# Main_DIY_board_-_no_3V3.net
KiCad netlist of a schematic drawn in EAGLE
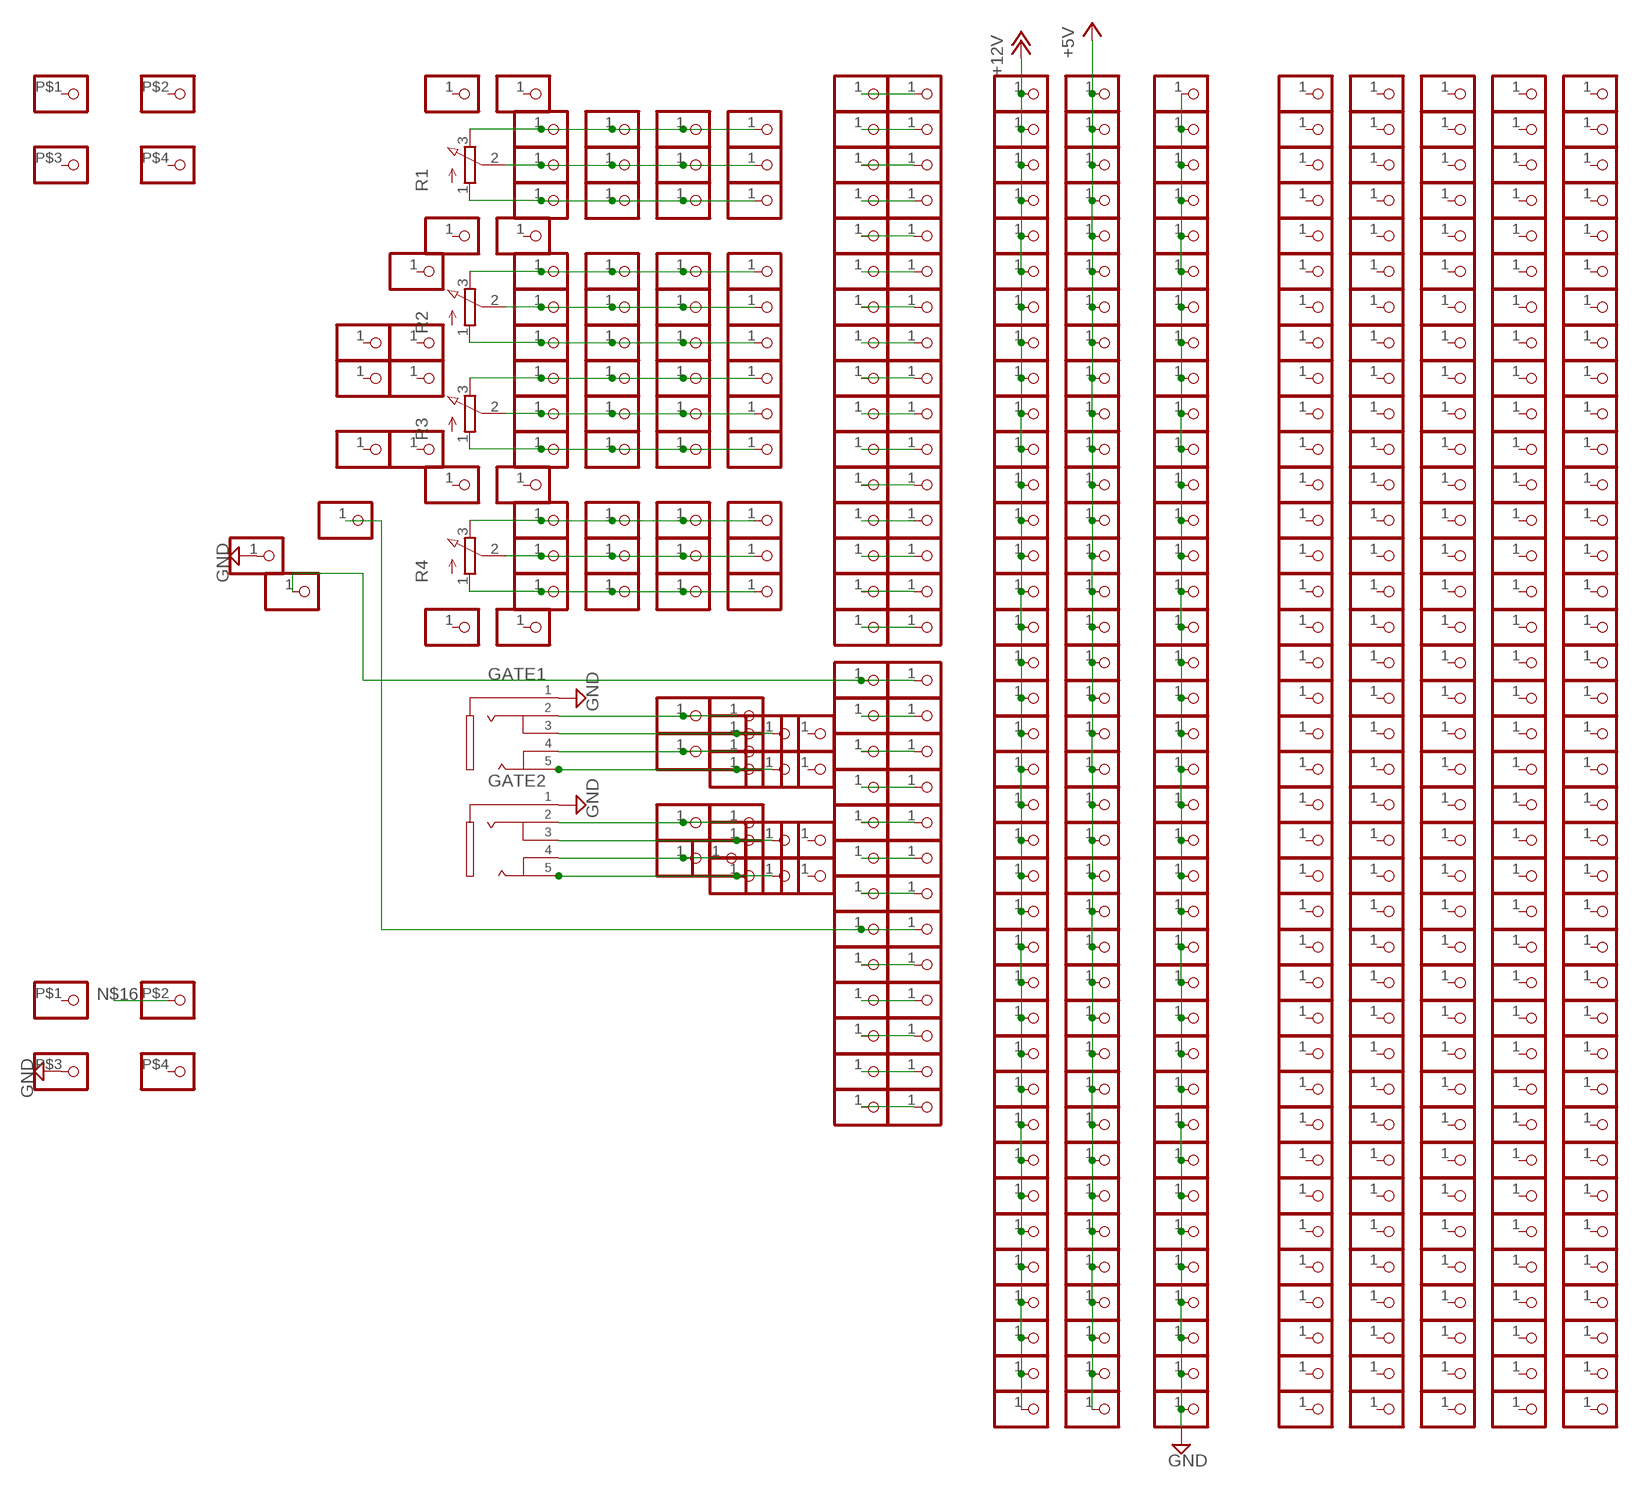
[diagram p0: schematic, sheet 1, part 1 of 2]
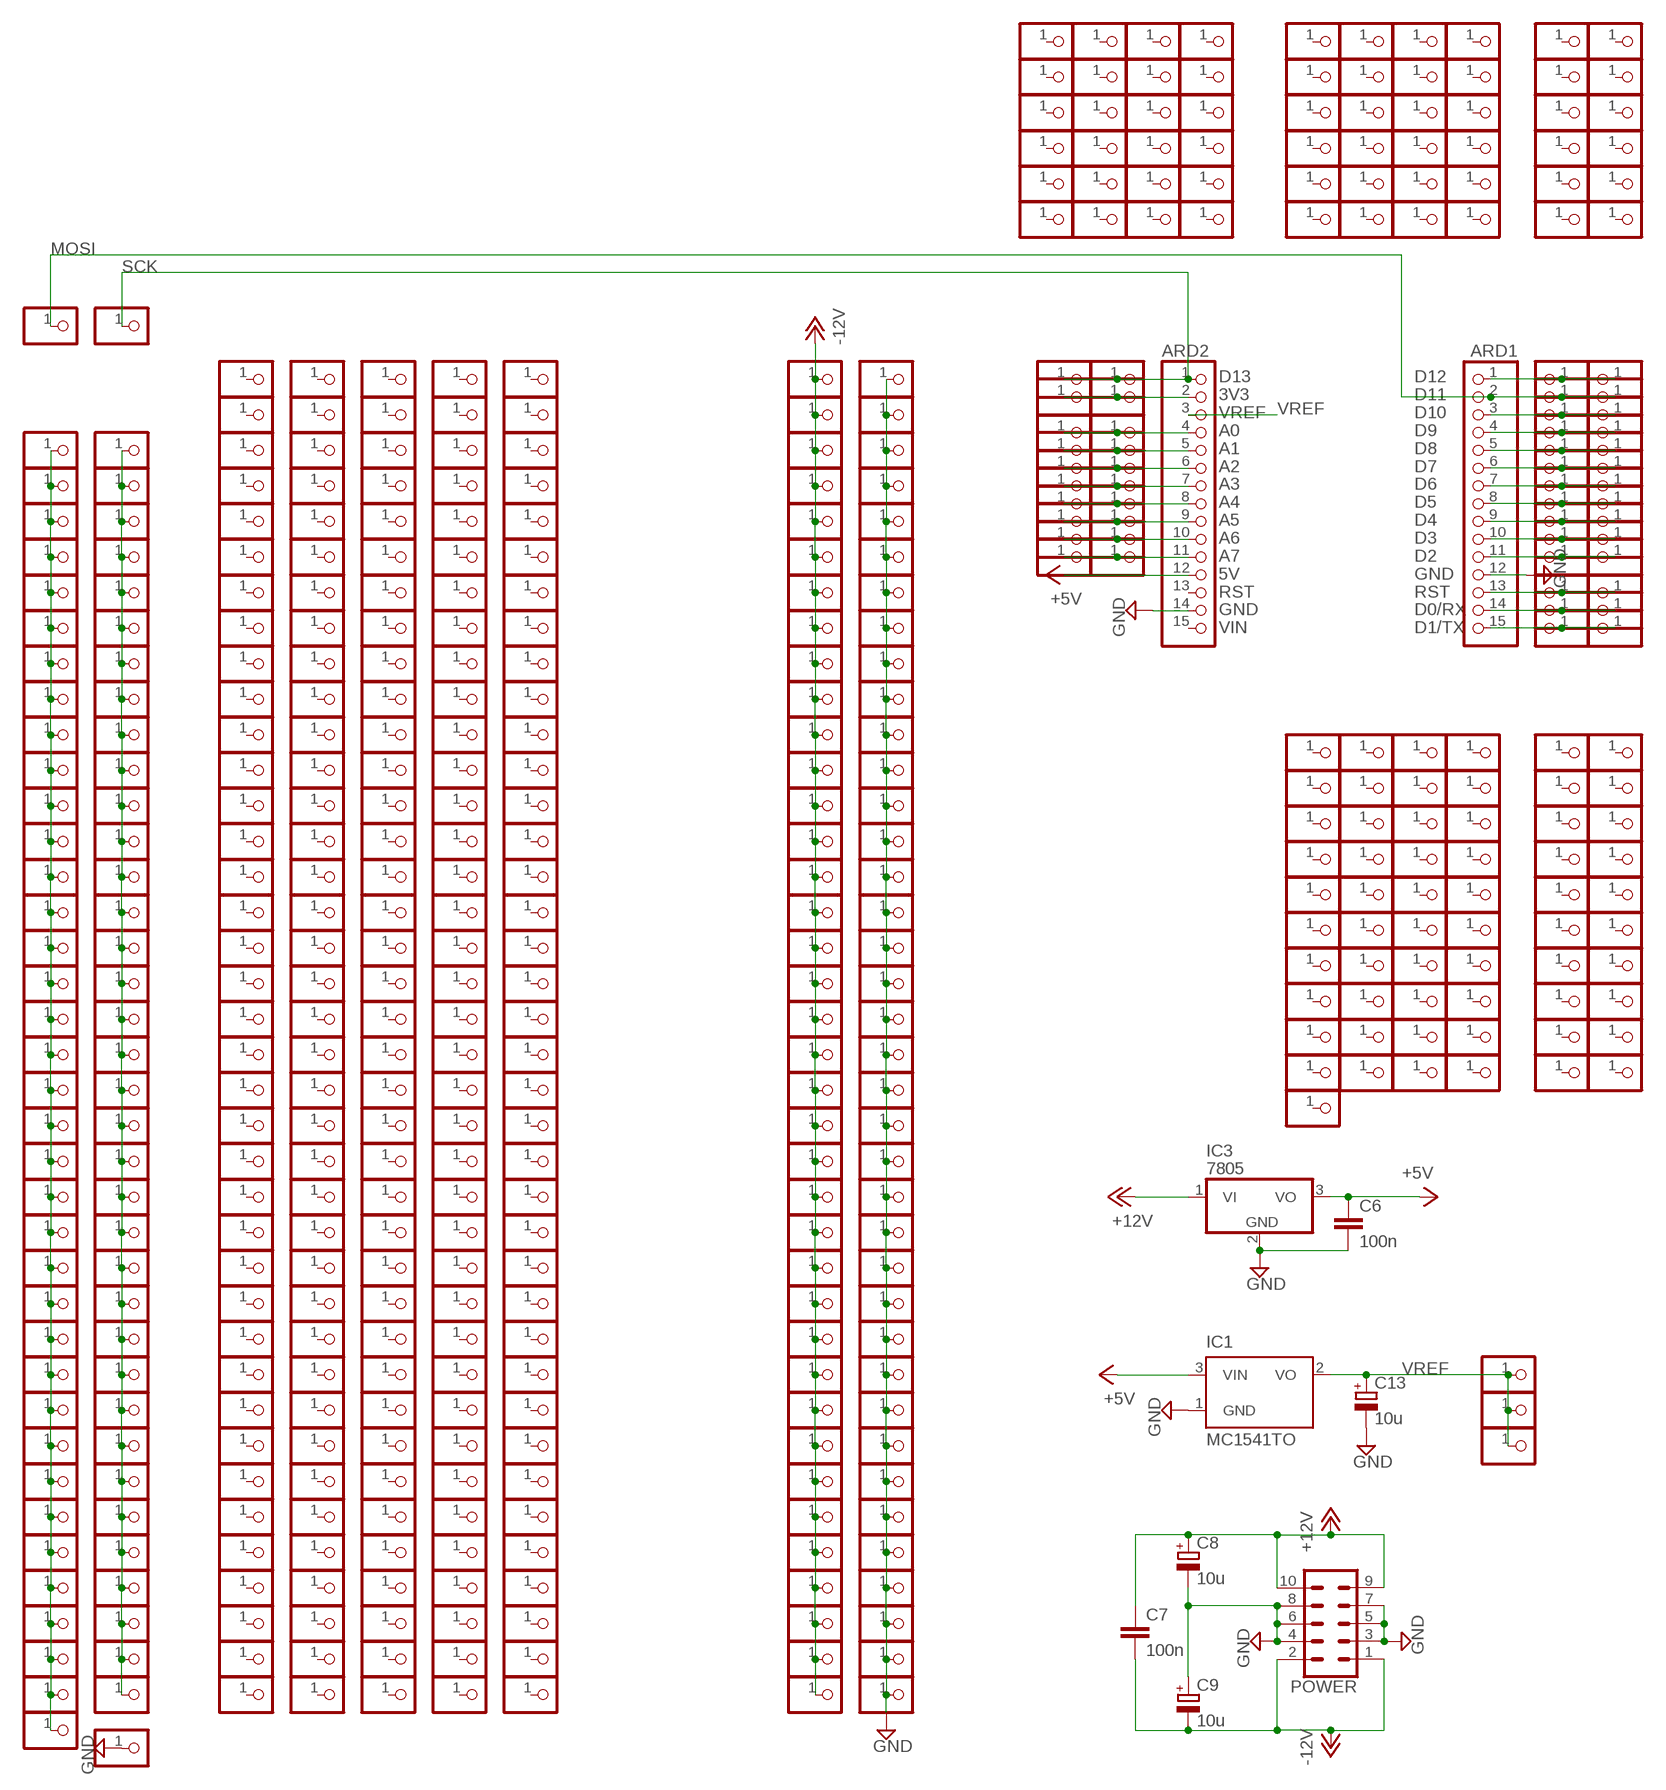
[diagram p1: schematic, sheet 1, part 2 of 2]

(export (version "E")
  (design (tool "Eeschema 10.0.6"))
  (components
    (comp (ref "ARD1")
      (value "PINHD-1X15")
      (footprint "eagle-import:1X15")
      (libsource (lib "eagle-import") (part "PINHD-1X15"))
    )
    (comp (ref "ARD2")
      (value "PINHD-1X15")
      (footprint "eagle-import:1X15")
      (libsource (lib "eagle-import") (part "PINHD-1X15"))
    )
    (comp (ref "C6")
      (value "100n")
      (footprint "eagle-import:C050-025X075")
      (libsource (lib "eagle-import") (part "C-EU050-025X075"))
    )
    (comp (ref "C7")
      (value "100n")
      (footprint "eagle-import:C050-025X075")
      (libsource (lib "eagle-import") (part "C-EU050-025X075"))
    )
    (comp (ref "C8")
      (value "10u")
      (footprint "eagle-import:E2,5-5")
      (libsource (lib "eagle-import") (part "CPOL"))
    )
    (comp (ref "C9")
      (value "10u")
      (footprint "eagle-import:E2,5-5")
      (libsource (lib "eagle-import") (part "CPOL"))
    )
    (comp (ref "C13")
      (value "10u")
      (footprint "eagle-import:E2,5-5")
      (libsource (lib "eagle-import") (part "CPOL"))
    )
    (comp (ref "GATE1")
      (value "PJ-324MH")
      (footprint "eagle-import:PJ-324MH")
      (libsource (lib "eagle-import") (part "PJ-324MH"))
    )
    (comp (ref "GATE2")
      (value "PJ-324MH")
      (footprint "eagle-import:PJ-324MH")
      (libsource (lib "eagle-import") (part "PJ-324MH"))
    )
    (comp (ref "IC1")
      (value "MC1541TO")
      (footprint "eagle-import:TO92")
      (libsource (lib "eagle-import") (part "MC15TO41"))
    )
    (comp (ref "IC3")
      (value "7805")
      (footprint "eagle-import:TO220H")
      (libsource (lib "eagle-import") (part "78T05"))
    )
    (comp (ref "JP1")
      (value "1X01")
      (footprint "eagle-import:1X01")
      (libsource (lib "eagle-import") (part "1X01"))
    )
    (comp (ref "JP2")
      (value "1X01")
      (footprint "eagle-import:1X01")
      (libsource (lib "eagle-import") (part "1X01"))
    )
    (comp (ref "JP3")
      (value "1X01")
      (footprint "eagle-import:1X01")
      (libsource (lib "eagle-import") (part "1X01"))
    )
    (comp (ref "JP4")
      (value "1X01")
      (footprint "eagle-import:1X01")
      (libsource (lib "eagle-import") (part "1X01"))
    )
    (comp (ref "JP5")
      (value "1X01")
      (footprint "eagle-import:1X01")
      (libsource (lib "eagle-import") (part "1X01"))
    )
    (comp (ref "JP6")
      (value "1X01")
      (footprint "eagle-import:1X01")
      (libsource (lib "eagle-import") (part "1X01"))
    )
    (comp (ref "JP7")
      (value "1X01")
      (footprint "eagle-import:1X01")
      (libsource (lib "eagle-import") (part "1X01"))
    )
    (comp (ref "JP8")
      (value "1X01")
      (footprint "eagle-import:1X01")
      (libsource (lib "eagle-import") (part "1X01"))
    )
    (comp (ref "JP9")
      (value "1X01")
      (footprint "eagle-import:1X01")
      (libsource (lib "eagle-import") (part "1X01"))
    )
    (comp (ref "JP10")
      (value "1X01")
      (footprint "eagle-import:1X01")
      (libsource (lib "eagle-import") (part "1X01"))
    )
    (comp (ref "JP11")
      (value "1X01")
      (footprint "eagle-import:1X01")
      (libsource (lib "eagle-import") (part "1X01"))
    )
    (comp (ref "JP12")
      (value "1X01")
      (footprint "eagle-import:1X01")
      (libsource (lib "eagle-import") (part "1X01"))
    )
    (comp (ref "JP13")
      (value "1X01")
      (footprint "eagle-import:1X01")
      (libsource (lib "eagle-import") (part "1X01"))
    )
    (comp (ref "JP14")
      (value "1X01")
      (footprint "eagle-import:1X01")
      (libsource (lib "eagle-import") (part "1X01"))
    )
    (comp (ref "JP15")
      (value "1X01")
      (footprint "eagle-import:1X01")
      (libsource (lib "eagle-import") (part "1X01"))
    )
    (comp (ref "JP16")
      (value "1X01")
      (footprint "eagle-import:1X01")
      (libsource (lib "eagle-import") (part "1X01"))
    )
    (comp (ref "JP17")
      (value "1X01")
      (footprint "eagle-import:1X01")
      (libsource (lib "eagle-import") (part "1X01"))
    )
    (comp (ref "JP18")
      (value "1X01")
      (footprint "eagle-import:1X01")
      (libsource (lib "eagle-import") (part "1X01"))
    )
    (comp (ref "JP19")
      (value "1X01")
      (footprint "eagle-import:1X01")
      (libsource (lib "eagle-import") (part "1X01"))
    )
    (comp (ref "JP20")
      (value "1X01")
      (footprint "eagle-import:1X01")
      (libsource (lib "eagle-import") (part "1X01"))
    )
    (comp (ref "JP21")
      (value "1X01")
      (footprint "eagle-import:1X01")
      (libsource (lib "eagle-import") (part "1X01"))
    )
    (comp (ref "JP22")
      (value "1X01")
      (footprint "eagle-import:1X01")
      (libsource (lib "eagle-import") (part "1X01"))
    )
    (comp (ref "JP23")
      (value "1X01")
      (footprint "eagle-import:1X01")
      (libsource (lib "eagle-import") (part "1X01"))
    )
    (comp (ref "JP24")
      (value "1X01")
      (footprint "eagle-import:1X01")
      (libsource (lib "eagle-import") (part "1X01"))
    )
    (comp (ref "JP25")
      (value "1X01")
      (footprint "eagle-import:1X01")
      (libsource (lib "eagle-import") (part "1X01"))
    )
    (comp (ref "JP26")
      (value "1X01")
      (footprint "eagle-import:1X01")
      (libsource (lib "eagle-import") (part "1X01"))
    )
    (comp (ref "JP27")
      (value "1X01")
      (footprint "eagle-import:1X01")
      (libsource (lib "eagle-import") (part "1X01"))
    )
    (comp (ref "JP28")
      (value "1X01")
      (footprint "eagle-import:1X01")
      (libsource (lib "eagle-import") (part "1X01"))
    )
    (comp (ref "JP29")
      (value "1X01")
      (footprint "eagle-import:1X01")
      (libsource (lib "eagle-import") (part "1X01"))
    )
    (comp (ref "JP30")
      (value "1X01")
      (footprint "eagle-import:1X01")
      (libsource (lib "eagle-import") (part "1X01"))
    )
    (comp (ref "JP31")
      (value "1X01")
      (footprint "eagle-import:1X01")
      (libsource (lib "eagle-import") (part "1X01"))
    )
    (comp (ref "JP32")
      (value "1X01")
      (footprint "eagle-import:1X01")
      (libsource (lib "eagle-import") (part "1X01"))
    )
    (comp (ref "JP33")
      (value "1X01")
      (footprint "eagle-import:1X01")
      (libsource (lib "eagle-import") (part "1X01"))
    )
    (comp (ref "JP34")
      (value "1X01")
      (footprint "eagle-import:1X01")
      (libsource (lib "eagle-import") (part "1X01"))
    )
    (comp (ref "JP35")
      (value "1X01")
      (footprint "eagle-import:1X01")
      (libsource (lib "eagle-import") (part "1X01"))
    )
    (comp (ref "JP36")
      (value "1X01")
      (footprint "eagle-import:1X01")
      (libsource (lib "eagle-import") (part "1X01"))
    )
    (comp (ref "JP37")
      (value "1X01")
      (footprint "eagle-import:1X01")
      (libsource (lib "eagle-import") (part "1X01"))
    )
    (comp (ref "JP38")
      (value "1X01")
      (footprint "eagle-import:1X01")
      (libsource (lib "eagle-import") (part "1X01"))
    )
    (comp (ref "JP39")
      (value "1X01")
      (footprint "eagle-import:1X01")
      (libsource (lib "eagle-import") (part "1X01"))
    )
    (comp (ref "JP40")
      (value "1X01")
      (footprint "eagle-import:1X01")
      (libsource (lib "eagle-import") (part "1X01"))
    )
    (comp (ref "JP41")
      (value "1X01")
      (footprint "eagle-import:1X01")
      (libsource (lib "eagle-import") (part "1X01"))
    )
    (comp (ref "JP42")
      (value "1X01")
      (footprint "eagle-import:1X01")
      (libsource (lib "eagle-import") (part "1X01"))
    )
    (comp (ref "JP43")
      (value "1X01")
      (footprint "eagle-import:1X01")
      (libsource (lib "eagle-import") (part "1X01"))
    )
    (comp (ref "JP44")
      (value "1X01")
      (footprint "eagle-import:1X01")
      (libsource (lib "eagle-import") (part "1X01"))
    )
    (comp (ref "JP45")
      (value "1X01")
      (footprint "eagle-import:1X01")
      (libsource (lib "eagle-import") (part "1X01"))
    )
    (comp (ref "JP46")
      (value "1X01")
      (footprint "eagle-import:1X01")
      (libsource (lib "eagle-import") (part "1X01"))
    )
    (comp (ref "JP47")
      (value "1X01")
      (footprint "eagle-import:1X01")
      (libsource (lib "eagle-import") (part "1X01"))
    )
    (comp (ref "JP48")
      (value "1X01")
      (footprint "eagle-import:1X01")
      (libsource (lib "eagle-import") (part "1X01"))
    )
    (comp (ref "JP49")
      (value "1X01")
      (footprint "eagle-import:1X01")
      (libsource (lib "eagle-import") (part "1X01"))
    )
    (comp (ref "JP50")
      (value "1X01")
      (footprint "eagle-import:1X01")
      (libsource (lib "eagle-import") (part "1X01"))
    )
    (comp (ref "JP51")
      (value "1X01")
      (footprint "eagle-import:1X01")
      (libsource (lib "eagle-import") (part "1X01"))
    )
    (comp (ref "JP52")
      (value "1X01")
      (footprint "eagle-import:1X01")
      (libsource (lib "eagle-import") (part "1X01"))
    )
    (comp (ref "JP53")
      (value "1X01")
      (footprint "eagle-import:1X01")
      (libsource (lib "eagle-import") (part "1X01"))
    )
    (comp (ref "JP54")
      (value "1X01")
      (footprint "eagle-import:1X01")
      (libsource (lib "eagle-import") (part "1X01"))
    )
    (comp (ref "JP55")
      (value "1X01")
      (footprint "eagle-import:1X01")
      (libsource (lib "eagle-import") (part "1X01"))
    )
    (comp (ref "JP56")
      (value "1X01")
      (footprint "eagle-import:1X01")
      (libsource (lib "eagle-import") (part "1X01"))
    )
    (comp (ref "JP57")
      (value "1X01")
      (footprint "eagle-import:1X01")
      (libsource (lib "eagle-import") (part "1X01"))
    )
    (comp (ref "JP58")
      (value "1X01")
      (footprint "eagle-import:1X01")
      (libsource (lib "eagle-import") (part "1X01"))
    )
    (comp (ref "JP59")
      (value "1X01")
      (footprint "eagle-import:1X01")
      (libsource (lib "eagle-import") (part "1X01"))
    )
    (comp (ref "JP60")
      (value "1X01")
      (footprint "eagle-import:1X01")
      (libsource (lib "eagle-import") (part "1X01"))
    )
    (comp (ref "JP61")
      (value "1X01")
      (footprint "eagle-import:1X01")
      (libsource (lib "eagle-import") (part "1X01"))
    )
    (comp (ref "JP62")
      (value "1X01")
      (footprint "eagle-import:1X01")
      (libsource (lib "eagle-import") (part "1X01"))
    )
    (comp (ref "JP63")
      (value "1X01")
      (footprint "eagle-import:1X01")
      (libsource (lib "eagle-import") (part "1X01"))
    )
    (comp (ref "JP64")
      (value "1X01")
      (footprint "eagle-import:1X01")
      (libsource (lib "eagle-import") (part "1X01"))
    )
    (comp (ref "JP65")
      (value "1X01")
      (footprint "eagle-import:1X01")
      (libsource (lib "eagle-import") (part "1X01"))
    )
    (comp (ref "JP66")
      (value "1X01")
      (footprint "eagle-import:1X01")
      (libsource (lib "eagle-import") (part "1X01"))
    )
    (comp (ref "JP67")
      (value "1X01")
      (footprint "eagle-import:1X01")
      (libsource (lib "eagle-import") (part "1X01"))
    )
    (comp (ref "JP68")
      (value "1X01")
      (footprint "eagle-import:1X01")
      (libsource (lib "eagle-import") (part "1X01"))
    )
    (comp (ref "JP69")
      (value "1X01")
      (footprint "eagle-import:1X01")
      (libsource (lib "eagle-import") (part "1X01"))
    )
    (comp (ref "JP70")
      (value "1X01")
      (footprint "eagle-import:1X01")
      (libsource (lib "eagle-import") (part "1X01"))
    )
    (comp (ref "JP71")
      (value "1X01")
      (footprint "eagle-import:1X01")
      (libsource (lib "eagle-import") (part "1X01"))
    )
    (comp (ref "JP72")
      (value "1X01")
      (footprint "eagle-import:1X01")
      (libsource (lib "eagle-import") (part "1X01"))
    )
    (comp (ref "JP73")
      (value "1X01")
      (footprint "eagle-import:1X01")
      (libsource (lib "eagle-import") (part "1X01"))
    )
    (comp (ref "JP74")
      (value "1X01")
      (footprint "eagle-import:1X01")
      (libsource (lib "eagle-import") (part "1X01"))
    )
    (comp (ref "JP75")
      (value "1X01")
      (footprint "eagle-import:1X01")
      (libsource (lib "eagle-import") (part "1X01"))
    )
    (comp (ref "JP76")
      (value "1X01")
      (footprint "eagle-import:1X01")
      (libsource (lib "eagle-import") (part "1X01"))
    )
    (comp (ref "JP77")
      (value "1X01")
      (footprint "eagle-import:1X01")
      (libsource (lib "eagle-import") (part "1X01"))
    )
    (comp (ref "JP78")
      (value "1X01")
      (footprint "eagle-import:1X01")
      (libsource (lib "eagle-import") (part "1X01"))
    )
    (comp (ref "JP79")
      (value "1X01")
      (footprint "eagle-import:1X01")
      (libsource (lib "eagle-import") (part "1X01"))
    )
    (comp (ref "JP80")
      (value "1X01")
      (footprint "eagle-import:1X01")
      (libsource (lib "eagle-import") (part "1X01"))
    )
    (comp (ref "JP81")
      (value "1X01")
      (footprint "eagle-import:1X01")
      (libsource (lib "eagle-import") (part "1X01"))
    )
    (comp (ref "JP82")
      (value "1X01")
      (footprint "eagle-import:1X01")
      (libsource (lib "eagle-import") (part "1X01"))
    )
    (comp (ref "JP83")
      (value "1X01")
      (footprint "eagle-import:1X01")
      (libsource (lib "eagle-import") (part "1X01"))
    )
    (comp (ref "JP84")
      (value "1X01")
      (footprint "eagle-import:1X01")
      (libsource (lib "eagle-import") (part "1X01"))
    )
    (comp (ref "JP85")
      (value "1X01")
      (footprint "eagle-import:1X01")
      (libsource (lib "eagle-import") (part "1X01"))
    )
    (comp (ref "JP86")
      (value "1X01")
      (footprint "eagle-import:1X01")
      (libsource (lib "eagle-import") (part "1X01"))
    )
    (comp (ref "JP87")
      (value "1X01")
      (footprint "eagle-import:1X01")
      (libsource (lib "eagle-import") (part "1X01"))
    )
    (comp (ref "JP88")
      (value "1X01")
      (footprint "eagle-import:1X01")
      (libsource (lib "eagle-import") (part "1X01"))
    )
    (comp (ref "JP89")
      (value "1X01")
      (footprint "eagle-import:1X01")
      (libsource (lib "eagle-import") (part "1X01"))
    )
    (comp (ref "JP90")
      (value "1X01")
      (footprint "eagle-import:1X01")
      (libsource (lib "eagle-import") (part "1X01"))
    )
    (comp (ref "JP91")
      (value "1X01")
      (footprint "eagle-import:1X01")
      (libsource (lib "eagle-import") (part "1X01"))
    )
    (comp (ref "JP92")
      (value "1X01")
      (footprint "eagle-import:1X01")
      (libsource (lib "eagle-import") (part "1X01"))
    )
    (comp (ref "JP93")
      (value "1X01")
      (footprint "eagle-import:1X01")
      (libsource (lib "eagle-import") (part "1X01"))
    )
    (comp (ref "JP94")
      (value "1X01")
      (footprint "eagle-import:1X01")
      (libsource (lib "eagle-import") (part "1X01"))
    )
    (comp (ref "JP95")
      (value "1X01")
      (footprint "eagle-import:1X01")
      (libsource (lib "eagle-import") (part "1X01"))
    )
    (comp (ref "JP96")
      (value "1X01")
      (footprint "eagle-import:1X01")
      (libsource (lib "eagle-import") (part "1X01"))
    )
    (comp (ref "JP97")
      (value "1X01")
      (footprint "eagle-import:1X01")
      (libsource (lib "eagle-import") (part "1X01"))
    )
    (comp (ref "JP98")
      (value "1X01")
      (footprint "eagle-import:1X01")
      (libsource (lib "eagle-import") (part "1X01"))
    )
    (comp (ref "JP99")
      (value "1X01")
      (footprint "eagle-import:1X01")
      (libsource (lib "eagle-import") (part "1X01"))
    )
    (comp (ref "JP100")
      (value "1X01")
      (footprint "eagle-import:1X01")
      (libsource (lib "eagle-import") (part "1X01"))
    )
    (comp (ref "JP101")
      (value "1X01")
      (footprint "eagle-import:1X01")
      (libsource (lib "eagle-import") (part "1X01"))
    )
    (comp (ref "JP102")
      (value "1X01")
      (footprint "eagle-import:1X01")
      (libsource (lib "eagle-import") (part "1X01"))
    )
    (comp (ref "JP103")
      (value "1X01")
      (footprint "eagle-import:1X01")
      (libsource (lib "eagle-import") (part "1X01"))
    )
    (comp (ref "JP104")
      (value "1X01")
      (footprint "eagle-import:1X01")
      (libsource (lib "eagle-import") (part "1X01"))
    )
    (comp (ref "JP105")
      (value "1X01")
      (footprint "eagle-import:1X01")
      (libsource (lib "eagle-import") (part "1X01"))
    )
    (comp (ref "JP106")
      (value "1X01")
      (footprint "eagle-import:1X01")
      (libsource (lib "eagle-import") (part "1X01"))
    )
    (comp (ref "JP107")
      (value "1X01")
      (footprint "eagle-import:1X01")
      (libsource (lib "eagle-import") (part "1X01"))
    )
    (comp (ref "JP108")
      (value "1X01")
      (footprint "eagle-import:1X01")
      (libsource (lib "eagle-import") (part "1X01"))
    )
    (comp (ref "JP109")
      (value "1X01")
      (footprint "eagle-import:1X01")
      (libsource (lib "eagle-import") (part "1X01"))
    )
    (comp (ref "JP110")
      (value "1X01")
      (footprint "eagle-import:1X01")
      (libsource (lib "eagle-import") (part "1X01"))
    )
    (comp (ref "JP111")
      (value "1X01")
      (footprint "eagle-import:1X01")
      (libsource (lib "eagle-import") (part "1X01"))
    )
    (comp (ref "JP112")
      (value "1X01")
      (footprint "eagle-import:1X01")
      (libsource (lib "eagle-import") (part "1X01"))
    )
    (comp (ref "JP113")
      (value "1X01")
      (footprint "eagle-import:1X01")
      (libsource (lib "eagle-import") (part "1X01"))
    )
    (comp (ref "JP114")
      (value "1X01")
      (footprint "eagle-import:1X01")
      (libsource (lib "eagle-import") (part "1X01"))
    )
    (comp (ref "JP115")
      (value "1X01")
      (footprint "eagle-import:1X01")
      (libsource (lib "eagle-import") (part "1X01"))
    )
    (comp (ref "JP116")
      (value "1X01")
      (footprint "eagle-import:1X01")
      (libsource (lib "eagle-import") (part "1X01"))
    )
    (comp (ref "JP117")
      (value "1X01")
      (footprint "eagle-import:1X01")
      (libsource (lib "eagle-import") (part "1X01"))
    )
    (comp (ref "JP118")
      (value "1X01")
      (footprint "eagle-import:1X01")
      (libsource (lib "eagle-import") (part "1X01"))
    )
    (comp (ref "JP119")
      (value "1X01")
      (footprint "eagle-import:1X01")
      (libsource (lib "eagle-import") (part "1X01"))
    )
    (comp (ref "JP120")
      (value "1X01")
      (footprint "eagle-import:1X01")
      (libsource (lib "eagle-import") (part "1X01"))
    )
    (comp (ref "JP121")
      (value "1X01")
      (footprint "eagle-import:1X01")
      (libsource (lib "eagle-import") (part "1X01"))
    )
    (comp (ref "JP122")
      (value "1X01")
      (footprint "eagle-import:1X01")
      (libsource (lib "eagle-import") (part "1X01"))
    )
    (comp (ref "JP123")
      (value "1X01")
      (footprint "eagle-import:1X01")
      (libsource (lib "eagle-import") (part "1X01"))
    )
    (comp (ref "JP124")
      (value "1X01")
      (footprint "eagle-import:1X01")
      (libsource (lib "eagle-import") (part "1X01"))
    )
    (comp (ref "JP125")
      (value "1X01")
      (footprint "eagle-import:1X01")
      (libsource (lib "eagle-import") (part "1X01"))
    )
    (comp (ref "JP126")
      (value "1X01")
      (footprint "eagle-import:1X01")
      (libsource (lib "eagle-import") (part "1X01"))
    )
    (comp (ref "JP127")
      (value "1X01")
      (footprint "eagle-import:1X01")
      (libsource (lib "eagle-import") (part "1X01"))
    )
    (comp (ref "JP128")
      (value "1X01")
      (footprint "eagle-import:1X01")
      (libsource (lib "eagle-import") (part "1X01"))
    )
    (comp (ref "JP129")
      (value "1X01")
      (footprint "eagle-import:1X01")
      (libsource (lib "eagle-import") (part "1X01"))
    )
    (comp (ref "JP130")
      (value "1X01")
      (footprint "eagle-import:1X01")
      (libsource (lib "eagle-import") (part "1X01"))
    )
    (comp (ref "JP131")
      (value "1X01")
      (footprint "eagle-import:1X01")
      (libsource (lib "eagle-import") (part "1X01"))
    )
    (comp (ref "JP132")
      (value "1X01")
      (footprint "eagle-import:1X01")
      (libsource (lib "eagle-import") (part "1X01"))
    )
    (comp (ref "JP133")
      (value "1X01")
      (footprint "eagle-import:1X01")
      (libsource (lib "eagle-import") (part "1X01"))
    )
    (comp (ref "JP134")
      (value "1X01")
      (footprint "eagle-import:1X01")
      (libsource (lib "eagle-import") (part "1X01"))
    )
    (comp (ref "JP135")
      (value "1X01")
      (footprint "eagle-import:1X01")
      (libsource (lib "eagle-import") (part "1X01"))
    )
    (comp (ref "JP136")
      (value "1X01")
      (footprint "eagle-import:1X01")
      (libsource (lib "eagle-import") (part "1X01"))
    )
    (comp (ref "JP137")
      (value "1X01")
      (footprint "eagle-import:1X01")
      (libsource (lib "eagle-import") (part "1X01"))
    )
    (comp (ref "JP138")
      (value "1X01")
      (footprint "eagle-import:1X01")
      (libsource (lib "eagle-import") (part "1X01"))
    )
    (comp (ref "JP139")
      (value "1X01")
      (footprint "eagle-import:1X01")
      (libsource (lib "eagle-import") (part "1X01"))
    )
    (comp (ref "JP140")
      (value "1X01")
      (footprint "eagle-import:1X01")
      (libsource (lib "eagle-import") (part "1X01"))
    )
    (comp (ref "JP141")
      (value "1X01")
      (footprint "eagle-import:1X01")
      (libsource (lib "eagle-import") (part "1X01"))
    )
    (comp (ref "JP142")
      (value "1X01")
      (footprint "eagle-import:1X01")
      (libsource (lib "eagle-import") (part "1X01"))
    )
    (comp (ref "JP143")
      (value "1X01")
      (footprint "eagle-import:1X01")
      (libsource (lib "eagle-import") (part "1X01"))
    )
    (comp (ref "JP144")
      (value "1X01")
      (footprint "eagle-import:1X01")
      (libsource (lib "eagle-import") (part "1X01"))
    )
    (comp (ref "JP145")
      (value "1X01")
      (footprint "eagle-import:1X01")
      (libsource (lib "eagle-import") (part "1X01"))
    )
    (comp (ref "JP146")
      (value "1X01")
      (footprint "eagle-import:1X01")
      (libsource (lib "eagle-import") (part "1X01"))
    )
    (comp (ref "JP147")
      (value "1X01")
      (footprint "eagle-import:1X01")
      (libsource (lib "eagle-import") (part "1X01"))
    )
    (comp (ref "JP148")
      (value "1X01")
      (footprint "eagle-import:1X01")
      (libsource (lib "eagle-import") (part "1X01"))
    )
    (comp (ref "JP149")
      (value "1X01")
      (footprint "eagle-import:1X01")
      (libsource (lib "eagle-import") (part "1X01"))
    )
    (comp (ref "JP150")
      (value "1X01")
      (footprint "eagle-import:1X01")
      (libsource (lib "eagle-import") (part "1X01"))
    )
    (comp (ref "JP151")
      (value "1X01")
      (footprint "eagle-import:1X01")
      (libsource (lib "eagle-import") (part "1X01"))
    )
    (comp (ref "JP152")
      (value "1X01")
      (footprint "eagle-import:1X01")
      (libsource (lib "eagle-import") (part "1X01"))
    )
    (comp (ref "JP153")
      (value "1X01")
      (footprint "eagle-import:1X01")
      (libsource (lib "eagle-import") (part "1X01"))
    )
    (comp (ref "JP154")
      (value "1X01")
      (footprint "eagle-import:1X01")
      (libsource (lib "eagle-import") (part "1X01"))
    )
    (comp (ref "JP155")
      (value "1X01")
      (footprint "eagle-import:1X01")
      (libsource (lib "eagle-import") (part "1X01"))
    )
    (comp (ref "JP156")
      (value "1X01")
      (footprint "eagle-import:1X01")
      (libsource (lib "eagle-import") (part "1X01"))
    )
    (comp (ref "JP157")
      (value "1X01")
      (footprint "eagle-import:1X01")
      (libsource (lib "eagle-import") (part "1X01"))
    )
    (comp (ref "JP158")
      (value "1X01")
      (footprint "eagle-import:1X01")
      (libsource (lib "eagle-import") (part "1X01"))
    )
    (comp (ref "JP159")
      (value "1X01")
      (footprint "eagle-import:1X01")
      (libsource (lib "eagle-import") (part "1X01"))
    )
    (comp (ref "JP160")
      (value "1X01")
      (footprint "eagle-import:1X01")
      (libsource (lib "eagle-import") (part "1X01"))
    )
    (comp (ref "JP161")
      (value "1X01")
      (footprint "eagle-import:1X01")
      (libsource (lib "eagle-import") (part "1X01"))
    )
    (comp (ref "JP162")
      (value "1X01")
      (footprint "eagle-import:1X01")
      (libsource (lib "eagle-import") (part "1X01"))
    )
    (comp (ref "JP163")
      (value "1X01")
      (footprint "eagle-import:1X01")
      (libsource (lib "eagle-import") (part "1X01"))
    )
    (comp (ref "JP164")
      (value "1X01")
      (footprint "eagle-import:1X01")
      (libsource (lib "eagle-import") (part "1X01"))
    )
    (comp (ref "JP165")
      (value "1X01")
      (footprint "eagle-import:1X01")
      (libsource (lib "eagle-import") (part "1X01"))
    )
    (comp (ref "JP166")
      (value "1X01")
      (footprint "eagle-import:1X01")
      (libsource (lib "eagle-import") (part "1X01"))
    )
    (comp (ref "JP167")
      (value "1X01")
      (footprint "eagle-import:1X01")
      (libsource (lib "eagle-import") (part "1X01"))
    )
    (comp (ref "JP168")
      (value "1X01")
      (footprint "eagle-import:1X01")
      (libsource (lib "eagle-import") (part "1X01"))
    )
    (comp (ref "JP169")
      (value "1X01")
      (footprint "eagle-import:1X01")
      (libsource (lib "eagle-import") (part "1X01"))
    )
    (comp (ref "JP170")
      (value "1X01")
      (footprint "eagle-import:1X01")
      (libsource (lib "eagle-import") (part "1X01"))
    )
    (comp (ref "JP171")
      (value "1X01")
      (footprint "eagle-import:1X01")
      (libsource (lib "eagle-import") (part "1X01"))
    )
    (comp (ref "JP172")
      (value "1X01")
      (footprint "eagle-import:1X01")
      (libsource (lib "eagle-import") (part "1X01"))
    )
    (comp (ref "JP173")
      (value "1X01")
      (footprint "eagle-import:1X01")
      (libsource (lib "eagle-import") (part "1X01"))
    )
    (comp (ref "JP174")
      (value "1X01")
      (footprint "eagle-import:1X01")
      (libsource (lib "eagle-import") (part "1X01"))
    )
    (comp (ref "JP175")
      (value "1X01")
      (footprint "eagle-import:1X01")
      (libsource (lib "eagle-import") (part "1X01"))
    )
    (comp (ref "JP176")
      (value "1X01")
      (footprint "eagle-import:1X01")
      (libsource (lib "eagle-import") (part "1X01"))
    )
    (comp (ref "JP177")
      (value "1X01")
      (footprint "eagle-import:1X01")
      (libsource (lib "eagle-import") (part "1X01"))
    )
    (comp (ref "JP178")
      (value "1X01")
      (footprint "eagle-import:1X01")
      (libsource (lib "eagle-import") (part "1X01"))
    )
    (comp (ref "JP179")
      (value "1X01")
      (footprint "eagle-import:1X01")
      (libsource (lib "eagle-import") (part "1X01"))
    )
    (comp (ref "JP180")
      (value "1X01")
      (footprint "eagle-import:1X01")
      (libsource (lib "eagle-import") (part "1X01"))
    )
    (comp (ref "JP181")
      (value "1X01")
      (footprint "eagle-import:1X01")
      (libsource (lib "eagle-import") (part "1X01"))
    )
    (comp (ref "JP182")
      (value "1X01")
      (footprint "eagle-import:1X01")
      (libsource (lib "eagle-import") (part "1X01"))
    )
    (comp (ref "JP183")
      (value "1X01")
      (footprint "eagle-import:1X01")
      (libsource (lib "eagle-import") (part "1X01"))
    )
    (comp (ref "JP184")
      (value "1X01")
      (footprint "eagle-import:1X01")
      (libsource (lib "eagle-import") (part "1X01"))
    )
    (comp (ref "JP185")
      (value "1X01")
      (footprint "eagle-import:1X01")
      (libsource (lib "eagle-import") (part "1X01"))
    )
    (comp (ref "JP186")
      (value "1X01")
      (footprint "eagle-import:1X01")
      (libsource (lib "eagle-import") (part "1X01"))
    )
    (comp (ref "JP187")
      (value "1X01")
      (footprint "eagle-import:1X01")
      (libsource (lib "eagle-import") (part "1X01"))
    )
    (comp (ref "JP188")
      (value "1X01")
      (footprint "eagle-import:1X01")
      (libsource (lib "eagle-import") (part "1X01"))
    )
    (comp (ref "JP189")
      (value "1X01")
      (footprint "eagle-import:1X01")
      (libsource (lib "eagle-import") (part "1X01"))
    )
    (comp (ref "JP190")
      (value "1X01")
      (footprint "eagle-import:1X01")
      (libsource (lib "eagle-import") (part "1X01"))
    )
    (comp (ref "JP191")
      (value "1X01")
      (footprint "eagle-import:1X01")
      (libsource (lib "eagle-import") (part "1X01"))
    )
    (comp (ref "JP192")
      (value "1X01")
      (footprint "eagle-import:1X01")
      (libsource (lib "eagle-import") (part "1X01"))
    )
    (comp (ref "JP193")
      (value "1X01")
      (footprint "eagle-import:1X01")
      (libsource (lib "eagle-import") (part "1X01"))
    )
    (comp (ref "JP194")
      (value "1X01")
      (footprint "eagle-import:1X01")
      (libsource (lib "eagle-import") (part "1X01"))
    )
    (comp (ref "JP195")
      (value "1X01")
      (footprint "eagle-import:1X01")
      (libsource (lib "eagle-import") (part "1X01"))
    )
    (comp (ref "JP196")
      (value "1X01")
      (footprint "eagle-import:1X01")
      (libsource (lib "eagle-import") (part "1X01"))
    )
    (comp (ref "JP197")
      (value "1X01")
      (footprint "eagle-import:1X01")
      (libsource (lib "eagle-import") (part "1X01"))
    )
    (comp (ref "JP198")
      (value "1X01")
      (footprint "eagle-import:1X01")
      (libsource (lib "eagle-import") (part "1X01"))
    )
    (comp (ref "JP199")
      (value "1X01")
      (footprint "eagle-import:1X01")
      (libsource (lib "eagle-import") (part "1X01"))
    )
    (comp (ref "JP200")
      (value "1X01")
      (footprint "eagle-import:1X01")
      (libsource (lib "eagle-import") (part "1X01"))
    )
    (comp (ref "JP201")
      (value "1X01")
      (footprint "eagle-import:1X01")
      (libsource (lib "eagle-import") (part "1X01"))
    )
    (comp (ref "JP202")
      (value "1X01")
      (footprint "eagle-import:1X01")
      (libsource (lib "eagle-import") (part "1X01"))
    )
    (comp (ref "JP203")
      (value "1X01")
      (footprint "eagle-import:1X01")
      (libsource (lib "eagle-import") (part "1X01"))
    )
    (comp (ref "JP204")
      (value "1X01")
      (footprint "eagle-import:1X01")
      (libsource (lib "eagle-import") (part "1X01"))
    )
    (comp (ref "JP205")
      (value "1X01")
      (footprint "eagle-import:1X01")
      (libsource (lib "eagle-import") (part "1X01"))
    )
    (comp (ref "JP206")
      (value "1X01")
      (footprint "eagle-import:1X01")
      (libsource (lib "eagle-import") (part "1X01"))
    )
    (comp (ref "JP207")
      (value "1X01")
      (footprint "eagle-import:1X01")
      (libsource (lib "eagle-import") (part "1X01"))
    )
    (comp (ref "JP208")
      (value "1X01")
      (footprint "eagle-import:1X01")
      (libsource (lib "eagle-import") (part "1X01"))
    )
    (comp (ref "JP209")
      (value "1X01")
      (footprint "eagle-import:1X01")
      (libsource (lib "eagle-import") (part "1X01"))
    )
    (comp (ref "JP210")
      (value "1X01")
      (footprint "eagle-import:1X01")
      (libsource (lib "eagle-import") (part "1X01"))
    )
    (comp (ref "JP211")
      (value "1X01")
      (footprint "eagle-import:1X01")
      (libsource (lib "eagle-import") (part "1X01"))
    )
    (comp (ref "JP212")
      (value "1X01")
      (footprint "eagle-import:1X01")
      (libsource (lib "eagle-import") (part "1X01"))
    )
    (comp (ref "JP213")
      (value "1X01")
      (footprint "eagle-import:1X01")
      (libsource (lib "eagle-import") (part "1X01"))
    )
    (comp (ref "JP214")
      (value "1X01")
      (footprint "eagle-import:1X01")
      (libsource (lib "eagle-import") (part "1X01"))
    )
    (comp (ref "JP215")
      (value "1X01")
      (footprint "eagle-import:1X01")
      (libsource (lib "eagle-import") (part "1X01"))
    )
    (comp (ref "JP216")
      (value "1X01")
      (footprint "eagle-import:1X01")
      (libsource (lib "eagle-import") (part "1X01"))
    )
    (comp (ref "JP217")
      (value "1X01")
      (footprint "eagle-import:1X01")
      (libsource (lib "eagle-import") (part "1X01"))
    )
    (comp (ref "JP218")
      (value "1X01")
      (footprint "eagle-import:1X01")
      (libsource (lib "eagle-import") (part "1X01"))
    )
    (comp (ref "JP219")
      (value "1X01")
      (footprint "eagle-import:1X01")
      (libsource (lib "eagle-import") (part "1X01"))
    )
    (comp (ref "JP220")
      (value "1X01")
      (footprint "eagle-import:1X01")
      (libsource (lib "eagle-import") (part "1X01"))
    )
    (comp (ref "JP221")
      (value "1X01")
      (footprint "eagle-import:1X01")
      (libsource (lib "eagle-import") (part "1X01"))
    )
    (comp (ref "JP222")
      (value "1X01")
      (footprint "eagle-import:1X01")
      (libsource (lib "eagle-import") (part "1X01"))
    )
    (comp (ref "JP223")
      (value "1X01")
      (footprint "eagle-import:1X01")
      (libsource (lib "eagle-import") (part "1X01"))
    )
    (comp (ref "JP224")
      (value "1X01")
      (footprint "eagle-import:1X01")
      (libsource (lib "eagle-import") (part "1X01"))
    )
    (comp (ref "JP225")
      (value "1X01")
      (footprint "eagle-import:1X01")
      (libsource (lib "eagle-import") (part "1X01"))
    )
    (comp (ref "JP226")
      (value "1X01")
      (footprint "eagle-import:1X01")
      (libsource (lib "eagle-import") (part "1X01"))
    )
    (comp (ref "JP227")
      (value "1X01")
      (footprint "eagle-import:1X01")
      (libsource (lib "eagle-import") (part "1X01"))
    )
    (comp (ref "JP228")
      (value "1X01")
      (footprint "eagle-import:1X01")
      (libsource (lib "eagle-import") (part "1X01"))
    )
    (comp (ref "JP229")
      (value "1X01")
      (footprint "eagle-import:1X01")
      (libsource (lib "eagle-import") (part "1X01"))
    )
    (comp (ref "JP230")
      (value "1X01")
      (footprint "eagle-import:1X01")
      (libsource (lib "eagle-import") (part "1X01"))
    )
    (comp (ref "JP231")
      (value "1X01")
      (footprint "eagle-import:1X01")
      (libsource (lib "eagle-import") (part "1X01"))
    )
    (comp (ref "JP232")
      (value "1X01")
      (footprint "eagle-import:1X01")
      (libsource (lib "eagle-import") (part "1X01"))
    )
    (comp (ref "JP233")
      (value "1X01")
      (footprint "eagle-import:1X01")
      (libsource (lib "eagle-import") (part "1X01"))
    )
    (comp (ref "JP234")
      (value "1X01")
      (footprint "eagle-import:1X01")
      (libsource (lib "eagle-import") (part "1X01"))
    )
    (comp (ref "JP235")
      (value "1X01")
      (footprint "eagle-import:1X01")
      (libsource (lib "eagle-import") (part "1X01"))
    )
    (comp (ref "JP236")
      (value "1X01")
      (footprint "eagle-import:1X01")
      (libsource (lib "eagle-import") (part "1X01"))
    )
    (comp (ref "JP237")
      (value "1X01")
      (footprint "eagle-import:1X01")
      (libsource (lib "eagle-import") (part "1X01"))
    )
    (comp (ref "JP238")
      (value "1X01")
      (footprint "eagle-import:1X01")
      (libsource (lib "eagle-import") (part "1X01"))
    )
    (comp (ref "JP239")
      (value "1X01")
      (footprint "eagle-import:1X01")
      (libsource (lib "eagle-import") (part "1X01"))
    )
    (comp (ref "JP240")
      (value "1X01")
      (footprint "eagle-import:1X01")
      (libsource (lib "eagle-import") (part "1X01"))
    )
    (comp (ref "JP241")
      (value "1X01")
      (footprint "eagle-import:1X01")
      (libsource (lib "eagle-import") (part "1X01"))
    )
    (comp (ref "JP242")
      (value "1X01")
      (footprint "eagle-import:1X01")
      (libsource (lib "eagle-import") (part "1X01"))
    )
    (comp (ref "JP243")
      (value "1X01")
      (footprint "eagle-import:1X01")
      (libsource (lib "eagle-import") (part "1X01"))
    )
    (comp (ref "JP244")
      (value "1X01")
      (footprint "eagle-import:1X01")
      (libsource (lib "eagle-import") (part "1X01"))
    )
    (comp (ref "JP245")
      (value "1X01")
      (footprint "eagle-import:1X01")
      (libsource (lib "eagle-import") (part "1X01"))
    )
    (comp (ref "JP246")
      (value "1X01")
      (footprint "eagle-import:1X01")
      (libsource (lib "eagle-import") (part "1X01"))
    )
    (comp (ref "JP247")
      (value "1X01")
      (footprint "eagle-import:1X01")
      (libsource (lib "eagle-import") (part "1X01"))
    )
    (comp (ref "JP248")
      (value "1X01")
      (footprint "eagle-import:1X01")
      (libsource (lib "eagle-import") (part "1X01"))
    )
    (comp (ref "JP249")
      (value "1X01")
      (footprint "eagle-import:1X01")
      (libsource (lib "eagle-import") (part "1X01"))
    )
    (comp (ref "JP250")
      (value "1X01")
      (footprint "eagle-import:1X01")
      (libsource (lib "eagle-import") (part "1X01"))
    )
    (comp (ref "JP251")
      (value "1X01")
      (footprint "eagle-import:1X01")
      (libsource (lib "eagle-import") (part "1X01"))
    )
    (comp (ref "JP252")
      (value "1X01")
      (footprint "eagle-import:1X01")
      (libsource (lib "eagle-import") (part "1X01"))
    )
    (comp (ref "JP253")
      (value "1X01")
      (footprint "eagle-import:1X01")
      (libsource (lib "eagle-import") (part "1X01"))
    )
    (comp (ref "JP254")
      (value "1X01")
      (footprint "eagle-import:1X01")
      (libsource (lib "eagle-import") (part "1X01"))
    )
    (comp (ref "JP255")
      (value "1X01")
      (footprint "eagle-import:1X01")
      (libsource (lib "eagle-import") (part "1X01"))
    )
    (comp (ref "JP256")
      (value "1X01")
      (footprint "eagle-import:1X01")
      (libsource (lib "eagle-import") (part "1X01"))
    )
    (comp (ref "JP257")
      (value "1X01")
      (footprint "eagle-import:1X01")
      (libsource (lib "eagle-import") (part "1X01"))
    )
    (comp (ref "JP258")
      (value "1X01")
      (footprint "eagle-import:1X01")
      (libsource (lib "eagle-import") (part "1X01"))
    )
    (comp (ref "JP259")
      (value "1X01")
      (footprint "eagle-import:1X01")
      (libsource (lib "eagle-import") (part "1X01"))
    )
    (comp (ref "JP260")
      (value "1X01")
      (footprint "eagle-import:1X01")
      (libsource (lib "eagle-import") (part "1X01"))
    )
    (comp (ref "JP261")
      (value "1X01")
      (footprint "eagle-import:1X01")
      (libsource (lib "eagle-import") (part "1X01"))
    )
    (comp (ref "JP262")
      (value "1X01")
      (footprint "eagle-import:1X01")
      (libsource (lib "eagle-import") (part "1X01"))
    )
    (comp (ref "JP263")
      (value "1X01")
      (footprint "eagle-import:1X01")
      (libsource (lib "eagle-import") (part "1X01"))
    )
    (comp (ref "JP264")
      (value "1X01")
      (footprint "eagle-import:1X01")
      (libsource (lib "eagle-import") (part "1X01"))
    )
    (comp (ref "JP265")
      (value "1X01")
      (footprint "eagle-import:1X01")
      (libsource (lib "eagle-import") (part "1X01"))
    )
    (comp (ref "JP266")
      (value "1X01")
      (footprint "eagle-import:1X01")
      (libsource (lib "eagle-import") (part "1X01"))
    )
    (comp (ref "JP267")
      (value "1X01")
      (footprint "eagle-import:1X01")
      (libsource (lib "eagle-import") (part "1X01"))
    )
    (comp (ref "JP268")
      (value "1X01")
      (footprint "eagle-import:1X01")
      (libsource (lib "eagle-import") (part "1X01"))
    )
    (comp (ref "JP269")
      (value "1X01")
      (footprint "eagle-import:1X01")
      (libsource (lib "eagle-import") (part "1X01"))
    )
    (comp (ref "JP270")
      (value "1X01")
      (footprint "eagle-import:1X01")
      (libsource (lib "eagle-import") (part "1X01"))
    )
    (comp (ref "JP271")
      (value "1X01")
      (footprint "eagle-import:1X01")
      (libsource (lib "eagle-import") (part "1X01"))
    )
    (comp (ref "JP272")
      (value "1X01")
      (footprint "eagle-import:1X01")
      (libsource (lib "eagle-import") (part "1X01"))
    )
    (comp (ref "JP273")
      (value "1X01")
      (footprint "eagle-import:1X01")
      (libsource (lib "eagle-import") (part "1X01"))
    )
    (comp (ref "JP274")
      (value "1X01")
      (footprint "eagle-import:1X01")
      (libsource (lib "eagle-import") (part "1X01"))
    )
    (comp (ref "JP275")
      (value "1X01")
      (footprint "eagle-import:1X01")
      (libsource (lib "eagle-import") (part "1X01"))
    )
    (comp (ref "JP276")
      (value "1X01")
      (footprint "eagle-import:1X01")
      (libsource (lib "eagle-import") (part "1X01"))
    )
    (comp (ref "JP277")
      (value "1X01")
      (footprint "eagle-import:1X01")
      (libsource (lib "eagle-import") (part "1X01"))
    )
    (comp (ref "JP278")
      (value "1X01")
      (footprint "eagle-import:1X01")
      (libsource (lib "eagle-import") (part "1X01"))
    )
    (comp (ref "JP279")
      (value "1X01")
      (footprint "eagle-import:1X01")
      (libsource (lib "eagle-import") (part "1X01"))
    )
    (comp (ref "JP280")
      (value "1X01")
      (footprint "eagle-import:1X01")
      (libsource (lib "eagle-import") (part "1X01"))
    )
    (comp (ref "JP281")
      (value "1X01")
      (footprint "eagle-import:1X01")
      (libsource (lib "eagle-import") (part "1X01"))
    )
    (comp (ref "JP282")
      (value "1X01")
      (footprint "eagle-import:1X01")
      (libsource (lib "eagle-import") (part "1X01"))
    )
    (comp (ref "JP283")
      (value "1X01")
      (footprint "eagle-import:1X01")
      (libsource (lib "eagle-import") (part "1X01"))
    )
    (comp (ref "JP284")
      (value "1X01")
      (footprint "eagle-import:1X01")
      (libsource (lib "eagle-import") (part "1X01"))
    )
    (comp (ref "JP285")
      (value "1X01")
      (footprint "eagle-import:1X01")
      (libsource (lib "eagle-import") (part "1X01"))
    )
    (comp (ref "JP286")
      (value "1X01")
      (footprint "eagle-import:1X01")
      (libsource (lib "eagle-import") (part "1X01"))
    )
    (comp (ref "JP287")
      (value "1X01")
      (footprint "eagle-import:1X01")
      (libsource (lib "eagle-import") (part "1X01"))
    )
    (comp (ref "JP288")
      (value "1X01")
      (footprint "eagle-import:1X01")
      (libsource (lib "eagle-import") (part "1X01"))
    )
    (comp (ref "JP289")
      (value "1X01")
      (footprint "eagle-import:1X01")
      (libsource (lib "eagle-import") (part "1X01"))
    )
    (comp (ref "JP290")
      (value "1X01")
      (footprint "eagle-import:1X01")
      (libsource (lib "eagle-import") (part "1X01"))
    )
    (comp (ref "JP291")
      (value "1X01")
      (footprint "eagle-import:1X01")
      (libsource (lib "eagle-import") (part "1X01"))
    )
    (comp (ref "JP292")
      (value "1X01")
      (footprint "eagle-import:1X01")
      (libsource (lib "eagle-import") (part "1X01"))
    )
    (comp (ref "JP293")
      (value "1X01")
      (footprint "eagle-import:1X01")
      (libsource (lib "eagle-import") (part "1X01"))
    )
    (comp (ref "JP294")
      (value "1X01")
      (footprint "eagle-import:1X01")
      (libsource (lib "eagle-import") (part "1X01"))
    )
    (comp (ref "JP295")
      (value "1X01")
      (footprint "eagle-import:1X01")
      (libsource (lib "eagle-import") (part "1X01"))
    )
    (comp (ref "JP296")
      (value "1X01")
      (footprint "eagle-import:1X01")
      (libsource (lib "eagle-import") (part "1X01"))
    )
    (comp (ref "JP297")
      (value "1X01")
      (footprint "eagle-import:1X01")
      (libsource (lib "eagle-import") (part "1X01"))
    )
    (comp (ref "JP298")
      (value "1X01")
      (footprint "eagle-import:1X01")
      (libsource (lib "eagle-import") (part "1X01"))
    )
    (comp (ref "JP299")
      (value "1X01")
      (footprint "eagle-import:1X01")
      (libsource (lib "eagle-import") (part "1X01"))
    )
    (comp (ref "JP300")
      (value "1X01")
      (footprint "eagle-import:1X01")
      (libsource (lib "eagle-import") (part "1X01"))
    )
    (comp (ref "JP301")
      (value "1X01")
      (footprint "eagle-import:1X01")
      (libsource (lib "eagle-import") (part "1X01"))
    )
    (comp (ref "JP302")
      (value "1X01")
      (footprint "eagle-import:1X01")
      (libsource (lib "eagle-import") (part "1X01"))
    )
    (comp (ref "JP303")
      (value "1X01")
      (footprint "eagle-import:1X01")
      (libsource (lib "eagle-import") (part "1X01"))
    )
    (comp (ref "JP304")
      (value "1X01")
      (footprint "eagle-import:1X01")
      (libsource (lib "eagle-import") (part "1X01"))
    )
    (comp (ref "JP305")
      (value "1X01")
      (footprint "eagle-import:1X01")
      (libsource (lib "eagle-import") (part "1X01"))
    )
    (comp (ref "JP306")
      (value "1X01")
      (footprint "eagle-import:1X01")
      (libsource (lib "eagle-import") (part "1X01"))
    )
    (comp (ref "JP307")
      (value "1X01")
      (footprint "eagle-import:1X01")
      (libsource (lib "eagle-import") (part "1X01"))
    )
    (comp (ref "JP308")
      (value "1X01")
      (footprint "eagle-import:1X01")
      (libsource (lib "eagle-import") (part "1X01"))
    )
    (comp (ref "JP309")
      (value "1X01")
      (footprint "eagle-import:1X01")
      (libsource (lib "eagle-import") (part "1X01"))
    )
    (comp (ref "JP310")
      (value "1X01")
      (footprint "eagle-import:1X01")
      (libsource (lib "eagle-import") (part "1X01"))
    )
    (comp (ref "JP311")
      (value "1X01")
      (footprint "eagle-import:1X01")
      (libsource (lib "eagle-import") (part "1X01"))
    )
    (comp (ref "JP312")
      (value "1X01")
      (footprint "eagle-import:1X01")
      (libsource (lib "eagle-import") (part "1X01"))
    )
    (comp (ref "JP313")
      (value "1X01")
      (footprint "eagle-import:1X01")
      (libsource (lib "eagle-import") (part "1X01"))
    )
    (comp (ref "JP314")
      (value "1X01")
      (footprint "eagle-import:1X01")
      (libsource (lib "eagle-import") (part "1X01"))
    )
    (comp (ref "JP315")
      (value "1X01")
      (footprint "eagle-import:1X01")
      (libsource (lib "eagle-import") (part "1X01"))
    )
    (comp (ref "JP316")
      (value "1X01")
      (footprint "eagle-import:1X01")
      (libsource (lib "eagle-import") (part "1X01"))
    )
    (comp (ref "JP317")
      (value "1X01")
      (footprint "eagle-import:1X01")
      (libsource (lib "eagle-import") (part "1X01"))
    )
    (comp (ref "JP318")
      (value "1X01")
      (footprint "eagle-import:1X01")
      (libsource (lib "eagle-import") (part "1X01"))
    )
    (comp (ref "JP319")
      (value "1X01")
      (footprint "eagle-import:1X01")
      (libsource (lib "eagle-import") (part "1X01"))
    )
    (comp (ref "JP320")
      (value "1X01")
      (footprint "eagle-import:1X01")
      (libsource (lib "eagle-import") (part "1X01"))
    )
    (comp (ref "JP321")
      (value "1X01")
      (footprint "eagle-import:1X01")
      (libsource (lib "eagle-import") (part "1X01"))
    )
    (comp (ref "JP322")
      (value "1X01")
      (footprint "eagle-import:1X01")
      (libsource (lib "eagle-import") (part "1X01"))
    )
    (comp (ref "JP323")
      (value "1X01")
      (footprint "eagle-import:1X01")
      (libsource (lib "eagle-import") (part "1X01"))
    )
    (comp (ref "JP324")
      (value "1X01")
      (footprint "eagle-import:1X01")
      (libsource (lib "eagle-import") (part "1X01"))
    )
    (comp (ref "JP325")
      (value "1X01")
      (footprint "eagle-import:1X01")
      (libsource (lib "eagle-import") (part "1X01"))
    )
    (comp (ref "JP326")
      (value "1X01")
      (footprint "eagle-import:1X01")
      (libsource (lib "eagle-import") (part "1X01"))
    )
    (comp (ref "JP327")
      (value "1X01")
      (footprint "eagle-import:1X01")
      (libsource (lib "eagle-import") (part "1X01"))
    )
    (comp (ref "JP328")
      (value "1X01")
      (footprint "eagle-import:1X01")
      (libsource (lib "eagle-import") (part "1X01"))
    )
    (comp (ref "JP329")
      (value "1X01")
      (footprint "eagle-import:1X01")
      (libsource (lib "eagle-import") (part "1X01"))
    )
    (comp (ref "JP330")
      (value "1X01")
      (footprint "eagle-import:1X01")
      (libsource (lib "eagle-import") (part "1X01"))
    )
    (comp (ref "JP331")
      (value "1X01")
      (footprint "eagle-import:1X01")
      (libsource (lib "eagle-import") (part "1X01"))
    )
    (comp (ref "JP332")
      (value "1X01")
      (footprint "eagle-import:1X01")
      (libsource (lib "eagle-import") (part "1X01"))
    )
    (comp (ref "JP333")
      (value "1X01")
      (footprint "eagle-import:1X01")
      (libsource (lib "eagle-import") (part "1X01"))
    )
    (comp (ref "JP334")
      (value "1X01")
      (footprint "eagle-import:1X01")
      (libsource (lib "eagle-import") (part "1X01"))
    )
    (comp (ref "JP335")
      (value "1X01")
      (footprint "eagle-import:1X01")
      (libsource (lib "eagle-import") (part "1X01"))
    )
    (comp (ref "JP336")
      (value "1X01")
      (footprint "eagle-import:1X01")
      (libsource (lib "eagle-import") (part "1X01"))
    )
    (comp (ref "JP337")
      (value "1X01")
      (footprint "eagle-import:1X01")
      (libsource (lib "eagle-import") (part "1X01"))
    )
    (comp (ref "JP338")
      (value "1X01")
      (footprint "eagle-import:1X01")
      (libsource (lib "eagle-import") (part "1X01"))
    )
    (comp (ref "JP339")
      (value "1X01")
      (footprint "eagle-import:1X01")
      (libsource (lib "eagle-import") (part "1X01"))
    )
    (comp (ref "JP340")
      (value "1X01")
      (footprint "eagle-import:1X01")
      (libsource (lib "eagle-import") (part "1X01"))
    )
    (comp (ref "JP341")
      (value "1X01")
      (footprint "eagle-import:1X01")
      (libsource (lib "eagle-import") (part "1X01"))
    )
    (comp (ref "JP342")
      (value "1X01")
      (footprint "eagle-import:1X01")
      (libsource (lib "eagle-import") (part "1X01"))
    )
    (comp (ref "JP343")
      (value "1X01")
      (footprint "eagle-import:1X01")
      (libsource (lib "eagle-import") (part "1X01"))
    )
    (comp (ref "JP344")
      (value "1X01")
      (footprint "eagle-import:1X01")
      (libsource (lib "eagle-import") (part "1X01"))
    )
    (comp (ref "JP345")
      (value "1X01")
      (footprint "eagle-import:1X01")
      (libsource (lib "eagle-import") (part "1X01"))
    )
    (comp (ref "JP346")
      (value "1X01")
      (footprint "eagle-import:1X01")
      (libsource (lib "eagle-import") (part "1X01"))
    )
    (comp (ref "JP347")
      (value "1X01")
      (footprint "eagle-import:1X01")
      (libsource (lib "eagle-import") (part "1X01"))
    )
    (comp (ref "JP348")
      (value "1X01")
      (footprint "eagle-import:1X01")
      (libsource (lib "eagle-import") (part "1X01"))
    )
    (comp (ref "JP349")
      (value "1X01")
      (footprint "eagle-import:1X01")
      (libsource (lib "eagle-import") (part "1X01"))
    )
    (comp (ref "JP350")
      (value "1X01")
      (footprint "eagle-import:1X01")
      (libsource (lib "eagle-import") (part "1X01"))
    )
    (comp (ref "JP351")
      (value "1X01")
      (footprint "eagle-import:1X01")
      (libsource (lib "eagle-import") (part "1X01"))
    )
    (comp (ref "JP352")
      (value "1X01")
      (footprint "eagle-import:1X01")
      (libsource (lib "eagle-import") (part "1X01"))
    )
    (comp (ref "JP353")
      (value "1X01")
      (footprint "eagle-import:1X01")
      (libsource (lib "eagle-import") (part "1X01"))
    )
    (comp (ref "JP354")
      (value "1X01")
      (footprint "eagle-import:1X01")
      (libsource (lib "eagle-import") (part "1X01"))
    )
    (comp (ref "JP355")
      (value "1X01")
      (footprint "eagle-import:1X01")
      (libsource (lib "eagle-import") (part "1X01"))
    )
    (comp (ref "JP356")
      (value "1X01")
      (footprint "eagle-import:1X01")
      (libsource (lib "eagle-import") (part "1X01"))
    )
    (comp (ref "JP357")
      (value "1X01")
      (footprint "eagle-import:1X01")
      (libsource (lib "eagle-import") (part "1X01"))
    )
    (comp (ref "JP358")
      (value "1X01")
      (footprint "eagle-import:1X01")
      (libsource (lib "eagle-import") (part "1X01"))
    )
    (comp (ref "JP359")
      (value "1X01")
      (footprint "eagle-import:1X01")
      (libsource (lib "eagle-import") (part "1X01"))
    )
    (comp (ref "JP360")
      (value "1X01")
      (footprint "eagle-import:1X01")
      (libsource (lib "eagle-import") (part "1X01"))
    )
    (comp (ref "JP361")
      (value "1X01")
      (footprint "eagle-import:1X01")
      (libsource (lib "eagle-import") (part "1X01"))
    )
    (comp (ref "JP362")
      (value "1X01")
      (footprint "eagle-import:1X01")
      (libsource (lib "eagle-import") (part "1X01"))
    )
    (comp (ref "JP363")
      (value "1X01")
      (footprint "eagle-import:1X01")
      (libsource (lib "eagle-import") (part "1X01"))
    )
    (comp (ref "JP364")
      (value "1X01")
      (footprint "eagle-import:1X01")
      (libsource (lib "eagle-import") (part "1X01"))
    )
    (comp (ref "JP365")
      (value "1X01")
      (footprint "eagle-import:1X01")
      (libsource (lib "eagle-import") (part "1X01"))
    )
    (comp (ref "JP366")
      (value "1X01")
      (footprint "eagle-import:1X01")
      (libsource (lib "eagle-import") (part "1X01"))
    )
    (comp (ref "JP367")
      (value "1X01")
      (footprint "eagle-import:1X01")
      (libsource (lib "eagle-import") (part "1X01"))
    )
    (comp (ref "JP368")
      (value "1X01")
      (footprint "eagle-import:1X01")
      (libsource (lib "eagle-import") (part "1X01"))
    )
    (comp (ref "JP369")
      (value "1X01")
      (footprint "eagle-import:1X01")
      (libsource (lib "eagle-import") (part "1X01"))
    )
    (comp (ref "JP370")
      (value "1X01")
      (footprint "eagle-import:1X01")
      (libsource (lib "eagle-import") (part "1X01"))
    )
    (comp (ref "JP371")
      (value "1X01")
      (footprint "eagle-import:1X01")
      (libsource (lib "eagle-import") (part "1X01"))
    )
    (comp (ref "JP372")
      (value "1X01")
      (footprint "eagle-import:1X01")
      (libsource (lib "eagle-import") (part "1X01"))
    )
    (comp (ref "JP373")
      (value "1X01")
      (footprint "eagle-import:1X01")
      (libsource (lib "eagle-import") (part "1X01"))
    )
    (comp (ref "JP374")
      (value "1X01")
      (footprint "eagle-import:1X01")
      (libsource (lib "eagle-import") (part "1X01"))
    )
    (comp (ref "JP375")
      (value "1X01")
      (footprint "eagle-import:1X01")
      (libsource (lib "eagle-import") (part "1X01"))
    )
    (comp (ref "JP376")
      (value "1X01")
      (footprint "eagle-import:1X01")
      (libsource (lib "eagle-import") (part "1X01"))
    )
    (comp (ref "JP377")
      (value "1X01")
      (footprint "eagle-import:1X01")
      (libsource (lib "eagle-import") (part "1X01"))
    )
    (comp (ref "JP378")
      (value "1X01")
      (footprint "eagle-import:1X01")
      (libsource (lib "eagle-import") (part "1X01"))
    )
    (comp (ref "JP379")
      (value "1X01")
      (footprint "eagle-import:1X01")
      (libsource (lib "eagle-import") (part "1X01"))
    )
    (comp (ref "JP380")
      (value "1X01")
      (footprint "eagle-import:1X01")
      (libsource (lib "eagle-import") (part "1X01"))
    )
    (comp (ref "JP381")
      (value "1X01")
      (footprint "eagle-import:1X01")
      (libsource (lib "eagle-import") (part "1X01"))
    )
    (comp (ref "JP382")
      (value "1X01")
      (footprint "eagle-import:1X01")
      (libsource (lib "eagle-import") (part "1X01"))
    )
    (comp (ref "JP383")
      (value "1X01")
      (footprint "eagle-import:1X01")
      (libsource (lib "eagle-import") (part "1X01"))
    )
    (comp (ref "JP384")
      (value "1X01")
      (footprint "eagle-import:1X01")
      (libsource (lib "eagle-import") (part "1X01"))
    )
    (comp (ref "JP385")
      (value "1X01")
      (footprint "eagle-import:1X01")
      (libsource (lib "eagle-import") (part "1X01"))
    )
    (comp (ref "JP386")
      (value "1X01")
      (footprint "eagle-import:1X01")
      (libsource (lib "eagle-import") (part "1X01"))
    )
    (comp (ref "JP387")
      (value "1X01")
      (footprint "eagle-import:1X01")
      (libsource (lib "eagle-import") (part "1X01"))
    )
    (comp (ref "JP388")
      (value "1X01")
      (footprint "eagle-import:1X01")
      (libsource (lib "eagle-import") (part "1X01"))
    )
    (comp (ref "JP389")
      (value "1X01")
      (footprint "eagle-import:1X01")
      (libsource (lib "eagle-import") (part "1X01"))
    )
    (comp (ref "JP390")
      (value "1X01")
      (footprint "eagle-import:1X01")
      (libsource (lib "eagle-import") (part "1X01"))
    )
    (comp (ref "JP391")
      (value "1X01")
      (footprint "eagle-import:1X01")
      (libsource (lib "eagle-import") (part "1X01"))
    )
    (comp (ref "JP392")
      (value "1X01")
      (footprint "eagle-import:1X01")
      (libsource (lib "eagle-import") (part "1X01"))
    )
    (comp (ref "JP393")
      (value "1X01")
      (footprint "eagle-import:1X01")
      (libsource (lib "eagle-import") (part "1X01"))
    )
    (comp (ref "JP394")
      (value "1X01")
      (footprint "eagle-import:1X01")
      (libsource (lib "eagle-import") (part "1X01"))
    )
    (comp (ref "JP395")
      (value "1X01")
      (footprint "eagle-import:1X01")
      (libsource (lib "eagle-import") (part "1X01"))
    )
    (comp (ref "JP396")
      (value "1X01")
      (footprint "eagle-import:1X01")
      (libsource (lib "eagle-import") (part "1X01"))
    )
    (comp (ref "JP397")
      (value "1X01")
      (footprint "eagle-import:1X01")
      (libsource (lib "eagle-import") (part "1X01"))
    )
    (comp (ref "JP398")
      (value "1X01")
      (footprint "eagle-import:1X01")
      (libsource (lib "eagle-import") (part "1X01"))
    )
    (comp (ref "JP399")
      (value "1X01")
      (footprint "eagle-import:1X01")
      (libsource (lib "eagle-import") (part "1X01"))
    )
    (comp (ref "JP400")
      (value "1X01")
      (footprint "eagle-import:1X01")
      (libsource (lib "eagle-import") (part "1X01"))
    )
    (comp (ref "JP401")
      (value "1X01")
      (footprint "eagle-import:1X01")
      (libsource (lib "eagle-import") (part "1X01"))
    )
    (comp (ref "JP402")
      (value "1X01")
      (footprint "eagle-import:1X01")
      (libsource (lib "eagle-import") (part "1X01"))
    )
    (comp (ref "JP403")
      (value "1X01")
      (footprint "eagle-import:1X01")
      (libsource (lib "eagle-import") (part "1X01"))
    )
    (comp (ref "JP404")
      (value "1X01")
      (footprint "eagle-import:1X01")
      (libsource (lib "eagle-import") (part "1X01"))
    )
    (comp (ref "JP405")
      (value "1X01")
      (footprint "eagle-import:1X01")
      (libsource (lib "eagle-import") (part "1X01"))
    )
    (comp (ref "JP406")
      (value "1X01")
      (footprint "eagle-import:1X01")
      (libsource (lib "eagle-import") (part "1X01"))
    )
    (comp (ref "JP407")
      (value "1X01")
      (footprint "eagle-import:1X01")
      (libsource (lib "eagle-import") (part "1X01"))
    )
    (comp (ref "JP408")
      (value "1X01")
      (footprint "eagle-import:1X01")
      (libsource (lib "eagle-import") (part "1X01"))
    )
    (comp (ref "JP409")
      (value "1X01")
      (footprint "eagle-import:1X01")
      (libsource (lib "eagle-import") (part "1X01"))
    )
    (comp (ref "JP410")
      (value "1X01")
      (footprint "eagle-import:1X01")
      (libsource (lib "eagle-import") (part "1X01"))
    )
    (comp (ref "JP411")
      (value "1X01")
      (footprint "eagle-import:1X01")
      (libsource (lib "eagle-import") (part "1X01"))
    )
    (comp (ref "JP412")
      (value "1X01")
      (footprint "eagle-import:1X01")
      (libsource (lib "eagle-import") (part "1X01"))
    )
    (comp (ref "JP413")
      (value "1X01")
      (footprint "eagle-import:1X01")
      (libsource (lib "eagle-import") (part "1X01"))
    )
    (comp (ref "JP414")
      (value "1X01")
      (footprint "eagle-import:1X01")
      (libsource (lib "eagle-import") (part "1X01"))
    )
    (comp (ref "JP415")
      (value "1X01")
      (footprint "eagle-import:1X01")
      (libsource (lib "eagle-import") (part "1X01"))
    )
    (comp (ref "JP416")
      (value "1X01")
      (footprint "eagle-import:1X01")
      (libsource (lib "eagle-import") (part "1X01"))
    )
    (comp (ref "JP417")
      (value "1X01")
      (footprint "eagle-import:1X01")
      (libsource (lib "eagle-import") (part "1X01"))
    )
    (comp (ref "JP418")
      (value "1X01")
      (footprint "eagle-import:1X01")
      (libsource (lib "eagle-import") (part "1X01"))
    )
    (comp (ref "JP419")
      (value "1X01")
      (footprint "eagle-import:1X01")
      (libsource (lib "eagle-import") (part "1X01"))
    )
    (comp (ref "JP420")
      (value "1X01")
      (footprint "eagle-import:1X01")
      (libsource (lib "eagle-import") (part "1X01"))
    )
    (comp (ref "JP421")
      (value "1X01")
      (footprint "eagle-import:1X01")
      (libsource (lib "eagle-import") (part "1X01"))
    )
    (comp (ref "JP422")
      (value "1X01")
      (footprint "eagle-import:1X01")
      (libsource (lib "eagle-import") (part "1X01"))
    )
    (comp (ref "JP423")
      (value "1X01")
      (footprint "eagle-import:1X01")
      (libsource (lib "eagle-import") (part "1X01"))
    )
    (comp (ref "JP424")
      (value "1X01")
      (footprint "eagle-import:1X01")
      (libsource (lib "eagle-import") (part "1X01"))
    )
    (comp (ref "JP425")
      (value "1X01")
      (footprint "eagle-import:1X01")
      (libsource (lib "eagle-import") (part "1X01"))
    )
    (comp (ref "JP426")
      (value "1X01")
      (footprint "eagle-import:1X01")
      (libsource (lib "eagle-import") (part "1X01"))
    )
    (comp (ref "JP427")
      (value "1X01")
      (footprint "eagle-import:1X01")
      (libsource (lib "eagle-import") (part "1X01"))
    )
    (comp (ref "JP428")
      (value "1X01")
      (footprint "eagle-import:1X01")
      (libsource (lib "eagle-import") (part "1X01"))
    )
    (comp (ref "JP429")
      (value "1X01")
      (footprint "eagle-import:1X01")
      (libsource (lib "eagle-import") (part "1X01"))
    )
    (comp (ref "JP430")
      (value "1X01")
      (footprint "eagle-import:1X01")
      (libsource (lib "eagle-import") (part "1X01"))
    )
    (comp (ref "JP431")
      (value "1X01")
      (footprint "eagle-import:1X01")
      (libsource (lib "eagle-import") (part "1X01"))
    )
    (comp (ref "JP432")
      (value "1X01")
      (footprint "eagle-import:1X01")
      (libsource (lib "eagle-import") (part "1X01"))
    )
    (comp (ref "JP433")
      (value "1X01")
      (footprint "eagle-import:1X01")
      (libsource (lib "eagle-import") (part "1X01"))
    )
    (comp (ref "JP434")
      (value "1X01")
      (footprint "eagle-import:1X01")
      (libsource (lib "eagle-import") (part "1X01"))
    )
    (comp (ref "JP435")
      (value "1X01")
      (footprint "eagle-import:1X01")
      (libsource (lib "eagle-import") (part "1X01"))
    )
    (comp (ref "JP436")
      (value "1X01")
      (footprint "eagle-import:1X01")
      (libsource (lib "eagle-import") (part "1X01"))
    )
    (comp (ref "JP437")
      (value "1X01")
      (footprint "eagle-import:1X01")
      (libsource (lib "eagle-import") (part "1X01"))
    )
    (comp (ref "JP438")
      (value "1X01")
      (footprint "eagle-import:1X01")
      (libsource (lib "eagle-import") (part "1X01"))
    )
    (comp (ref "JP439")
      (value "1X01")
      (footprint "eagle-import:1X01")
      (libsource (lib "eagle-import") (part "1X01"))
    )
    (comp (ref "JP440")
      (value "1X01")
      (footprint "eagle-import:1X01")
      (libsource (lib "eagle-import") (part "1X01"))
    )
    (comp (ref "JP441")
      (value "1X01")
      (footprint "eagle-import:1X01")
      (libsource (lib "eagle-import") (part "1X01"))
    )
    (comp (ref "JP442")
      (value "1X01")
      (footprint "eagle-import:1X01")
      (libsource (lib "eagle-import") (part "1X01"))
    )
    (comp (ref "JP443")
      (value "1X01")
      (footprint "eagle-import:1X01")
      (libsource (lib "eagle-import") (part "1X01"))
    )
    (comp (ref "JP444")
      (value "1X01")
      (footprint "eagle-import:1X01")
      (libsource (lib "eagle-import") (part "1X01"))
    )
    (comp (ref "JP445")
      (value "1X01")
      (footprint "eagle-import:1X01")
      (libsource (lib "eagle-import") (part "1X01"))
    )
    (comp (ref "JP446")
      (value "1X01")
      (footprint "eagle-import:1X01")
      (libsource (lib "eagle-import") (part "1X01"))
    )
    (comp (ref "JP447")
      (value "1X01")
      (footprint "eagle-import:1X01")
      (libsource (lib "eagle-import") (part "1X01"))
    )
    (comp (ref "JP448")
      (value "1X01")
      (footprint "eagle-import:1X01")
      (libsource (lib "eagle-import") (part "1X01"))
    )
    (comp (ref "JP449")
      (value "1X01")
      (footprint "eagle-import:1X01")
      (libsource (lib "eagle-import") (part "1X01"))
    )
    (comp (ref "JP450")
      (value "1X01")
      (footprint "eagle-import:1X01")
      (libsource (lib "eagle-import") (part "1X01"))
    )
    (comp (ref "JP451")
      (value "1X01")
      (footprint "eagle-import:1X01")
      (libsource (lib "eagle-import") (part "1X01"))
    )
    (comp (ref "JP452")
      (value "1X01")
      (footprint "eagle-import:1X01")
      (libsource (lib "eagle-import") (part "1X01"))
    )
    (comp (ref "JP453")
      (value "1X01")
      (footprint "eagle-import:1X01")
      (libsource (lib "eagle-import") (part "1X01"))
    )
    (comp (ref "JP454")
      (value "1X01")
      (footprint "eagle-import:1X01")
      (libsource (lib "eagle-import") (part "1X01"))
    )
    (comp (ref "JP455")
      (value "1X01")
      (footprint "eagle-import:1X01")
      (libsource (lib "eagle-import") (part "1X01"))
    )
    (comp (ref "JP456")
      (value "1X01")
      (footprint "eagle-import:1X01")
      (libsource (lib "eagle-import") (part "1X01"))
    )
    (comp (ref "JP457")
      (value "1X01")
      (footprint "eagle-import:1X01")
      (libsource (lib "eagle-import") (part "1X01"))
    )
    (comp (ref "JP458")
      (value "1X01")
      (footprint "eagle-import:1X01")
      (libsource (lib "eagle-import") (part "1X01"))
    )
    (comp (ref "JP459")
      (value "1X01")
      (footprint "eagle-import:1X01")
      (libsource (lib "eagle-import") (part "1X01"))
    )
    (comp (ref "JP460")
      (value "1X01")
      (footprint "eagle-import:1X01")
      (libsource (lib "eagle-import") (part "1X01"))
    )
    (comp (ref "JP461")
      (value "1X01")
      (footprint "eagle-import:1X01")
      (libsource (lib "eagle-import") (part "1X01"))
    )
    (comp (ref "JP462")
      (value "1X01")
      (footprint "eagle-import:1X01")
      (libsource (lib "eagle-import") (part "1X01"))
    )
    (comp (ref "JP463")
      (value "1X01")
      (footprint "eagle-import:1X01")
      (libsource (lib "eagle-import") (part "1X01"))
    )
    (comp (ref "JP464")
      (value "1X01")
      (footprint "eagle-import:1X01")
      (libsource (lib "eagle-import") (part "1X01"))
    )
    (comp (ref "JP465")
      (value "1X01")
      (footprint "eagle-import:1X01")
      (libsource (lib "eagle-import") (part "1X01"))
    )
    (comp (ref "JP466")
      (value "1X01")
      (footprint "eagle-import:1X01")
      (libsource (lib "eagle-import") (part "1X01"))
    )
    (comp (ref "JP467")
      (value "1X01")
      (footprint "eagle-import:1X01")
      (libsource (lib "eagle-import") (part "1X01"))
    )
    (comp (ref "JP468")
      (value "1X01")
      (footprint "eagle-import:1X01")
      (libsource (lib "eagle-import") (part "1X01"))
    )
    (comp (ref "JP469")
      (value "1X01")
      (footprint "eagle-import:1X01")
      (libsource (lib "eagle-import") (part "1X01"))
    )
    (comp (ref "JP470")
      (value "1X01")
      (footprint "eagle-import:1X01")
      (libsource (lib "eagle-import") (part "1X01"))
    )
    (comp (ref "JP471")
      (value "1X01")
      (footprint "eagle-import:1X01")
      (libsource (lib "eagle-import") (part "1X01"))
    )
    (comp (ref "JP472")
      (value "1X01")
      (footprint "eagle-import:1X01")
      (libsource (lib "eagle-import") (part "1X01"))
    )
    (comp (ref "JP473")
      (value "1X01")
      (footprint "eagle-import:1X01")
      (libsource (lib "eagle-import") (part "1X01"))
    )
    (comp (ref "JP474")
      (value "1X01")
      (footprint "eagle-import:1X01")
      (libsource (lib "eagle-import") (part "1X01"))
    )
    (comp (ref "JP475")
      (value "1X01")
      (footprint "eagle-import:1X01")
      (libsource (lib "eagle-import") (part "1X01"))
    )
    (comp (ref "JP476")
      (value "1X01")
      (footprint "eagle-import:1X01")
      (libsource (lib "eagle-import") (part "1X01"))
    )
    (comp (ref "JP477")
      (value "1X01")
      (footprint "eagle-import:1X01")
      (libsource (lib "eagle-import") (part "1X01"))
    )
    (comp (ref "JP478")
      (value "1X01")
      (footprint "eagle-import:1X01")
      (libsource (lib "eagle-import") (part "1X01"))
    )
    (comp (ref "JP479")
      (value "1X01")
      (footprint "eagle-import:1X01")
      (libsource (lib "eagle-import") (part "1X01"))
    )
    (comp (ref "JP480")
      (value "1X01")
      (footprint "eagle-import:1X01")
      (libsource (lib "eagle-import") (part "1X01"))
    )
    (comp (ref "JP481")
      (value "1X01")
      (footprint "eagle-import:1X01")
      (libsource (lib "eagle-import") (part "1X01"))
    )
    (comp (ref "JP482")
      (value "1X01")
      (footprint "eagle-import:1X01")
      (libsource (lib "eagle-import") (part "1X01"))
    )
    (comp (ref "JP483")
      (value "1X01")
      (footprint "eagle-import:1X01")
      (libsource (lib "eagle-import") (part "1X01"))
    )
    (comp (ref "JP484")
      (value "1X01")
      (footprint "eagle-import:1X01")
      (libsource (lib "eagle-import") (part "1X01"))
    )
    (comp (ref "JP485")
      (value "1X01")
      (footprint "eagle-import:1X01")
      (libsource (lib "eagle-import") (part "1X01"))
    )
    (comp (ref "JP486")
      (value "1X01")
      (footprint "eagle-import:1X01")
      (libsource (lib "eagle-import") (part "1X01"))
    )
    (comp (ref "JP487")
      (value "1X01")
      (footprint "eagle-import:1X01")
      (libsource (lib "eagle-import") (part "1X01"))
    )
    (comp (ref "JP488")
      (value "1X01")
      (footprint "eagle-import:1X01")
      (libsource (lib "eagle-import") (part "1X01"))
    )
    (comp (ref "JP489")
      (value "1X01")
      (footprint "eagle-import:1X01")
      (libsource (lib "eagle-import") (part "1X01"))
    )
    (comp (ref "JP490")
      (value "1X01")
      (footprint "eagle-import:1X01")
      (libsource (lib "eagle-import") (part "1X01"))
    )
    (comp (ref "JP491")
      (value "1X01")
      (footprint "eagle-import:1X01")
      (libsource (lib "eagle-import") (part "1X01"))
    )
    (comp (ref "JP492")
      (value "1X01")
      (footprint "eagle-import:1X01")
      (libsource (lib "eagle-import") (part "1X01"))
    )
    (comp (ref "JP493")
      (value "1X01")
      (footprint "eagle-import:1X01")
      (libsource (lib "eagle-import") (part "1X01"))
    )
    (comp (ref "JP494")
      (value "1X01")
      (footprint "eagle-import:1X01")
      (libsource (lib "eagle-import") (part "1X01"))
    )
    (comp (ref "JP495")
      (value "1X01")
      (footprint "eagle-import:1X01")
      (libsource (lib "eagle-import") (part "1X01"))
    )
    (comp (ref "JP496")
      (value "1X01")
      (footprint "eagle-import:1X01")
      (libsource (lib "eagle-import") (part "1X01"))
    )
    (comp (ref "JP497")
      (value "1X01")
      (footprint "eagle-import:1X01")
      (libsource (lib "eagle-import") (part "1X01"))
    )
    (comp (ref "JP498")
      (value "1X01")
      (footprint "eagle-import:1X01")
      (libsource (lib "eagle-import") (part "1X01"))
    )
    (comp (ref "JP499")
      (value "1X01")
      (footprint "eagle-import:1X01")
      (libsource (lib "eagle-import") (part "1X01"))
    )
    (comp (ref "JP500")
      (value "1X01")
      (footprint "eagle-import:1X01")
      (libsource (lib "eagle-import") (part "1X01"))
    )
    (comp (ref "JP501")
      (value "1X01")
      (footprint "eagle-import:1X01")
      (libsource (lib "eagle-import") (part "1X01"))
    )
    (comp (ref "JP502")
      (value "1X01")
      (footprint "eagle-import:1X01")
      (libsource (lib "eagle-import") (part "1X01"))
    )
    (comp (ref "JP503")
      (value "1X01")
      (footprint "eagle-import:1X01")
      (libsource (lib "eagle-import") (part "1X01"))
    )
    (comp (ref "JP504")
      (value "1X01")
      (footprint "eagle-import:1X01")
      (libsource (lib "eagle-import") (part "1X01"))
    )
    (comp (ref "JP505")
      (value "1X01")
      (footprint "eagle-import:1X01")
      (libsource (lib "eagle-import") (part "1X01"))
    )
    (comp (ref "JP506")
      (value "1X01")
      (footprint "eagle-import:1X01")
      (libsource (lib "eagle-import") (part "1X01"))
    )
    (comp (ref "JP507")
      (value "1X01")
      (footprint "eagle-import:1X01")
      (libsource (lib "eagle-import") (part "1X01"))
    )
    (comp (ref "JP508")
      (value "1X01")
      (footprint "eagle-import:1X01")
      (libsource (lib "eagle-import") (part "1X01"))
    )
    (comp (ref "JP509")
      (value "1X01")
      (footprint "eagle-import:1X01")
      (libsource (lib "eagle-import") (part "1X01"))
    )
    (comp (ref "JP510")
      (value "1X01")
      (footprint "eagle-import:1X01")
      (libsource (lib "eagle-import") (part "1X01"))
    )
    (comp (ref "JP511")
      (value "1X01")
      (footprint "eagle-import:1X01")
      (libsource (lib "eagle-import") (part "1X01"))
    )
    (comp (ref "JP512")
      (value "1X01")
      (footprint "eagle-import:1X01")
      (libsource (lib "eagle-import") (part "1X01"))
    )
    (comp (ref "JP513")
      (value "1X01")
      (footprint "eagle-import:1X01")
      (libsource (lib "eagle-import") (part "1X01"))
    )
    (comp (ref "JP514")
      (value "1X01")
      (footprint "eagle-import:1X01")
      (libsource (lib "eagle-import") (part "1X01"))
    )
    (comp (ref "JP515")
      (value "1X01")
      (footprint "eagle-import:1X01")
      (libsource (lib "eagle-import") (part "1X01"))
    )
    (comp (ref "JP516")
      (value "1X01")
      (footprint "eagle-import:1X01")
      (libsource (lib "eagle-import") (part "1X01"))
    )
    (comp (ref "JP517")
      (value "1X01")
      (footprint "eagle-import:1X01")
      (libsource (lib "eagle-import") (part "1X01"))
    )
    (comp (ref "JP518")
      (value "1X01")
      (footprint "eagle-import:1X01")
      (libsource (lib "eagle-import") (part "1X01"))
    )
    (comp (ref "JP519")
      (value "1X01")
      (footprint "eagle-import:1X01")
      (libsource (lib "eagle-import") (part "1X01"))
    )
    (comp (ref "JP520")
      (value "1X01")
      (footprint "eagle-import:1X01")
      (libsource (lib "eagle-import") (part "1X01"))
    )
    (comp (ref "JP521")
      (value "1X01")
      (footprint "eagle-import:1X01")
      (libsource (lib "eagle-import") (part "1X01"))
    )
    (comp (ref "JP522")
      (value "1X01")
      (footprint "eagle-import:1X01")
      (libsource (lib "eagle-import") (part "1X01"))
    )
    (comp (ref "JP523")
      (value "1X01")
      (footprint "eagle-import:1X01")
      (libsource (lib "eagle-import") (part "1X01"))
    )
    (comp (ref "JP524")
      (value "1X01")
      (footprint "eagle-import:1X01")
      (libsource (lib "eagle-import") (part "1X01"))
    )
    (comp (ref "JP525")
      (value "1X01")
      (footprint "eagle-import:1X01")
      (libsource (lib "eagle-import") (part "1X01"))
    )
    (comp (ref "JP526")
      (value "1X01")
      (footprint "eagle-import:1X01")
      (libsource (lib "eagle-import") (part "1X01"))
    )
    (comp (ref "JP527")
      (value "1X01")
      (footprint "eagle-import:1X01")
      (libsource (lib "eagle-import") (part "1X01"))
    )
    (comp (ref "JP528")
      (value "1X01")
      (footprint "eagle-import:1X01")
      (libsource (lib "eagle-import") (part "1X01"))
    )
    (comp (ref "JP529")
      (value "1X01")
      (footprint "eagle-import:1X01")
      (libsource (lib "eagle-import") (part "1X01"))
    )
    (comp (ref "JP530")
      (value "1X01")
      (footprint "eagle-import:1X01")
      (libsource (lib "eagle-import") (part "1X01"))
    )
    (comp (ref "JP531")
      (value "1X01")
      (footprint "eagle-import:1X01")
      (libsource (lib "eagle-import") (part "1X01"))
    )
    (comp (ref "JP532")
      (value "1X01")
      (footprint "eagle-import:1X01")
      (libsource (lib "eagle-import") (part "1X01"))
    )
    (comp (ref "JP533")
      (value "1X01")
      (footprint "eagle-import:1X01")
      (libsource (lib "eagle-import") (part "1X01"))
    )
    (comp (ref "JP534")
      (value "1X01")
      (footprint "eagle-import:1X01")
      (libsource (lib "eagle-import") (part "1X01"))
    )
    (comp (ref "JP535")
      (value "1X01")
      (footprint "eagle-import:1X01")
      (libsource (lib "eagle-import") (part "1X01"))
    )
    (comp (ref "JP536")
      (value "1X01")
      (footprint "eagle-import:1X01")
      (libsource (lib "eagle-import") (part "1X01"))
    )
    (comp (ref "JP537")
      (value "1X01")
      (footprint "eagle-import:1X01")
      (libsource (lib "eagle-import") (part "1X01"))
    )
    (comp (ref "JP538")
      (value "1X01")
      (footprint "eagle-import:1X01")
      (libsource (lib "eagle-import") (part "1X01"))
    )
    (comp (ref "JP539")
      (value "1X01")
      (footprint "eagle-import:1X01")
      (libsource (lib "eagle-import") (part "1X01"))
    )
    (comp (ref "JP540")
      (value "1X01")
      (footprint "eagle-import:1X01")
      (libsource (lib "eagle-import") (part "1X01"))
    )
    (comp (ref "JP541")
      (value "1X01")
      (footprint "eagle-import:1X01")
      (libsource (lib "eagle-import") (part "1X01"))
    )
    (comp (ref "JP542")
      (value "1X01")
      (footprint "eagle-import:1X01")
      (libsource (lib "eagle-import") (part "1X01"))
    )
    (comp (ref "JP543")
      (value "1X01")
      (footprint "eagle-import:1X01")
      (libsource (lib "eagle-import") (part "1X01"))
    )
    (comp (ref "JP544")
      (value "1X01")
      (footprint "eagle-import:1X01")
      (libsource (lib "eagle-import") (part "1X01"))
    )
    (comp (ref "JP545")
      (value "1X01")
      (footprint "eagle-import:1X01")
      (libsource (lib "eagle-import") (part "1X01"))
    )
    (comp (ref "JP546")
      (value "1X01")
      (footprint "eagle-import:1X01")
      (libsource (lib "eagle-import") (part "1X01"))
    )
    (comp (ref "JP547")
      (value "1X01")
      (footprint "eagle-import:1X01")
      (libsource (lib "eagle-import") (part "1X01"))
    )
    (comp (ref "JP548")
      (value "1X01")
      (footprint "eagle-import:1X01")
      (libsource (lib "eagle-import") (part "1X01"))
    )
    (comp (ref "JP549")
      (value "1X01")
      (footprint "eagle-import:1X01")
      (libsource (lib "eagle-import") (part "1X01"))
    )
    (comp (ref "JP550")
      (value "1X01")
      (footprint "eagle-import:1X01")
      (libsource (lib "eagle-import") (part "1X01"))
    )
    (comp (ref "JP551")
      (value "1X01")
      (footprint "eagle-import:1X01")
      (libsource (lib "eagle-import") (part "1X01"))
    )
    (comp (ref "JP552")
      (value "1X01")
      (footprint "eagle-import:1X01")
      (libsource (lib "eagle-import") (part "1X01"))
    )
    (comp (ref "JP553")
      (value "1X01")
      (footprint "eagle-import:1X01")
      (libsource (lib "eagle-import") (part "1X01"))
    )
    (comp (ref "JP554")
      (value "1X01")
      (footprint "eagle-import:1X01")
      (libsource (lib "eagle-import") (part "1X01"))
    )
    (comp (ref "JP555")
      (value "1X01")
      (footprint "eagle-import:1X01")
      (libsource (lib "eagle-import") (part "1X01"))
    )
    (comp (ref "JP556")
      (value "1X01")
      (footprint "eagle-import:1X01")
      (libsource (lib "eagle-import") (part "1X01"))
    )
    (comp (ref "JP557")
      (value "1X01")
      (footprint "eagle-import:1X01")
      (libsource (lib "eagle-import") (part "1X01"))
    )
    (comp (ref "JP558")
      (value "1X01")
      (footprint "eagle-import:1X01")
      (libsource (lib "eagle-import") (part "1X01"))
    )
    (comp (ref "JP559")
      (value "1X01")
      (footprint "eagle-import:1X01")
      (libsource (lib "eagle-import") (part "1X01"))
    )
    (comp (ref "JP560")
      (value "1X01")
      (footprint "eagle-import:1X01")
      (libsource (lib "eagle-import") (part "1X01"))
    )
    (comp (ref "JP561")
      (value "1X01")
      (footprint "eagle-import:1X01")
      (libsource (lib "eagle-import") (part "1X01"))
    )
    (comp (ref "JP562")
      (value "1X01")
      (footprint "eagle-import:1X01")
      (libsource (lib "eagle-import") (part "1X01"))
    )
    (comp (ref "JP563")
      (value "1X01")
      (footprint "eagle-import:1X01")
      (libsource (lib "eagle-import") (part "1X01"))
    )
    (comp (ref "JP564")
      (value "1X01")
      (footprint "eagle-import:1X01")
      (libsource (lib "eagle-import") (part "1X01"))
    )
    (comp (ref "JP565")
      (value "1X01")
      (footprint "eagle-import:1X01")
      (libsource (lib "eagle-import") (part "1X01"))
    )
    (comp (ref "JP566")
      (value "1X01")
      (footprint "eagle-import:1X01")
      (libsource (lib "eagle-import") (part "1X01"))
    )
    (comp (ref "JP567")
      (value "1X01")
      (footprint "eagle-import:1X01")
      (libsource (lib "eagle-import") (part "1X01"))
    )
    (comp (ref "JP568")
      (value "1X01")
      (footprint "eagle-import:1X01")
      (libsource (lib "eagle-import") (part "1X01"))
    )
    (comp (ref "JP569")
      (value "1X01")
      (footprint "eagle-import:1X01")
      (libsource (lib "eagle-import") (part "1X01"))
    )
    (comp (ref "JP570")
      (value "1X01")
      (footprint "eagle-import:1X01")
      (libsource (lib "eagle-import") (part "1X01"))
    )
    (comp (ref "JP571")
      (value "1X01")
      (footprint "eagle-import:1X01")
      (libsource (lib "eagle-import") (part "1X01"))
    )
    (comp (ref "JP572")
      (value "1X01")
      (footprint "eagle-import:1X01")
      (libsource (lib "eagle-import") (part "1X01"))
    )
    (comp (ref "JP573")
      (value "1X01")
      (footprint "eagle-import:1X01")
      (libsource (lib "eagle-import") (part "1X01"))
    )
    (comp (ref "JP574")
      (value "1X01")
      (footprint "eagle-import:1X01")
      (libsource (lib "eagle-import") (part "1X01"))
    )
    (comp (ref "JP575")
      (value "1X01")
      (footprint "eagle-import:1X01")
      (libsource (lib "eagle-import") (part "1X01"))
    )
    (comp (ref "JP576")
      (value "1X01")
      (footprint "eagle-import:1X01")
      (libsource (lib "eagle-import") (part "1X01"))
    )
    (comp (ref "JP577")
      (value "1X01")
      (footprint "eagle-import:1X01")
      (libsource (lib "eagle-import") (part "1X01"))
    )
    (comp (ref "JP578")
      (value "1X01")
      (footprint "eagle-import:1X01")
      (libsource (lib "eagle-import") (part "1X01"))
    )
    (comp (ref "JP579")
      (value "1X01")
      (footprint "eagle-import:1X01")
      (libsource (lib "eagle-import") (part "1X01"))
    )
    (comp (ref "JP580")
      (value "1X01")
      (footprint "eagle-import:1X01")
      (libsource (lib "eagle-import") (part "1X01"))
    )
    (comp (ref "JP581")
      (value "1X01")
      (footprint "eagle-import:1X01")
      (libsource (lib "eagle-import") (part "1X01"))
    )
    (comp (ref "JP582")
      (value "1X01")
      (footprint "eagle-import:1X01")
      (libsource (lib "eagle-import") (part "1X01"))
    )
    (comp (ref "JP583")
      (value "1X01")
      (footprint "eagle-import:1X01")
      (libsource (lib "eagle-import") (part "1X01"))
    )
    (comp (ref "JP584")
      (value "1X01")
      (footprint "eagle-import:1X01")
      (libsource (lib "eagle-import") (part "1X01"))
    )
    (comp (ref "JP585")
      (value "1X01")
      (footprint "eagle-import:1X01")
      (libsource (lib "eagle-import") (part "1X01"))
    )
    (comp (ref "JP586")
      (value "1X01")
      (footprint "eagle-import:1X01")
      (libsource (lib "eagle-import") (part "1X01"))
    )
    (comp (ref "JP587")
      (value "1X01")
      (footprint "eagle-import:1X01")
      (libsource (lib "eagle-import") (part "1X01"))
    )
    (comp (ref "JP588")
      (value "1X01")
      (footprint "eagle-import:1X01")
      (libsource (lib "eagle-import") (part "1X01"))
    )
    (comp (ref "JP589")
      (value "1X01")
      (footprint "eagle-import:1X01")
      (libsource (lib "eagle-import") (part "1X01"))
    )
    (comp (ref "JP590")
      (value "1X01")
      (footprint "eagle-import:1X01")
      (libsource (lib "eagle-import") (part "1X01"))
    )
    (comp (ref "JP591")
      (value "1X01")
      (footprint "eagle-import:1X01")
      (libsource (lib "eagle-import") (part "1X01"))
    )
    (comp (ref "JP592")
      (value "1X01")
      (footprint "eagle-import:1X01")
      (libsource (lib "eagle-import") (part "1X01"))
    )
    (comp (ref "JP593")
      (value "1X01")
      (footprint "eagle-import:1X01")
      (libsource (lib "eagle-import") (part "1X01"))
    )
    (comp (ref "JP594")
      (value "1X01")
      (footprint "eagle-import:1X01")
      (libsource (lib "eagle-import") (part "1X01"))
    )
    (comp (ref "JP595")
      (value "1X01")
      (footprint "eagle-import:1X01")
      (libsource (lib "eagle-import") (part "1X01"))
    )
    (comp (ref "JP596")
      (value "1X01")
      (footprint "eagle-import:1X01")
      (libsource (lib "eagle-import") (part "1X01"))
    )
    (comp (ref "JP597")
      (value "1X01")
      (footprint "eagle-import:1X01")
      (libsource (lib "eagle-import") (part "1X01"))
    )
    (comp (ref "JP598")
      (value "1X01")
      (footprint "eagle-import:1X01")
      (libsource (lib "eagle-import") (part "1X01"))
    )
    (comp (ref "JP599")
      (value "1X01")
      (footprint "eagle-import:1X01")
      (libsource (lib "eagle-import") (part "1X01"))
    )
    (comp (ref "JP600")
      (value "1X01")
      (footprint "eagle-import:1X01")
      (libsource (lib "eagle-import") (part "1X01"))
    )
    (comp (ref "JP601")
      (value "1X01")
      (footprint "eagle-import:1X01")
      (libsource (lib "eagle-import") (part "1X01"))
    )
    (comp (ref "JP602")
      (value "1X01")
      (footprint "eagle-import:1X01")
      (libsource (lib "eagle-import") (part "1X01"))
    )
    (comp (ref "JP603")
      (value "1X01")
      (footprint "eagle-import:1X01")
      (libsource (lib "eagle-import") (part "1X01"))
    )
    (comp (ref "JP604")
      (value "1X01")
      (footprint "eagle-import:1X01")
      (libsource (lib "eagle-import") (part "1X01"))
    )
    (comp (ref "JP605")
      (value "1X01")
      (footprint "eagle-import:1X01")
      (libsource (lib "eagle-import") (part "1X01"))
    )
    (comp (ref "JP606")
      (value "1X01")
      (footprint "eagle-import:1X01")
      (libsource (lib "eagle-import") (part "1X01"))
    )
    (comp (ref "JP607")
      (value "1X01")
      (footprint "eagle-import:1X01")
      (libsource (lib "eagle-import") (part "1X01"))
    )
    (comp (ref "JP608")
      (value "1X01")
      (footprint "eagle-import:1X01")
      (libsource (lib "eagle-import") (part "1X01"))
    )
    (comp (ref "JP609")
      (value "1X01")
      (footprint "eagle-import:1X01")
      (libsource (lib "eagle-import") (part "1X01"))
    )
    (comp (ref "JP610")
      (value "1X01")
      (footprint "eagle-import:1X01")
      (libsource (lib "eagle-import") (part "1X01"))
    )
    (comp (ref "JP611")
      (value "1X01")
      (footprint "eagle-import:1X01")
      (libsource (lib "eagle-import") (part "1X01"))
    )
    (comp (ref "JP612")
      (value "1X01")
      (footprint "eagle-import:1X01")
      (libsource (lib "eagle-import") (part "1X01"))
    )
    (comp (ref "JP613")
      (value "1X01")
      (footprint "eagle-import:1X01")
      (libsource (lib "eagle-import") (part "1X01"))
    )
    (comp (ref "JP614")
      (value "1X01")
      (footprint "eagle-import:1X01")
      (libsource (lib "eagle-import") (part "1X01"))
    )
    (comp (ref "JP615")
      (value "1X01")
      (footprint "eagle-import:1X01")
      (libsource (lib "eagle-import") (part "1X01"))
    )
    (comp (ref "JP616")
      (value "1X01")
      (footprint "eagle-import:1X01")
      (libsource (lib "eagle-import") (part "1X01"))
    )
    (comp (ref "JP617")
      (value "1X01")
      (footprint "eagle-import:1X01")
      (libsource (lib "eagle-import") (part "1X01"))
    )
    (comp (ref "JP618")
      (value "1X01")
      (footprint "eagle-import:1X01")
      (libsource (lib "eagle-import") (part "1X01"))
    )
    (comp (ref "JP619")
      (value "1X01")
      (footprint "eagle-import:1X01")
      (libsource (lib "eagle-import") (part "1X01"))
    )
    (comp (ref "JP620")
      (value "1X01")
      (footprint "eagle-import:1X01")
      (libsource (lib "eagle-import") (part "1X01"))
    )
    (comp (ref "JP621")
      (value "1X01")
      (footprint "eagle-import:1X01")
      (libsource (lib "eagle-import") (part "1X01"))
    )
    (comp (ref "JP622")
      (value "1X01")
      (footprint "eagle-import:1X01")
      (libsource (lib "eagle-import") (part "1X01"))
    )
    (comp (ref "JP623")
      (value "1X01")
      (footprint "eagle-import:1X01")
      (libsource (lib "eagle-import") (part "1X01"))
    )
    (comp (ref "JP624")
      (value "1X01")
      (footprint "eagle-import:1X01")
      (libsource (lib "eagle-import") (part "1X01"))
    )
    (comp (ref "JP625")
      (value "1X01")
      (footprint "eagle-import:1X01")
      (libsource (lib "eagle-import") (part "1X01"))
    )
    (comp (ref "JP626")
      (value "1X01")
      (footprint "eagle-import:1X01")
      (libsource (lib "eagle-import") (part "1X01"))
    )
    (comp (ref "JP627")
      (value "1X01")
      (footprint "eagle-import:1X01")
      (libsource (lib "eagle-import") (part "1X01"))
    )
    (comp (ref "JP628")
      (value "1X01")
      (footprint "eagle-import:1X01")
      (libsource (lib "eagle-import") (part "1X01"))
    )
    (comp (ref "JP629")
      (value "1X01")
      (footprint "eagle-import:1X01")
      (libsource (lib "eagle-import") (part "1X01"))
    )
    (comp (ref "JP630")
      (value "1X01")
      (footprint "eagle-import:1X01")
      (libsource (lib "eagle-import") (part "1X01"))
    )
    (comp (ref "JP631")
      (value "1X01")
      (footprint "eagle-import:1X01")
      (libsource (lib "eagle-import") (part "1X01"))
    )
    (comp (ref "JP632")
      (value "1X01")
      (footprint "eagle-import:1X01")
      (libsource (lib "eagle-import") (part "1X01"))
    )
    (comp (ref "JP633")
      (value "1X01")
      (footprint "eagle-import:1X01")
      (libsource (lib "eagle-import") (part "1X01"))
    )
    (comp (ref "JP634")
      (value "1X01")
      (footprint "eagle-import:1X01")
      (libsource (lib "eagle-import") (part "1X01"))
    )
    (comp (ref "JP635")
      (value "1X01")
      (footprint "eagle-import:1X01")
      (libsource (lib "eagle-import") (part "1X01"))
    )
    (comp (ref "JP636")
      (value "1X01")
      (footprint "eagle-import:1X01")
      (libsource (lib "eagle-import") (part "1X01"))
    )
    (comp (ref "JP637")
      (value "1X01")
      (footprint "eagle-import:1X01")
      (libsource (lib "eagle-import") (part "1X01"))
    )
    (comp (ref "JP638")
      (value "1X01")
      (footprint "eagle-import:1X01")
      (libsource (lib "eagle-import") (part "1X01"))
    )
    (comp (ref "JP639")
      (value "1X01")
      (footprint "eagle-import:1X01")
      (libsource (lib "eagle-import") (part "1X01"))
    )
    (comp (ref "JP640")
      (value "1X01")
      (footprint "eagle-import:1X01")
      (libsource (lib "eagle-import") (part "1X01"))
    )
    (comp (ref "JP641")
      (value "1X01")
      (footprint "eagle-import:1X01")
      (libsource (lib "eagle-import") (part "1X01"))
    )
    (comp (ref "JP642")
      (value "1X01")
      (footprint "eagle-import:1X01")
      (libsource (lib "eagle-import") (part "1X01"))
    )
    (comp (ref "JP643")
      (value "1X01")
      (footprint "eagle-import:1X01")
      (libsource (lib "eagle-import") (part "1X01"))
    )
    (comp (ref "JP644")
      (value "1X01")
      (footprint "eagle-import:1X01")
      (libsource (lib "eagle-import") (part "1X01"))
    )
    (comp (ref "JP645")
      (value "1X01")
      (footprint "eagle-import:1X01")
      (libsource (lib "eagle-import") (part "1X01"))
    )
    (comp (ref "JP646")
      (value "1X01")
      (footprint "eagle-import:1X01")
      (libsource (lib "eagle-import") (part "1X01"))
    )
    (comp (ref "JP647")
      (value "1X01")
      (footprint "eagle-import:1X01")
      (libsource (lib "eagle-import") (part "1X01"))
    )
    (comp (ref "JP648")
      (value "1X01")
      (footprint "eagle-import:1X01")
      (libsource (lib "eagle-import") (part "1X01"))
    )
    (comp (ref "JP649")
      (value "1X01")
      (footprint "eagle-import:1X01")
      (libsource (lib "eagle-import") (part "1X01"))
    )
    (comp (ref "JP650")
      (value "1X01")
      (footprint "eagle-import:1X01")
      (libsource (lib "eagle-import") (part "1X01"))
    )
    (comp (ref "JP651")
      (value "1X01")
      (footprint "eagle-import:1X01")
      (libsource (lib "eagle-import") (part "1X01"))
    )
    (comp (ref "JP652")
      (value "1X01")
      (footprint "eagle-import:1X01")
      (libsource (lib "eagle-import") (part "1X01"))
    )
    (comp (ref "JP653")
      (value "1X01")
      (footprint "eagle-import:1X01")
      (libsource (lib "eagle-import") (part "1X01"))
    )
    (comp (ref "JP654")
      (value "1X01")
      (footprint "eagle-import:1X01")
      (libsource (lib "eagle-import") (part "1X01"))
    )
    (comp (ref "JP655")
      (value "1X01")
      (footprint "eagle-import:1X01")
      (libsource (lib "eagle-import") (part "1X01"))
    )
    (comp (ref "JP656")
      (value "1X01")
      (footprint "eagle-import:1X01")
      (libsource (lib "eagle-import") (part "1X01"))
    )
    (comp (ref "JP657")
      (value "1X01")
      (footprint "eagle-import:1X01")
      (libsource (lib "eagle-import") (part "1X01"))
    )
    (comp (ref "JP658")
      (value "1X01")
      (footprint "eagle-import:1X01")
      (libsource (lib "eagle-import") (part "1X01"))
    )
    (comp (ref "JP659")
      (value "1X01")
      (footprint "eagle-import:1X01")
      (libsource (lib "eagle-import") (part "1X01"))
    )
    (comp (ref "JP660")
      (value "1X01")
      (footprint "eagle-import:1X01")
      (libsource (lib "eagle-import") (part "1X01"))
    )
    (comp (ref "JP661")
      (value "1X01")
      (footprint "eagle-import:1X01")
      (libsource (lib "eagle-import") (part "1X01"))
    )
    (comp (ref "JP662")
      (value "1X01")
      (footprint "eagle-import:1X01")
      (libsource (lib "eagle-import") (part "1X01"))
    )
    (comp (ref "JP663")
      (value "1X01")
      (footprint "eagle-import:1X01")
      (libsource (lib "eagle-import") (part "1X01"))
    )
    (comp (ref "JP664")
      (value "1X01")
      (footprint "eagle-import:1X01")
      (libsource (lib "eagle-import") (part "1X01"))
    )
    (comp (ref "JP665")
      (value "1X01")
      (footprint "eagle-import:1X01")
      (libsource (lib "eagle-import") (part "1X01"))
    )
    (comp (ref "JP666")
      (value "1X01")
      (footprint "eagle-import:1X01")
      (libsource (lib "eagle-import") (part "1X01"))
    )
    (comp (ref "JP667")
      (value "1X01")
      (footprint "eagle-import:1X01")
      (libsource (lib "eagle-import") (part "1X01"))
    )
    (comp (ref "JP668")
      (value "1X01")
      (footprint "eagle-import:1X01")
      (libsource (lib "eagle-import") (part "1X01"))
    )
    (comp (ref "JP669")
      (value "1X01")
      (footprint "eagle-import:1X01")
      (libsource (lib "eagle-import") (part "1X01"))
    )
    (comp (ref "JP670")
      (value "1X01")
      (footprint "eagle-import:1X01")
      (libsource (lib "eagle-import") (part "1X01"))
    )
    (comp (ref "JP671")
      (value "1X01")
      (footprint "eagle-import:1X01")
      (libsource (lib "eagle-import") (part "1X01"))
    )
    (comp (ref "JP672")
      (value "1X01")
      (footprint "eagle-import:1X01")
      (libsource (lib "eagle-import") (part "1X01"))
    )
    (comp (ref "JP673")
      (value "1X01")
      (footprint "eagle-import:1X01")
      (libsource (lib "eagle-import") (part "1X01"))
    )
    (comp (ref "JP674")
      (value "1X01")
      (footprint "eagle-import:1X01")
      (libsource (lib "eagle-import") (part "1X01"))
    )
    (comp (ref "JP675")
      (value "1X01")
      (footprint "eagle-import:1X01")
      (libsource (lib "eagle-import") (part "1X01"))
    )
    (comp (ref "JP676")
      (value "1X01")
      (footprint "eagle-import:1X01")
      (libsource (lib "eagle-import") (part "1X01"))
    )
    (comp (ref "JP677")
      (value "1X01")
      (footprint "eagle-import:1X01")
      (libsource (lib "eagle-import") (part "1X01"))
    )
    (comp (ref "JP678")
      (value "1X01")
      (footprint "eagle-import:1X01")
      (libsource (lib "eagle-import") (part "1X01"))
    )
    (comp (ref "JP679")
      (value "1X01")
      (footprint "eagle-import:1X01")
      (libsource (lib "eagle-import") (part "1X01"))
    )
    (comp (ref "JP680")
      (value "1X01")
      (footprint "eagle-import:1X01")
      (libsource (lib "eagle-import") (part "1X01"))
    )
    (comp (ref "JP681")
      (value "1X01")
      (footprint "eagle-import:1X01")
      (libsource (lib "eagle-import") (part "1X01"))
    )
    (comp (ref "JP682")
      (value "1X01")
      (footprint "eagle-import:1X01")
      (libsource (lib "eagle-import") (part "1X01"))
    )
    (comp (ref "JP683")
      (value "1X01")
      (footprint "eagle-import:1X01")
      (libsource (lib "eagle-import") (part "1X01"))
    )
    (comp (ref "JP684")
      (value "1X01")
      (footprint "eagle-import:1X01")
      (libsource (lib "eagle-import") (part "1X01"))
    )
    (comp (ref "JP685")
      (value "1X01")
      (footprint "eagle-import:1X01")
      (libsource (lib "eagle-import") (part "1X01"))
    )
    (comp (ref "JP686")
      (value "1X01")
      (footprint "eagle-import:1X01")
      (libsource (lib "eagle-import") (part "1X01"))
    )
    (comp (ref "JP687")
      (value "1X01")
      (footprint "eagle-import:1X01")
      (libsource (lib "eagle-import") (part "1X01"))
    )
    (comp (ref "JP688")
      (value "1X01")
      (footprint "eagle-import:1X01")
      (libsource (lib "eagle-import") (part "1X01"))
    )
    (comp (ref "JP689")
      (value "1X01")
      (footprint "eagle-import:1X01")
      (libsource (lib "eagle-import") (part "1X01"))
    )
    (comp (ref "JP690")
      (value "1X01")
      (footprint "eagle-import:1X01")
      (libsource (lib "eagle-import") (part "1X01"))
    )
    (comp (ref "JP691")
      (value "1X01")
      (footprint "eagle-import:1X01")
      (libsource (lib "eagle-import") (part "1X01"))
    )
    (comp (ref "JP692")
      (value "1X01")
      (footprint "eagle-import:1X01")
      (libsource (lib "eagle-import") (part "1X01"))
    )
    (comp (ref "JP693")
      (value "1X01")
      (footprint "eagle-import:1X01")
      (libsource (lib "eagle-import") (part "1X01"))
    )
    (comp (ref "JP694")
      (value "1X01")
      (footprint "eagle-import:1X01")
      (libsource (lib "eagle-import") (part "1X01"))
    )
    (comp (ref "JP695")
      (value "1X01")
      (footprint "eagle-import:1X01")
      (libsource (lib "eagle-import") (part "1X01"))
    )
    (comp (ref "JP696")
      (value "1X01")
      (footprint "eagle-import:1X01")
      (libsource (lib "eagle-import") (part "1X01"))
    )
    (comp (ref "JP697")
      (value "1X01")
      (footprint "eagle-import:1X01")
      (libsource (lib "eagle-import") (part "1X01"))
    )
    (comp (ref "JP698")
      (value "1X01")
      (footprint "eagle-import:1X01")
      (libsource (lib "eagle-import") (part "1X01"))
    )
    (comp (ref "JP699")
      (value "1X01")
      (footprint "eagle-import:1X01")
      (libsource (lib "eagle-import") (part "1X01"))
    )
    (comp (ref "JP700")
      (value "1X01")
      (footprint "eagle-import:1X01")
      (libsource (lib "eagle-import") (part "1X01"))
    )
    (comp (ref "JP701")
      (value "1X01")
      (footprint "eagle-import:1X01")
      (libsource (lib "eagle-import") (part "1X01"))
    )
    (comp (ref "JP702")
      (value "1X01")
      (footprint "eagle-import:1X01")
      (libsource (lib "eagle-import") (part "1X01"))
    )
    (comp (ref "JP703")
      (value "1X01")
      (footprint "eagle-import:1X01")
      (libsource (lib "eagle-import") (part "1X01"))
    )
    (comp (ref "JP704")
      (value "1X01")
      (footprint "eagle-import:1X01")
      (libsource (lib "eagle-import") (part "1X01"))
    )
    (comp (ref "JP705")
      (value "1X01")
      (footprint "eagle-import:1X01")
      (libsource (lib "eagle-import") (part "1X01"))
    )
    (comp (ref "JP706")
      (value "1X01")
      (footprint "eagle-import:1X01")
      (libsource (lib "eagle-import") (part "1X01"))
    )
    (comp (ref "JP707")
      (value "1X01")
      (footprint "eagle-import:1X01")
      (libsource (lib "eagle-import") (part "1X01"))
    )
    (comp (ref "JP708")
      (value "1X01")
      (footprint "eagle-import:1X01")
      (libsource (lib "eagle-import") (part "1X01"))
    )
    (comp (ref "JP709")
      (value "1X01")
      (footprint "eagle-import:1X01")
      (libsource (lib "eagle-import") (part "1X01"))
    )
    (comp (ref "JP710")
      (value "1X01")
      (footprint "eagle-import:1X01")
      (libsource (lib "eagle-import") (part "1X01"))
    )
    (comp (ref "JP711")
      (value "1X01")
      (footprint "eagle-import:1X01")
      (libsource (lib "eagle-import") (part "1X01"))
    )
    (comp (ref "JP712")
      (value "1X01")
      (footprint "eagle-import:1X01")
      (libsource (lib "eagle-import") (part "1X01"))
    )
    (comp (ref "JP713")
      (value "1X01")
      (footprint "eagle-import:1X01")
      (libsource (lib "eagle-import") (part "1X01"))
    )
    (comp (ref "JP714")
      (value "1X01")
      (footprint "eagle-import:1X01")
      (libsource (lib "eagle-import") (part "1X01"))
    )
    (comp (ref "JP715")
      (value "1X01")
      (footprint "eagle-import:1X01")
      (libsource (lib "eagle-import") (part "1X01"))
    )
    (comp (ref "JP716")
      (value "1X01")
      (footprint "eagle-import:1X01")
      (libsource (lib "eagle-import") (part "1X01"))
    )
    (comp (ref "JP717")
      (value "1X01")
      (footprint "eagle-import:1X01")
      (libsource (lib "eagle-import") (part "1X01"))
    )
    (comp (ref "JP718")
      (value "1X01")
      (footprint "eagle-import:1X01")
      (libsource (lib "eagle-import") (part "1X01"))
    )
    (comp (ref "JP719")
      (value "1X01")
      (footprint "eagle-import:1X01")
      (libsource (lib "eagle-import") (part "1X01"))
    )
    (comp (ref "JP720")
      (value "1X01")
      (footprint "eagle-import:1X01")
      (libsource (lib "eagle-import") (part "1X01"))
    )
    (comp (ref "JP721")
      (value "1X01")
      (footprint "eagle-import:1X01")
      (libsource (lib "eagle-import") (part "1X01"))
    )
    (comp (ref "JP722")
      (value "1X01")
      (footprint "eagle-import:1X01")
      (libsource (lib "eagle-import") (part "1X01"))
    )
    (comp (ref "JP723")
      (value "1X01")
      (footprint "eagle-import:1X01")
      (libsource (lib "eagle-import") (part "1X01"))
    )
    (comp (ref "JP724")
      (value "1X01")
      (footprint "eagle-import:1X01")
      (libsource (lib "eagle-import") (part "1X01"))
    )
    (comp (ref "JP725")
      (value "1X01")
      (footprint "eagle-import:1X01")
      (libsource (lib "eagle-import") (part "1X01"))
    )
    (comp (ref "JP726")
      (value "1X01")
      (footprint "eagle-import:1X01")
      (libsource (lib "eagle-import") (part "1X01"))
    )
    (comp (ref "JP727")
      (value "1X01")
      (footprint "eagle-import:1X01")
      (libsource (lib "eagle-import") (part "1X01"))
    )
    (comp (ref "JP728")
      (value "1X01")
      (footprint "eagle-import:1X01")
      (libsource (lib "eagle-import") (part "1X01"))
    )
    (comp (ref "JP729")
      (value "1X01")
      (footprint "eagle-import:1X01")
      (libsource (lib "eagle-import") (part "1X01"))
    )
    (comp (ref "JP730")
      (value "1X01")
      (footprint "eagle-import:1X01")
      (libsource (lib "eagle-import") (part "1X01"))
    )
    (comp (ref "JP731")
      (value "1X01")
      (footprint "eagle-import:1X01")
      (libsource (lib "eagle-import") (part "1X01"))
    )
    (comp (ref "JP732")
      (value "1X01")
      (footprint "eagle-import:1X01")
      (libsource (lib "eagle-import") (part "1X01"))
    )
    (comp (ref "JP733")
      (value "1X01")
      (footprint "eagle-import:1X01")
      (libsource (lib "eagle-import") (part "1X01"))
    )
    (comp (ref "JP734")
      (value "1X01")
      (footprint "eagle-import:1X01")
      (libsource (lib "eagle-import") (part "1X01"))
    )
    (comp (ref "JP735")
      (value "1X01")
      (footprint "eagle-import:1X01")
      (libsource (lib "eagle-import") (part "1X01"))
    )
    (comp (ref "JP736")
      (value "1X01")
      (footprint "eagle-import:1X01")
      (libsource (lib "eagle-import") (part "1X01"))
    )
    (comp (ref "JP737")
      (value "1X01")
      (footprint "eagle-import:1X01")
      (libsource (lib "eagle-import") (part "1X01"))
    )
    (comp (ref "JP738")
      (value "1X01")
      (footprint "eagle-import:1X01")
      (libsource (lib "eagle-import") (part "1X01"))
    )
    (comp (ref "JP739")
      (value "1X01")
      (footprint "eagle-import:1X01")
      (libsource (lib "eagle-import") (part "1X01"))
    )
    (comp (ref "JP740")
      (value "1X01")
      (footprint "eagle-import:1X01")
      (libsource (lib "eagle-import") (part "1X01"))
    )
    (comp (ref "JP741")
      (value "1X01")
      (footprint "eagle-import:1X01")
      (libsource (lib "eagle-import") (part "1X01"))
    )
    (comp (ref "JP742")
      (value "1X01")
      (footprint "eagle-import:1X01")
      (libsource (lib "eagle-import") (part "1X01"))
    )
    (comp (ref "JP743")
      (value "1X01")
      (footprint "eagle-import:1X01")
      (libsource (lib "eagle-import") (part "1X01"))
    )
    (comp (ref "JP744")
      (value "1X01")
      (footprint "eagle-import:1X01")
      (libsource (lib "eagle-import") (part "1X01"))
    )
    (comp (ref "JP745")
      (value "1X01")
      (footprint "eagle-import:1X01")
      (libsource (lib "eagle-import") (part "1X01"))
    )
    (comp (ref "JP746")
      (value "1X01")
      (footprint "eagle-import:1X01")
      (libsource (lib "eagle-import") (part "1X01"))
    )
    (comp (ref "JP747")
      (value "1X01")
      (footprint "eagle-import:1X01")
      (libsource (lib "eagle-import") (part "1X01"))
    )
    (comp (ref "JP748")
      (value "1X01")
      (footprint "eagle-import:1X01")
      (libsource (lib "eagle-import") (part "1X01"))
    )
    (comp (ref "JP749")
      (value "1X01")
      (footprint "eagle-import:1X01")
      (libsource (lib "eagle-import") (part "1X01"))
    )
    (comp (ref "JP750")
      (value "1X01")
      (footprint "eagle-import:1X01")
      (libsource (lib "eagle-import") (part "1X01"))
    )
    (comp (ref "JP751")
      (value "1X01")
      (footprint "eagle-import:1X01")
      (libsource (lib "eagle-import") (part "1X01"))
    )
    (comp (ref "JP752")
      (value "1X01")
      (footprint "eagle-import:1X01")
      (libsource (lib "eagle-import") (part "1X01"))
    )
    (comp (ref "JP753")
      (value "1X01")
      (footprint "eagle-import:1X01")
      (libsource (lib "eagle-import") (part "1X01"))
    )
    (comp (ref "JP754")
      (value "1X01")
      (footprint "eagle-import:1X01")
      (libsource (lib "eagle-import") (part "1X01"))
    )
    (comp (ref "JP755")
      (value "1X01")
      (footprint "eagle-import:1X01")
      (libsource (lib "eagle-import") (part "1X01"))
    )
    (comp (ref "JP756")
      (value "1X01")
      (footprint "eagle-import:1X01")
      (libsource (lib "eagle-import") (part "1X01"))
    )
    (comp (ref "JP757")
      (value "1X01")
      (footprint "eagle-import:1X01")
      (libsource (lib "eagle-import") (part "1X01"))
    )
    (comp (ref "JP758")
      (value "1X01")
      (footprint "eagle-import:1X01")
      (libsource (lib "eagle-import") (part "1X01"))
    )
    (comp (ref "JP759")
      (value "1X01")
      (footprint "eagle-import:1X01")
      (libsource (lib "eagle-import") (part "1X01"))
    )
    (comp (ref "JP760")
      (value "1X01")
      (footprint "eagle-import:1X01")
      (libsource (lib "eagle-import") (part "1X01"))
    )
    (comp (ref "JP761")
      (value "1X01")
      (footprint "eagle-import:1X01")
      (libsource (lib "eagle-import") (part "1X01"))
    )
    (comp (ref "JP762")
      (value "1X01")
      (footprint "eagle-import:1X01")
      (libsource (lib "eagle-import") (part "1X01"))
    )
    (comp (ref "JP763")
      (value "1X01")
      (footprint "eagle-import:1X01")
      (libsource (lib "eagle-import") (part "1X01"))
    )
    (comp (ref "JP764")
      (value "1X01")
      (footprint "eagle-import:1X01")
      (libsource (lib "eagle-import") (part "1X01"))
    )
    (comp (ref "JP765")
      (value "1X01")
      (footprint "eagle-import:1X01")
      (libsource (lib "eagle-import") (part "1X01"))
    )
    (comp (ref "JP766")
      (value "1X01")
      (footprint "eagle-import:1X01")
      (libsource (lib "eagle-import") (part "1X01"))
    )
    (comp (ref "JP767")
      (value "1X01")
      (footprint "eagle-import:1X01")
      (libsource (lib "eagle-import") (part "1X01"))
    )
    (comp (ref "JP768")
      (value "1X01")
      (footprint "eagle-import:1X01")
      (libsource (lib "eagle-import") (part "1X01"))
    )
    (comp (ref "JP769")
      (value "1X01")
      (footprint "eagle-import:1X01")
      (libsource (lib "eagle-import") (part "1X01"))
    )
    (comp (ref "JP770")
      (value "1X01")
      (footprint "eagle-import:1X01")
      (libsource (lib "eagle-import") (part "1X01"))
    )
    (comp (ref "JP771")
      (value "1X01")
      (footprint "eagle-import:1X01")
      (libsource (lib "eagle-import") (part "1X01"))
    )
    (comp (ref "JP772")
      (value "1X01")
      (footprint "eagle-import:1X01")
      (libsource (lib "eagle-import") (part "1X01"))
    )
    (comp (ref "JP773")
      (value "1X01")
      (footprint "eagle-import:1X01")
      (libsource (lib "eagle-import") (part "1X01"))
    )
    (comp (ref "JP774")
      (value "1X01")
      (footprint "eagle-import:1X01")
      (libsource (lib "eagle-import") (part "1X01"))
    )
    (comp (ref "JP775")
      (value "1X01")
      (footprint "eagle-import:1X01")
      (libsource (lib "eagle-import") (part "1X01"))
    )
    (comp (ref "JP776")
      (value "1X01")
      (footprint "eagle-import:1X01")
      (libsource (lib "eagle-import") (part "1X01"))
    )
    (comp (ref "JP777")
      (value "1X01")
      (footprint "eagle-import:1X01")
      (libsource (lib "eagle-import") (part "1X01"))
    )
    (comp (ref "JP778")
      (value "1X01")
      (footprint "eagle-import:1X01")
      (libsource (lib "eagle-import") (part "1X01"))
    )
    (comp (ref "JP779")
      (value "1X01")
      (footprint "eagle-import:1X01")
      (libsource (lib "eagle-import") (part "1X01"))
    )
    (comp (ref "JP780")
      (value "1X01")
      (footprint "eagle-import:1X01")
      (libsource (lib "eagle-import") (part "1X01"))
    )
    (comp (ref "JP781")
      (value "1X01")
      (footprint "eagle-import:1X01")
      (libsource (lib "eagle-import") (part "1X01"))
    )
    (comp (ref "JP782")
      (value "1X01")
      (footprint "eagle-import:1X01")
      (libsource (lib "eagle-import") (part "1X01"))
    )
    (comp (ref "JP783")
      (value "1X01")
      (footprint "eagle-import:1X01")
      (libsource (lib "eagle-import") (part "1X01"))
    )
    (comp (ref "JP784")
      (value "1X01")
      (footprint "eagle-import:1X01")
      (libsource (lib "eagle-import") (part "1X01"))
    )
    (comp (ref "JP785")
      (value "1X01")
      (footprint "eagle-import:1X01")
      (libsource (lib "eagle-import") (part "1X01"))
    )
    (comp (ref "JP786")
      (value "1X01")
      (footprint "eagle-import:1X01")
      (libsource (lib "eagle-import") (part "1X01"))
    )
    (comp (ref "JP787")
      (value "1X01")
      (footprint "eagle-import:1X01")
      (libsource (lib "eagle-import") (part "1X01"))
    )
    (comp (ref "JP788")
      (value "1X01-WIDE")
      (footprint "eagle-import:1X01-WIDE")
      (libsource (lib "eagle-import") (part "1X01-WIDE"))
    )
    (comp (ref "JP789")
      (value "1X01-WIDE")
      (footprint "eagle-import:1X01-WIDE")
      (libsource (lib "eagle-import") (part "1X01-WIDE"))
    )
    (comp (ref "JP790")
      (value "1X01-WIDE")
      (footprint "eagle-import:1X01-WIDE")
      (libsource (lib "eagle-import") (part "1X01-WIDE"))
    )
    (comp (ref "JP791")
      (value "1X01")
      (footprint "eagle-import:1X01")
      (libsource (lib "eagle-import") (part "1X01"))
    )
    (comp (ref "JP792")
      (value "1X01")
      (footprint "eagle-import:1X01")
      (libsource (lib "eagle-import") (part "1X01"))
    )
    (comp (ref "JP793")
      (value "1X01")
      (footprint "eagle-import:1X01")
      (libsource (lib "eagle-import") (part "1X01"))
    )
    (comp (ref "JP794")
      (value "1X01")
      (footprint "eagle-import:1X01")
      (libsource (lib "eagle-import") (part "1X01"))
    )
    (comp (ref "JP795")
      (value "1X01")
      (footprint "eagle-import:1X01")
      (libsource (lib "eagle-import") (part "1X01"))
    )
    (comp (ref "JP796")
      (value "1X01")
      (footprint "eagle-import:1X01")
      (libsource (lib "eagle-import") (part "1X01"))
    )
    (comp (ref "JP797")
      (value "1X01")
      (footprint "eagle-import:1X01")
      (libsource (lib "eagle-import") (part "1X01"))
    )
    (comp (ref "JP798")
      (value "1X01")
      (footprint "eagle-import:1X01")
      (libsource (lib "eagle-import") (part "1X01"))
    )
    (comp (ref "JP799")
      (value "1X01")
      (footprint "eagle-import:1X01")
      (libsource (lib "eagle-import") (part "1X01"))
    )
    (comp (ref "JP800")
      (value "1X01")
      (footprint "eagle-import:1X01")
      (libsource (lib "eagle-import") (part "1X01"))
    )
    (comp (ref "JP801")
      (value "1X01")
      (footprint "eagle-import:1X01")
      (libsource (lib "eagle-import") (part "1X01"))
    )
    (comp (ref "JP802")
      (value "1X01")
      (footprint "eagle-import:1X01")
      (libsource (lib "eagle-import") (part "1X01"))
    )
    (comp (ref "JP803")
      (value "1X01")
      (footprint "eagle-import:1X01")
      (libsource (lib "eagle-import") (part "1X01"))
    )
    (comp (ref "JP804")
      (value "1X01")
      (footprint "eagle-import:1X01")
      (libsource (lib "eagle-import") (part "1X01"))
    )
    (comp (ref "JP805")
      (value "1X01")
      (footprint "eagle-import:1X01")
      (libsource (lib "eagle-import") (part "1X01"))
    )
    (comp (ref "JP806")
      (value "1X01")
      (footprint "eagle-import:1X01")
      (libsource (lib "eagle-import") (part "1X01"))
    )
    (comp (ref "JP807")
      (value "1X01")
      (footprint "eagle-import:1X01")
      (libsource (lib "eagle-import") (part "1X01"))
    )
    (comp (ref "JP808")
      (value "1X01")
      (footprint "eagle-import:1X01")
      (libsource (lib "eagle-import") (part "1X01"))
    )
    (comp (ref "JP809")
      (value "1X01")
      (footprint "eagle-import:1X01")
      (libsource (lib "eagle-import") (part "1X01"))
    )
    (comp (ref "JP810")
      (value "1X01")
      (footprint "eagle-import:1X01")
      (libsource (lib "eagle-import") (part "1X01"))
    )
    (comp (ref "JP811")
      (value "1X01")
      (footprint "eagle-import:1X01")
      (libsource (lib "eagle-import") (part "1X01"))
    )
    (comp (ref "JP812")
      (value "1X01")
      (footprint "eagle-import:1X01")
      (libsource (lib "eagle-import") (part "1X01"))
    )
    (comp (ref "JP813")
      (value "1X01")
      (footprint "eagle-import:1X01")
      (libsource (lib "eagle-import") (part "1X01"))
    )
    (comp (ref "JP814")
      (value "1X01")
      (footprint "eagle-import:1X01")
      (libsource (lib "eagle-import") (part "1X01"))
    )
    (comp (ref "JP815")
      (value "1X01")
      (footprint "eagle-import:1X01")
      (libsource (lib "eagle-import") (part "1X01"))
    )
    (comp (ref "JP816")
      (value "1X01")
      (footprint "eagle-import:1X01")
      (libsource (lib "eagle-import") (part "1X01"))
    )
    (comp (ref "JP817")
      (value "1X01")
      (footprint "eagle-import:1X01")
      (libsource (lib "eagle-import") (part "1X01"))
    )
    (comp (ref "JP818")
      (value "1X01")
      (footprint "eagle-import:1X01")
      (libsource (lib "eagle-import") (part "1X01"))
    )
    (comp (ref "JP819")
      (value "1X01")
      (footprint "eagle-import:1X01")
      (libsource (lib "eagle-import") (part "1X01"))
    )
    (comp (ref "JP820")
      (value "1X01")
      (footprint "eagle-import:1X01")
      (libsource (lib "eagle-import") (part "1X01"))
    )
    (comp (ref "JP821")
      (value "1X01")
      (footprint "eagle-import:1X01")
      (libsource (lib "eagle-import") (part "1X01"))
    )
    (comp (ref "JP822")
      (value "1X01")
      (footprint "eagle-import:1X01")
      (libsource (lib "eagle-import") (part "1X01"))
    )
    (comp (ref "JP823")
      (value "1X01")
      (footprint "eagle-import:1X01")
      (libsource (lib "eagle-import") (part "1X01"))
    )
    (comp (ref "JP824")
      (value "1X01")
      (footprint "eagle-import:1X01")
      (libsource (lib "eagle-import") (part "1X01"))
    )
    (comp (ref "JP825")
      (value "1X01")
      (footprint "eagle-import:1X01")
      (libsource (lib "eagle-import") (part "1X01"))
    )
    (comp (ref "JP826")
      (value "1X01")
      (footprint "eagle-import:1X01")
      (libsource (lib "eagle-import") (part "1X01"))
    )
    (comp (ref "JP827")
      (value "1X01")
      (footprint "eagle-import:1X01")
      (libsource (lib "eagle-import") (part "1X01"))
    )
    (comp (ref "JP828")
      (value "1X01")
      (footprint "eagle-import:1X01")
      (libsource (lib "eagle-import") (part "1X01"))
    )
    (comp (ref "JP829")
      (value "1X01")
      (footprint "eagle-import:1X01")
      (libsource (lib "eagle-import") (part "1X01"))
    )
    (comp (ref "JP830")
      (value "1X01")
      (footprint "eagle-import:1X01")
      (libsource (lib "eagle-import") (part "1X01"))
    )
    (comp (ref "JP831")
      (value "1X01")
      (footprint "eagle-import:1X01")
      (libsource (lib "eagle-import") (part "1X01"))
    )
    (comp (ref "JP832")
      (value "1X01")
      (footprint "eagle-import:1X01")
      (libsource (lib "eagle-import") (part "1X01"))
    )
    (comp (ref "JP833")
      (value "1X01")
      (footprint "eagle-import:1X01")
      (libsource (lib "eagle-import") (part "1X01"))
    )
    (comp (ref "JP834")
      (value "1X01")
      (footprint "eagle-import:1X01")
      (libsource (lib "eagle-import") (part "1X01"))
    )
    (comp (ref "JP835")
      (value "1X01")
      (footprint "eagle-import:1X01")
      (libsource (lib "eagle-import") (part "1X01"))
    )
    (comp (ref "JP836")
      (value "1X01")
      (footprint "eagle-import:1X01")
      (libsource (lib "eagle-import") (part "1X01"))
    )
    (comp (ref "JP837")
      (value "1X01")
      (footprint "eagle-import:1X01")
      (libsource (lib "eagle-import") (part "1X01"))
    )
    (comp (ref "JP838")
      (value "1X01")
      (footprint "eagle-import:1X01")
      (libsource (lib "eagle-import") (part "1X01"))
    )
    (comp (ref "JP839")
      (value "1X01")
      (footprint "eagle-import:1X01")
      (libsource (lib "eagle-import") (part "1X01"))
    )
    (comp (ref "JP840")
      (value "1X01")
      (footprint "eagle-import:1X01")
      (libsource (lib "eagle-import") (part "1X01"))
    )
    (comp (ref "JP841")
      (value "1X01")
      (footprint "eagle-import:1X01")
      (libsource (lib "eagle-import") (part "1X01"))
    )
    (comp (ref "JP842")
      (value "1X01")
      (footprint "eagle-import:1X01")
      (libsource (lib "eagle-import") (part "1X01"))
    )
    (comp (ref "JP843")
      (value "1X01")
      (footprint "eagle-import:1X01")
      (libsource (lib "eagle-import") (part "1X01"))
    )
    (comp (ref "JP844")
      (value "1X01")
      (footprint "eagle-import:1X01")
      (libsource (lib "eagle-import") (part "1X01"))
    )
    (comp (ref "JP845")
      (value "1X01")
      (footprint "eagle-import:1X01")
      (libsource (lib "eagle-import") (part "1X01"))
    )
    (comp (ref "JP846")
      (value "1X01")
      (footprint "eagle-import:1X01")
      (libsource (lib "eagle-import") (part "1X01"))
    )
    (comp (ref "JP847")
      (value "1X01")
      (footprint "eagle-import:1X01")
      (libsource (lib "eagle-import") (part "1X01"))
    )
    (comp (ref "JP848")
      (value "1X01")
      (footprint "eagle-import:1X01")
      (libsource (lib "eagle-import") (part "1X01"))
    )
    (comp (ref "JP849")
      (value "1X01")
      (footprint "eagle-import:1X01")
      (libsource (lib "eagle-import") (part "1X01"))
    )
    (comp (ref "JP850")
      (value "1X01")
      (footprint "eagle-import:1X01")
      (libsource (lib "eagle-import") (part "1X01"))
    )
    (comp (ref "JP851")
      (value "1X01")
      (footprint "eagle-import:1X01")
      (libsource (lib "eagle-import") (part "1X01"))
    )
    (comp (ref "JP852")
      (value "1X01")
      (footprint "eagle-import:1X01")
      (libsource (lib "eagle-import") (part "1X01"))
    )
    (comp (ref "JP853")
      (value "1X01")
      (footprint "eagle-import:1X01")
      (libsource (lib "eagle-import") (part "1X01"))
    )
    (comp (ref "JP854")
      (value "1X01")
      (footprint "eagle-import:1X01")
      (libsource (lib "eagle-import") (part "1X01"))
    )
    (comp (ref "JP855")
      (value "1X01")
      (footprint "eagle-import:1X01")
      (libsource (lib "eagle-import") (part "1X01"))
    )
    (comp (ref "JP856")
      (value "1X01")
      (footprint "eagle-import:1X01")
      (libsource (lib "eagle-import") (part "1X01"))
    )
    (comp (ref "JP857")
      (value "1X01")
      (footprint "eagle-import:1X01")
      (libsource (lib "eagle-import") (part "1X01"))
    )
    (comp (ref "JP858")
      (value "1X01")
      (footprint "eagle-import:1X01")
      (libsource (lib "eagle-import") (part "1X01"))
    )
    (comp (ref "JP859")
      (value "1X01")
      (footprint "eagle-import:1X01")
      (libsource (lib "eagle-import") (part "1X01"))
    )
    (comp (ref "JP860")
      (value "1X01")
      (footprint "eagle-import:1X01")
      (libsource (lib "eagle-import") (part "1X01"))
    )
    (comp (ref "JP861")
      (value "1X01")
      (footprint "eagle-import:1X01")
      (libsource (lib "eagle-import") (part "1X01"))
    )
    (comp (ref "JP862")
      (value "1X01")
      (footprint "eagle-import:1X01")
      (libsource (lib "eagle-import") (part "1X01"))
    )
    (comp (ref "JP863")
      (value "1X01")
      (footprint "eagle-import:1X01")
      (libsource (lib "eagle-import") (part "1X01"))
    )
    (comp (ref "JP864")
      (value "1X01")
      (footprint "eagle-import:1X01")
      (libsource (lib "eagle-import") (part "1X01"))
    )
    (comp (ref "JP865")
      (value "1X01")
      (footprint "eagle-import:1X01")
      (libsource (lib "eagle-import") (part "1X01"))
    )
    (comp (ref "JP866")
      (value "1X01")
      (footprint "eagle-import:1X01")
      (libsource (lib "eagle-import") (part "1X01"))
    )
    (comp (ref "JP867")
      (value "1X01")
      (footprint "eagle-import:1X01")
      (libsource (lib "eagle-import") (part "1X01"))
    )
    (comp (ref "JP868")
      (value "1X01")
      (footprint "eagle-import:1X01")
      (libsource (lib "eagle-import") (part "1X01"))
    )
    (comp (ref "JP869")
      (value "1X01")
      (footprint "eagle-import:1X01")
      (libsource (lib "eagle-import") (part "1X01"))
    )
    (comp (ref "JP870")
      (value "1X01")
      (footprint "eagle-import:1X01")
      (libsource (lib "eagle-import") (part "1X01"))
    )
    (comp (ref "JP871")
      (value "1X01")
      (footprint "eagle-import:1X01")
      (libsource (lib "eagle-import") (part "1X01"))
    )
    (comp (ref "JP872")
      (value "1X01")
      (footprint "eagle-import:1X01")
      (libsource (lib "eagle-import") (part "1X01"))
    )
    (comp (ref "JP873")
      (value "1X01")
      (footprint "eagle-import:1X01")
      (libsource (lib "eagle-import") (part "1X01"))
    )
    (comp (ref "JP874")
      (value "1X01")
      (footprint "eagle-import:1X01")
      (libsource (lib "eagle-import") (part "1X01"))
    )
    (comp (ref "JP875")
      (value "1X01")
      (footprint "eagle-import:1X01")
      (libsource (lib "eagle-import") (part "1X01"))
    )
    (comp (ref "JP876")
      (value "1X01")
      (footprint "eagle-import:1X01")
      (libsource (lib "eagle-import") (part "1X01"))
    )
    (comp (ref "JP877")
      (value "1X01")
      (footprint "eagle-import:1X01")
      (libsource (lib "eagle-import") (part "1X01"))
    )
    (comp (ref "JP878")
      (value "1X01")
      (footprint "eagle-import:1X01")
      (libsource (lib "eagle-import") (part "1X01"))
    )
    (comp (ref "JP879")
      (value "1X01")
      (footprint "eagle-import:1X01")
      (libsource (lib "eagle-import") (part "1X01"))
    )
    (comp (ref "JP880")
      (value "1X01")
      (footprint "eagle-import:1X01")
      (libsource (lib "eagle-import") (part "1X01"))
    )
    (comp (ref "JP881")
      (value "1X01")
      (footprint "eagle-import:1X01")
      (libsource (lib "eagle-import") (part "1X01"))
    )
    (comp (ref "JP882")
      (value "1X01")
      (footprint "eagle-import:1X01")
      (libsource (lib "eagle-import") (part "1X01"))
    )
    (comp (ref "JP883")
      (value "1X01")
      (footprint "eagle-import:1X01")
      (libsource (lib "eagle-import") (part "1X01"))
    )
    (comp (ref "JP884")
      (value "1X01")
      (footprint "eagle-import:1X01")
      (libsource (lib "eagle-import") (part "1X01"))
    )
    (comp (ref "JP885")
      (value "1X01")
      (footprint "eagle-import:1X01")
      (libsource (lib "eagle-import") (part "1X01"))
    )
    (comp (ref "JP886")
      (value "1X01")
      (footprint "eagle-import:1X01")
      (libsource (lib "eagle-import") (part "1X01"))
    )
    (comp (ref "JP887")
      (value "1X01")
      (footprint "eagle-import:1X01")
      (libsource (lib "eagle-import") (part "1X01"))
    )
    (comp (ref "JP888")
      (value "1X01")
      (footprint "eagle-import:1X01")
      (libsource (lib "eagle-import") (part "1X01"))
    )
    (comp (ref "JP889")
      (value "1X01")
      (footprint "eagle-import:1X01")
      (libsource (lib "eagle-import") (part "1X01"))
    )
    (comp (ref "JP890")
      (value "1X01")
      (footprint "eagle-import:1X01")
      (libsource (lib "eagle-import") (part "1X01"))
    )
    (comp (ref "JP891")
      (value "1X01")
      (footprint "eagle-import:1X01")
      (libsource (lib "eagle-import") (part "1X01"))
    )
    (comp (ref "JP892")
      (value "1X01")
      (footprint "eagle-import:1X01")
      (libsource (lib "eagle-import") (part "1X01"))
    )
    (comp (ref "JP893")
      (value "1X01")
      (footprint "eagle-import:1X01")
      (libsource (lib "eagle-import") (part "1X01"))
    )
    (comp (ref "JP894")
      (value "1X01")
      (footprint "eagle-import:1X01")
      (libsource (lib "eagle-import") (part "1X01"))
    )
    (comp (ref "JP895")
      (value "1X01")
      (footprint "eagle-import:1X01")
      (libsource (lib "eagle-import") (part "1X01"))
    )
    (comp (ref "JP896")
      (value "1X01")
      (footprint "eagle-import:1X01")
      (libsource (lib "eagle-import") (part "1X01"))
    )
    (comp (ref "JP897")
      (value "1X01")
      (footprint "eagle-import:1X01")
      (libsource (lib "eagle-import") (part "1X01"))
    )
    (comp (ref "JP898")
      (value "1X01")
      (footprint "eagle-import:1X01")
      (libsource (lib "eagle-import") (part "1X01"))
    )
    (comp (ref "JP899")
      (value "1X01")
      (footprint "eagle-import:1X01")
      (libsource (lib "eagle-import") (part "1X01"))
    )
    (comp (ref "JP900")
      (value "1X01")
      (footprint "eagle-import:1X01")
      (libsource (lib "eagle-import") (part "1X01"))
    )
    (comp (ref "JP901")
      (value "1X01")
      (footprint "eagle-import:1X01")
      (libsource (lib "eagle-import") (part "1X01"))
    )
    (comp (ref "JP902")
      (value "1X01")
      (footprint "eagle-import:1X01")
      (libsource (lib "eagle-import") (part "1X01"))
    )
    (comp (ref "JP903")
      (value "1X01")
      (footprint "eagle-import:1X01")
      (libsource (lib "eagle-import") (part "1X01"))
    )
    (comp (ref "JP904")
      (value "1X01")
      (footprint "eagle-import:1X01")
      (libsource (lib "eagle-import") (part "1X01"))
    )
    (comp (ref "JP905")
      (value "1X01")
      (footprint "eagle-import:1X01")
      (libsource (lib "eagle-import") (part "1X01"))
    )
    (comp (ref "JP906")
      (value "1X01")
      (footprint "eagle-import:1X01")
      (libsource (lib "eagle-import") (part "1X01"))
    )
    (comp (ref "JP907")
      (value "1X01")
      (footprint "eagle-import:1X01")
      (libsource (lib "eagle-import") (part "1X01"))
    )
    (comp (ref "JP908")
      (value "1X01")
      (footprint "eagle-import:1X01")
      (libsource (lib "eagle-import") (part "1X01"))
    )
    (comp (ref "JP909")
      (value "1X01")
      (footprint "eagle-import:1X01")
      (libsource (lib "eagle-import") (part "1X01"))
    )
    (comp (ref "JP910")
      (value "1X01")
      (footprint "eagle-import:1X01")
      (libsource (lib "eagle-import") (part "1X01"))
    )
    (comp (ref "JP911")
      (value "1X01")
      (footprint "eagle-import:1X01")
      (libsource (lib "eagle-import") (part "1X01"))
    )
    (comp (ref "JP912")
      (value "1X01")
      (footprint "eagle-import:1X01")
      (libsource (lib "eagle-import") (part "1X01"))
    )
    (comp (ref "JP913")
      (value "1X01")
      (footprint "eagle-import:1X01")
      (libsource (lib "eagle-import") (part "1X01"))
    )
    (comp (ref "JP914")
      (value "1X01")
      (footprint "eagle-import:1X01")
      (libsource (lib "eagle-import") (part "1X01"))
    )
    (comp (ref "JP915")
      (value "1X01")
      (footprint "eagle-import:1X01")
      (libsource (lib "eagle-import") (part "1X01"))
    )
    (comp (ref "JP916")
      (value "1X01")
      (footprint "eagle-import:1X01")
      (libsource (lib "eagle-import") (part "1X01"))
    )
    (comp (ref "JP917")
      (value "1X01")
      (footprint "eagle-import:1X01")
      (libsource (lib "eagle-import") (part "1X01"))
    )
    (comp (ref "JP918")
      (value "1X01")
      (footprint "eagle-import:1X01")
      (libsource (lib "eagle-import") (part "1X01"))
    )
    (comp (ref "JP919")
      (value "1X01")
      (footprint "eagle-import:1X01")
      (libsource (lib "eagle-import") (part "1X01"))
    )
    (comp (ref "JP920")
      (value "1X01")
      (footprint "eagle-import:1X01")
      (libsource (lib "eagle-import") (part "1X01"))
    )
    (comp (ref "JP921")
      (value "1X01")
      (footprint "eagle-import:1X01")
      (libsource (lib "eagle-import") (part "1X01"))
    )
    (comp (ref "JP922")
      (value "1X01")
      (footprint "eagle-import:1X01")
      (libsource (lib "eagle-import") (part "1X01"))
    )
    (comp (ref "JP923")
      (value "1X01")
      (footprint "eagle-import:1X01")
      (libsource (lib "eagle-import") (part "1X01"))
    )
    (comp (ref "JP924")
      (value "1X01")
      (footprint "eagle-import:1X01")
      (libsource (lib "eagle-import") (part "1X01"))
    )
    (comp (ref "JP925")
      (value "1X01")
      (footprint "eagle-import:1X01")
      (libsource (lib "eagle-import") (part "1X01"))
    )
    (comp (ref "JP926")
      (value "1X01")
      (footprint "eagle-import:1X01")
      (libsource (lib "eagle-import") (part "1X01"))
    )
    (comp (ref "JP927")
      (value "1X01")
      (footprint "eagle-import:1X01")
      (libsource (lib "eagle-import") (part "1X01"))
    )
    (comp (ref "JP928")
      (value "1X01")
      (footprint "eagle-import:1X01")
      (libsource (lib "eagle-import") (part "1X01"))
    )
    (comp (ref "JP929")
      (value "1X01")
      (footprint "eagle-import:1X01")
      (libsource (lib "eagle-import") (part "1X01"))
    )
    (comp (ref "JP930")
      (value "1X01")
      (footprint "eagle-import:1X01")
      (libsource (lib "eagle-import") (part "1X01"))
    )
    (comp (ref "JP931")
      (value "1X01")
      (footprint "eagle-import:1X01")
      (libsource (lib "eagle-import") (part "1X01"))
    )
    (comp (ref "JP932")
      (value "1X01")
      (footprint "eagle-import:1X01")
      (libsource (lib "eagle-import") (part "1X01"))
    )
    (comp (ref "JP933")
      (value "1X01")
      (footprint "eagle-import:1X01")
      (libsource (lib "eagle-import") (part "1X01"))
    )
    (comp (ref "JP934")
      (value "1X01")
      (footprint "eagle-import:1X01")
      (libsource (lib "eagle-import") (part "1X01"))
    )
    (comp (ref "JP935")
      (value "1X01")
      (footprint "eagle-import:1X01")
      (libsource (lib "eagle-import") (part "1X01"))
    )
    (comp (ref "JP936")
      (value "1X01")
      (footprint "eagle-import:1X01")
      (libsource (lib "eagle-import") (part "1X01"))
    )
    (comp (ref "JP937")
      (value "1X01")
      (footprint "eagle-import:1X01")
      (libsource (lib "eagle-import") (part "1X01"))
    )
    (comp (ref "JP938")
      (value "1X01")
      (footprint "eagle-import:1X01")
      (libsource (lib "eagle-import") (part "1X01"))
    )
    (comp (ref "JP939")
      (value "1X01")
      (footprint "eagle-import:1X01")
      (libsource (lib "eagle-import") (part "1X01"))
    )
    (comp (ref "JP940")
      (value "1X01")
      (footprint "eagle-import:1X01")
      (libsource (lib "eagle-import") (part "1X01"))
    )
    (comp (ref "JP941")
      (value "1X01")
      (footprint "eagle-import:1X01")
      (libsource (lib "eagle-import") (part "1X01"))
    )
    (comp (ref "JP942")
      (value "1X01")
      (footprint "eagle-import:1X01")
      (libsource (lib "eagle-import") (part "1X01"))
    )
    (comp (ref "JP943")
      (value "1X01")
      (footprint "eagle-import:1X01")
      (libsource (lib "eagle-import") (part "1X01"))
    )
    (comp (ref "JP944")
      (value "1X01")
      (footprint "eagle-import:1X01")
      (libsource (lib "eagle-import") (part "1X01"))
    )
    (comp (ref "JP945")
      (value "1X01")
      (footprint "eagle-import:1X01")
      (libsource (lib "eagle-import") (part "1X01"))
    )
    (comp (ref "JP946")
      (value "1X01")
      (footprint "eagle-import:1X01")
      (libsource (lib "eagle-import") (part "1X01"))
    )
    (comp (ref "JP947")
      (value "1X01")
      (footprint "eagle-import:1X01")
      (libsource (lib "eagle-import") (part "1X01"))
    )
    (comp (ref "JP948")
      (value "1X01")
      (footprint "eagle-import:1X01")
      (libsource (lib "eagle-import") (part "1X01"))
    )
    (comp (ref "JP949")
      (value "1X01")
      (footprint "eagle-import:1X01")
      (libsource (lib "eagle-import") (part "1X01"))
    )
    (comp (ref "JP950")
      (value "1X01")
      (footprint "eagle-import:1X01")
      (libsource (lib "eagle-import") (part "1X01"))
    )
    (comp (ref "JP951")
      (value "1X01")
      (footprint "eagle-import:1X01")
      (libsource (lib "eagle-import") (part "1X01"))
    )
    (comp (ref "JP952")
      (value "1X01")
      (footprint "eagle-import:1X01")
      (libsource (lib "eagle-import") (part "1X01"))
    )
    (comp (ref "JP953")
      (value "1X01")
      (footprint "eagle-import:1X01")
      (libsource (lib "eagle-import") (part "1X01"))
    )
    (comp (ref "JP954")
      (value "1X01")
      (footprint "eagle-import:1X01")
      (libsource (lib "eagle-import") (part "1X01"))
    )
    (comp (ref "JP955")
      (value "1X01")
      (footprint "eagle-import:1X01")
      (libsource (lib "eagle-import") (part "1X01"))
    )
    (comp (ref "JP956")
      (value "1X01")
      (footprint "eagle-import:1X01")
      (libsource (lib "eagle-import") (part "1X01"))
    )
    (comp (ref "JP957")
      (value "1X01")
      (footprint "eagle-import:1X01")
      (libsource (lib "eagle-import") (part "1X01"))
    )
    (comp (ref "JP958")
      (value "1X01")
      (footprint "eagle-import:1X01")
      (libsource (lib "eagle-import") (part "1X01"))
    )
    (comp (ref "JP959")
      (value "1X01")
      (footprint "eagle-import:1X01")
      (libsource (lib "eagle-import") (part "1X01"))
    )
    (comp (ref "JP960")
      (value "1X01")
      (footprint "eagle-import:1X01")
      (libsource (lib "eagle-import") (part "1X01"))
    )
    (comp (ref "JP961")
      (value "1X01")
      (footprint "eagle-import:1X01")
      (libsource (lib "eagle-import") (part "1X01"))
    )
    (comp (ref "JP962")
      (value "1X01")
      (footprint "eagle-import:1X01")
      (libsource (lib "eagle-import") (part "1X01"))
    )
    (comp (ref "POWER")
      (value "CONN_05X2SHD")
      (footprint "eagle-import:2X5-SHROUDED")
      (libsource (lib "eagle-import") (part "CONN_05X2SHD"))
    )
    (comp (ref "R1")
      (value "3RP/1610N")
      (footprint "eagle-import:3RP_1610N")
      (libsource (lib "eagle-import") (part "3RP/1610N"))
    )
    (comp (ref "R2")
      (value "3RP/1610N")
      (footprint "eagle-import:3RP_1610N")
      (libsource (lib "eagle-import") (part "3RP/1610N"))
    )
    (comp (ref "R3")
      (value "3RP/1610N")
      (footprint "eagle-import:3RP_1610N")
      (libsource (lib "eagle-import") (part "3RP/1610N"))
    )
    (comp (ref "R4")
      (value "3RP/1610N")
      (footprint "eagle-import:3RP_1610N")
      (libsource (lib "eagle-import") (part "3RP/1610N"))
    )
    (comp (ref "U$1")
      (value "RIGHTANGLE")
      (footprint "eagle-import:RIGHTANGLE")
      (libsource (lib "eagle-import") (part "RIGHTANGLE"))
    )
    (comp (ref "U$2")
      (value "RIGHTANGLE")
      (footprint "eagle-import:RIGHTANGLE")
      (libsource (lib "eagle-import") (part "RIGHTANGLE"))
    )
  )
  (nets
    (net (code "1") (name "+5V") (class "Default")
      (node (ref "ARD2") (pin "12") (pinfunction "12_12") (pintype "passive"))
      (node (ref "C6") (pin "1") (pinfunction "1_1") (pintype "passive"))
      (node (ref "IC1") (pin "3") (pinfunction "VIN_3") (pintype "input"))
      (node (ref "IC3") (pin "3") (pinfunction "VO_3") (pintype "passive"))
      (node (ref "JP742") (pin "1") (pinfunction "1_1") (pintype "passive"))
      (node (ref "JP743") (pin "1") (pinfunction "1_1") (pintype "passive"))
      (node (ref "JP744") (pin "1") (pinfunction "1_1") (pintype "passive"))
      (node (ref "JP745") (pin "1") (pinfunction "1_1") (pintype "passive"))
      (node (ref "JP746") (pin "1") (pinfunction "1_1") (pintype "passive"))
      (node (ref "JP747") (pin "1") (pinfunction "1_1") (pintype "passive"))
      (node (ref "JP748") (pin "1") (pinfunction "1_1") (pintype "passive"))
      (node (ref "JP749") (pin "1") (pinfunction "1_1") (pintype "passive"))
      (node (ref "JP750") (pin "1") (pinfunction "1_1") (pintype "passive"))
      (node (ref "JP751") (pin "1") (pinfunction "1_1") (pintype "passive"))
      (node (ref "JP752") (pin "1") (pinfunction "1_1") (pintype "passive"))
      (node (ref "JP753") (pin "1") (pinfunction "1_1") (pintype "passive"))
      (node (ref "JP754") (pin "1") (pinfunction "1_1") (pintype "passive"))
      (node (ref "JP755") (pin "1") (pinfunction "1_1") (pintype "passive"))
      (node (ref "JP756") (pin "1") (pinfunction "1_1") (pintype "passive"))
      (node (ref "JP757") (pin "1") (pinfunction "1_1") (pintype "passive"))
      (node (ref "JP758") (pin "1") (pinfunction "1_1") (pintype "passive"))
      (node (ref "JP759") (pin "1") (pinfunction "1_1") (pintype "passive"))
      (node (ref "JP760") (pin "1") (pinfunction "1_1") (pintype "passive"))
      (node (ref "JP761") (pin "1") (pinfunction "1_1") (pintype "passive"))
      (node (ref "JP762") (pin "1") (pinfunction "1_1") (pintype "passive"))
      (node (ref "JP763") (pin "1") (pinfunction "1_1") (pintype "passive"))
      (node (ref "JP764") (pin "1") (pinfunction "1_1") (pintype "passive"))
      (node (ref "JP765") (pin "1") (pinfunction "1_1") (pintype "passive"))
      (node (ref "JP766") (pin "1") (pinfunction "1_1") (pintype "passive"))
      (node (ref "JP767") (pin "1") (pinfunction "1_1") (pintype "passive"))
      (node (ref "JP768") (pin "1") (pinfunction "1_1") (pintype "passive"))
      (node (ref "JP769") (pin "1") (pinfunction "1_1") (pintype "passive"))
      (node (ref "JP770") (pin "1") (pinfunction "1_1") (pintype "passive"))
      (node (ref "JP771") (pin "1") (pinfunction "1_1") (pintype "passive"))
      (node (ref "JP772") (pin "1") (pinfunction "1_1") (pintype "passive"))
      (node (ref "JP773") (pin "1") (pinfunction "1_1") (pintype "passive"))
      (node (ref "JP774") (pin "1") (pinfunction "1_1") (pintype "passive"))
      (node (ref "JP775") (pin "1") (pinfunction "1_1") (pintype "passive"))
      (node (ref "JP776") (pin "1") (pinfunction "1_1") (pintype "passive"))
      (node (ref "JP777") (pin "1") (pinfunction "1_1") (pintype "passive"))
      (node (ref "JP778") (pin "1") (pinfunction "1_1") (pintype "passive"))
      (node (ref "JP780") (pin "1") (pinfunction "1_1") (pintype "passive"))
    )
    (net (code "2") (name "+12V") (class "Default")
      (node (ref "C7") (pin "1") (pinfunction "1_1") (pintype "passive"))
      (node (ref "C8") (pin "+") (pinfunction "+_+") (pintype "passive"))
      (node (ref "IC3") (pin "1") (pinfunction "VI_1") (pintype "input"))
      (node (ref "JP114") (pin "1") (pinfunction "1_1") (pintype "passive"))
      (node (ref "JP115") (pin "1") (pinfunction "1_1") (pintype "passive"))
      (node (ref "JP117") (pin "1") (pinfunction "1_1") (pintype "passive"))
      (node (ref "JP118") (pin "1") (pinfunction "1_1") (pintype "passive"))
      (node (ref "JP119") (pin "1") (pinfunction "1_1") (pintype "passive"))
      (node (ref "JP120") (pin "1") (pinfunction "1_1") (pintype "passive"))
      (node (ref "JP121") (pin "1") (pinfunction "1_1") (pintype "passive"))
      (node (ref "JP122") (pin "1") (pinfunction "1_1") (pintype "passive"))
      (node (ref "JP123") (pin "1") (pinfunction "1_1") (pintype "passive"))
      (node (ref "JP124") (pin "1") (pinfunction "1_1") (pintype "passive"))
      (node (ref "JP125") (pin "1") (pinfunction "1_1") (pintype "passive"))
      (node (ref "JP126") (pin "1") (pinfunction "1_1") (pintype "passive"))
      (node (ref "JP127") (pin "1") (pinfunction "1_1") (pintype "passive"))
      (node (ref "JP128") (pin "1") (pinfunction "1_1") (pintype "passive"))
      (node (ref "JP129") (pin "1") (pinfunction "1_1") (pintype "passive"))
      (node (ref "JP130") (pin "1") (pinfunction "1_1") (pintype "passive"))
      (node (ref "JP131") (pin "1") (pinfunction "1_1") (pintype "passive"))
      (node (ref "JP132") (pin "1") (pinfunction "1_1") (pintype "passive"))
      (node (ref "JP133") (pin "1") (pinfunction "1_1") (pintype "passive"))
      (node (ref "JP134") (pin "1") (pinfunction "1_1") (pintype "passive"))
      (node (ref "JP135") (pin "1") (pinfunction "1_1") (pintype "passive"))
      (node (ref "JP136") (pin "1") (pinfunction "1_1") (pintype "passive"))
      (node (ref "JP137") (pin "1") (pinfunction "1_1") (pintype "passive"))
      (node (ref "JP138") (pin "1") (pinfunction "1_1") (pintype "passive"))
      (node (ref "JP139") (pin "1") (pinfunction "1_1") (pintype "passive"))
      (node (ref "JP140") (pin "1") (pinfunction "1_1") (pintype "passive"))
      (node (ref "JP141") (pin "1") (pinfunction "1_1") (pintype "passive"))
      (node (ref "JP142") (pin "1") (pinfunction "1_1") (pintype "passive"))
      (node (ref "JP143") (pin "1") (pinfunction "1_1") (pintype "passive"))
      (node (ref "JP144") (pin "1") (pinfunction "1_1") (pintype "passive"))
      (node (ref "JP145") (pin "1") (pinfunction "1_1") (pintype "passive"))
      (node (ref "JP146") (pin "1") (pinfunction "1_1") (pintype "passive"))
      (node (ref "JP147") (pin "1") (pinfunction "1_1") (pintype "passive"))
      (node (ref "JP148") (pin "1") (pinfunction "1_1") (pintype "passive"))
      (node (ref "JP149") (pin "1") (pinfunction "1_1") (pintype "passive"))
      (node (ref "JP150") (pin "1") (pinfunction "1_1") (pintype "passive"))
      (node (ref "JP151") (pin "1") (pinfunction "1_1") (pintype "passive"))
      (node (ref "JP152") (pin "1") (pinfunction "1_1") (pintype "passive"))
      (node (ref "POWER") (pin "10") (pinfunction "10_10") (pintype "passive"))
      (node (ref "POWER") (pin "9") (pinfunction "9_9") (pintype "passive"))
    )
    (net (code "3") (name "-12V") (class "Default")
      (node (ref "C7") (pin "2") (pinfunction "2_2") (pintype "passive"))
      (node (ref "C9") (pin "-") (pinfunction "-_-") (pintype "passive"))
      (node (ref "JP267") (pin "1") (pinfunction "1_1") (pintype "passive"))
      (node (ref "JP268") (pin "1") (pinfunction "1_1") (pintype "passive"))
      (node (ref "JP269") (pin "1") (pinfunction "1_1") (pintype "passive"))
      (node (ref "JP270") (pin "1") (pinfunction "1_1") (pintype "passive"))
      (node (ref "JP271") (pin "1") (pinfunction "1_1") (pintype "passive"))
      (node (ref "JP272") (pin "1") (pinfunction "1_1") (pintype "passive"))
      (node (ref "JP273") (pin "1") (pinfunction "1_1") (pintype "passive"))
      (node (ref "JP274") (pin "1") (pinfunction "1_1") (pintype "passive"))
      (node (ref "JP275") (pin "1") (pinfunction "1_1") (pintype "passive"))
      (node (ref "JP276") (pin "1") (pinfunction "1_1") (pintype "passive"))
      (node (ref "JP277") (pin "1") (pinfunction "1_1") (pintype "passive"))
      (node (ref "JP278") (pin "1") (pinfunction "1_1") (pintype "passive"))
      (node (ref "JP279") (pin "1") (pinfunction "1_1") (pintype "passive"))
      (node (ref "JP280") (pin "1") (pinfunction "1_1") (pintype "passive"))
      (node (ref "JP281") (pin "1") (pinfunction "1_1") (pintype "passive"))
      (node (ref "JP282") (pin "1") (pinfunction "1_1") (pintype "passive"))
      (node (ref "JP283") (pin "1") (pinfunction "1_1") (pintype "passive"))
      (node (ref "JP284") (pin "1") (pinfunction "1_1") (pintype "passive"))
      (node (ref "JP285") (pin "1") (pinfunction "1_1") (pintype "passive"))
      (node (ref "JP286") (pin "1") (pinfunction "1_1") (pintype "passive"))
      (node (ref "JP287") (pin "1") (pinfunction "1_1") (pintype "passive"))
      (node (ref "JP288") (pin "1") (pinfunction "1_1") (pintype "passive"))
      (node (ref "JP289") (pin "1") (pinfunction "1_1") (pintype "passive"))
      (node (ref "JP290") (pin "1") (pinfunction "1_1") (pintype "passive"))
      (node (ref "JP291") (pin "1") (pinfunction "1_1") (pintype "passive"))
      (node (ref "JP292") (pin "1") (pinfunction "1_1") (pintype "passive"))
      (node (ref "JP293") (pin "1") (pinfunction "1_1") (pintype "passive"))
      (node (ref "JP294") (pin "1") (pinfunction "1_1") (pintype "passive"))
      (node (ref "JP295") (pin "1") (pinfunction "1_1") (pintype "passive"))
      (node (ref "JP296") (pin "1") (pinfunction "1_1") (pintype "passive"))
      (node (ref "JP297") (pin "1") (pinfunction "1_1") (pintype "passive"))
      (node (ref "JP298") (pin "1") (pinfunction "1_1") (pintype "passive"))
      (node (ref "JP299") (pin "1") (pinfunction "1_1") (pintype "passive"))
      (node (ref "JP300") (pin "1") (pinfunction "1_1") (pintype "passive"))
      (node (ref "JP301") (pin "1") (pinfunction "1_1") (pintype "passive"))
      (node (ref "JP302") (pin "1") (pinfunction "1_1") (pintype "passive"))
      (node (ref "JP303") (pin "1") (pinfunction "1_1") (pintype "passive"))
      (node (ref "JP304") (pin "1") (pinfunction "1_1") (pintype "passive"))
      (node (ref "POWER") (pin "1") (pinfunction "1_1") (pintype "passive"))
      (node (ref "POWER") (pin "2") (pinfunction "2_2") (pintype "passive"))
    )
    (net (code "4") (name "/MOSI") (class "Default")
      (node (ref "ARD1") (pin "2") (pinfunction "2_2") (pintype "passive"))
      (node (ref "JP344") (pin "1") (pinfunction "1_1") (pintype "passive"))
      (node (ref "JP831") (pin "1") (pinfunction "1_1") (pintype "passive"))
      (node (ref "JP832") (pin "1") (pinfunction "1_1") (pintype "passive"))
    )
    (net (code "5") (name "/N$16") (class "Default")
      (node (ref "GATE1") (pin "2") (pinfunction "2_2") (pintype "passive"))
      (node (ref "JP725") (pin "1") (pinfunction "1_1") (pintype "passive"))
      (node (ref "JP733") (pin "1") (pinfunction "1_1") (pintype "passive"))
      (node (ref "U$2") (pin "P$2") (pinfunction "1_P$2") (pintype "passive"))
    )
    (net (code "6") (name "/SCK") (class "Default")
      (node (ref "ARD2") (pin "1") (pinfunction "1_1") (pintype "passive"))
      (node (ref "JP345") (pin "1") (pinfunction "1_1") (pintype "passive"))
      (node (ref "JP795") (pin "1") (pinfunction "1_1") (pintype "passive"))
      (node (ref "JP796") (pin "1") (pinfunction "1_1") (pintype "passive"))
    )
    (net (code "7") (name "/VREF") (class "Default")
      (node (ref "ARD2") (pin "3") (pinfunction "3_3") (pintype "passive"))
      (node (ref "C13") (pin "+") (pinfunction "+_+") (pintype "passive"))
      (node (ref "IC1") (pin "2") (pinfunction "VO_2") (pintype "output"))
      (node (ref "JP781") (pin "1") (pinfunction "1_1") (pintype "passive"))
      (node (ref "JP782") (pin "1") (pinfunction "1_1") (pintype "passive"))
      (node (ref "JP783") (pin "1") (pinfunction "1_1") (pintype "passive"))
    )
    (net (code "8") (name "GND") (class "Default")
      (node (ref "ARD1") (pin "12") (pinfunction "12_12") (pintype "passive"))
      (node (ref "ARD2") (pin "14") (pinfunction "14_14") (pintype "passive"))
      (node (ref "C13") (pin "-") (pinfunction "-_-") (pintype "passive"))
      (node (ref "C6") (pin "2") (pinfunction "2_2") (pintype "passive"))
      (node (ref "C8") (pin "-") (pinfunction "-_-") (pintype "passive"))
      (node (ref "C9") (pin "+") (pinfunction "+_+") (pintype "passive"))
      (node (ref "GATE1") (pin "1") (pinfunction "1_1") (pintype "passive"))
      (node (ref "GATE2") (pin "1") (pinfunction "1_1") (pintype "passive"))
      (node (ref "IC1") (pin "1") (pinfunction "GND_1") (pintype "passive"))
      (node (ref "IC3") (pin "2") (pinfunction "GND_2") (pintype "passive"))
      (node (ref "JP154") (pin "1") (pinfunction "1_1") (pintype "passive"))
      (node (ref "JP155") (pin "1") (pinfunction "1_1") (pintype "passive"))
      (node (ref "JP156") (pin "1") (pinfunction "1_1") (pintype "passive"))
      (node (ref "JP157") (pin "1") (pinfunction "1_1") (pintype "passive"))
      (node (ref "JP158") (pin "1") (pinfunction "1_1") (pintype "passive"))
      (node (ref "JP159") (pin "1") (pinfunction "1_1") (pintype "passive"))
      (node (ref "JP160") (pin "1") (pinfunction "1_1") (pintype "passive"))
      (node (ref "JP161") (pin "1") (pinfunction "1_1") (pintype "passive"))
      (node (ref "JP162") (pin "1") (pinfunction "1_1") (pintype "passive"))
      (node (ref "JP163") (pin "1") (pinfunction "1_1") (pintype "passive"))
      (node (ref "JP164") (pin "1") (pinfunction "1_1") (pintype "passive"))
      (node (ref "JP165") (pin "1") (pinfunction "1_1") (pintype "passive"))
      (node (ref "JP166") (pin "1") (pinfunction "1_1") (pintype "passive"))
      (node (ref "JP167") (pin "1") (pinfunction "1_1") (pintype "passive"))
      (node (ref "JP168") (pin "1") (pinfunction "1_1") (pintype "passive"))
      (node (ref "JP169") (pin "1") (pinfunction "1_1") (pintype "passive"))
      (node (ref "JP170") (pin "1") (pinfunction "1_1") (pintype "passive"))
      (node (ref "JP171") (pin "1") (pinfunction "1_1") (pintype "passive"))
      (node (ref "JP172") (pin "1") (pinfunction "1_1") (pintype "passive"))
      (node (ref "JP173") (pin "1") (pinfunction "1_1") (pintype "passive"))
      (node (ref "JP174") (pin "1") (pinfunction "1_1") (pintype "passive"))
      (node (ref "JP175") (pin "1") (pinfunction "1_1") (pintype "passive"))
      (node (ref "JP176") (pin "1") (pinfunction "1_1") (pintype "passive"))
      (node (ref "JP177") (pin "1") (pinfunction "1_1") (pintype "passive"))
      (node (ref "JP178") (pin "1") (pinfunction "1_1") (pintype "passive"))
      (node (ref "JP179") (pin "1") (pinfunction "1_1") (pintype "passive"))
      (node (ref "JP180") (pin "1") (pinfunction "1_1") (pintype "passive"))
      (node (ref "JP181") (pin "1") (pinfunction "1_1") (pintype "passive"))
      (node (ref "JP182") (pin "1") (pinfunction "1_1") (pintype "passive"))
      (node (ref "JP183") (pin "1") (pinfunction "1_1") (pintype "passive"))
      (node (ref "JP184") (pin "1") (pinfunction "1_1") (pintype "passive"))
      (node (ref "JP185") (pin "1") (pinfunction "1_1") (pintype "passive"))
      (node (ref "JP186") (pin "1") (pinfunction "1_1") (pintype "passive"))
      (node (ref "JP187") (pin "1") (pinfunction "1_1") (pintype "passive"))
      (node (ref "JP188") (pin "1") (pinfunction "1_1") (pintype "passive"))
      (node (ref "JP189") (pin "1") (pinfunction "1_1") (pintype "passive"))
      (node (ref "JP190") (pin "1") (pinfunction "1_1") (pintype "passive"))
      (node (ref "JP305") (pin "1") (pinfunction "1_1") (pintype "passive"))
      (node (ref "JP306") (pin "1") (pinfunction "1_1") (pintype "passive"))
      (node (ref "JP307") (pin "1") (pinfunction "1_1") (pintype "passive"))
      (node (ref "JP308") (pin "1") (pinfunction "1_1") (pintype "passive"))
      (node (ref "JP309") (pin "1") (pinfunction "1_1") (pintype "passive"))
      (node (ref "JP310") (pin "1") (pinfunction "1_1") (pintype "passive"))
      (node (ref "JP311") (pin "1") (pinfunction "1_1") (pintype "passive"))
      (node (ref "JP312") (pin "1") (pinfunction "1_1") (pintype "passive"))
      (node (ref "JP313") (pin "1") (pinfunction "1_1") (pintype "passive"))
      (node (ref "JP314") (pin "1") (pinfunction "1_1") (pintype "passive"))
      (node (ref "JP315") (pin "1") (pinfunction "1_1") (pintype "passive"))
      (node (ref "JP316") (pin "1") (pinfunction "1_1") (pintype "passive"))
      (node (ref "JP317") (pin "1") (pinfunction "1_1") (pintype "passive"))
      (node (ref "JP318") (pin "1") (pinfunction "1_1") (pintype "passive"))
      (node (ref "JP319") (pin "1") (pinfunction "1_1") (pintype "passive"))
      (node (ref "JP320") (pin "1") (pinfunction "1_1") (pintype "passive"))
      (node (ref "JP321") (pin "1") (pinfunction "1_1") (pintype "passive"))
      (node (ref "JP322") (pin "1") (pinfunction "1_1") (pintype "passive"))
      (node (ref "JP323") (pin "1") (pinfunction "1_1") (pintype "passive"))
      (node (ref "JP324") (pin "1") (pinfunction "1_1") (pintype "passive"))
      (node (ref "JP325") (pin "1") (pinfunction "1_1") (pintype "passive"))
      (node (ref "JP326") (pin "1") (pinfunction "1_1") (pintype "passive"))
      (node (ref "JP327") (pin "1") (pinfunction "1_1") (pintype "passive"))
      (node (ref "JP328") (pin "1") (pinfunction "1_1") (pintype "passive"))
      (node (ref "JP329") (pin "1") (pinfunction "1_1") (pintype "passive"))
      (node (ref "JP330") (pin "1") (pinfunction "1_1") (pintype "passive"))
      (node (ref "JP331") (pin "1") (pinfunction "1_1") (pintype "passive"))
      (node (ref "JP332") (pin "1") (pinfunction "1_1") (pintype "passive"))
      (node (ref "JP333") (pin "1") (pinfunction "1_1") (pintype "passive"))
      (node (ref "JP334") (pin "1") (pinfunction "1_1") (pintype "passive"))
      (node (ref "JP335") (pin "1") (pinfunction "1_1") (pintype "passive"))
      (node (ref "JP336") (pin "1") (pinfunction "1_1") (pintype "passive"))
      (node (ref "JP337") (pin "1") (pinfunction "1_1") (pintype "passive"))
      (node (ref "JP338") (pin "1") (pinfunction "1_1") (pintype "passive"))
      (node (ref "JP339") (pin "1") (pinfunction "1_1") (pintype "passive"))
      (node (ref "JP340") (pin "1") (pinfunction "1_1") (pintype "passive"))
      (node (ref "JP341") (pin "1") (pinfunction "1_1") (pintype "passive"))
      (node (ref "JP342") (pin "1") (pinfunction "1_1") (pintype "passive"))
      (node (ref "JP343") (pin "1") (pinfunction "1_1") (pintype "passive"))
      (node (ref "JP779") (pin "1") (pinfunction "1_1") (pintype "passive"))
      (node (ref "JP788") (pin "1") (pinfunction "1_1") (pintype "passive"))
      (node (ref "POWER") (pin "3") (pinfunction "3_3") (pintype "passive"))
      (node (ref "POWER") (pin "4") (pinfunction "4_4") (pintype "passive"))
      (node (ref "POWER") (pin "5") (pinfunction "5_5") (pintype "passive"))
      (node (ref "POWER") (pin "6") (pinfunction "6_6") (pintype "passive"))
      (node (ref "POWER") (pin "7") (pinfunction "7_7") (pintype "passive"))
      (node (ref "POWER") (pin "8") (pinfunction "8_8") (pintype "passive"))
      (node (ref "U$2") (pin "P$3") (pinfunction "1_P$3") (pintype "passive"))
    )
    (net (code "9") (name "Net-(ARD1-Pad1)") (class "Default")
      (node (ref "ARD1") (pin "1") (pinfunction "1_1") (pintype "passive"))
      (node (ref "JP833") (pin "1") (pinfunction "1_1") (pintype "passive"))
      (node (ref "JP834") (pin "1") (pinfunction "1_1") (pintype "passive"))
    )
    (net (code "10") (name "Net-(ARD1-Pad3)") (class "Default")
      (node (ref "ARD1") (pin "3") (pinfunction "3_3") (pintype "passive"))
      (node (ref "JP829") (pin "1") (pinfunction "1_1") (pintype "passive"))
      (node (ref "JP830") (pin "1") (pinfunction "1_1") (pintype "passive"))
    )
    (net (code "11") (name "Net-(ARD1-Pad4)") (class "Default")
      (node (ref "ARD1") (pin "4") (pinfunction "4_4") (pintype "passive"))
      (node (ref "JP827") (pin "1") (pinfunction "1_1") (pintype "passive"))
      (node (ref "JP828") (pin "1") (pinfunction "1_1") (pintype "passive"))
    )
    (net (code "12") (name "Net-(ARD1-Pad5)") (class "Default")
      (node (ref "ARD1") (pin "5") (pinfunction "5_5") (pintype "passive"))
      (node (ref "JP825") (pin "1") (pinfunction "1_1") (pintype "passive"))
      (node (ref "JP826") (pin "1") (pinfunction "1_1") (pintype "passive"))
    )
    (net (code "13") (name "Net-(ARD1-Pad6)") (class "Default")
      (node (ref "ARD1") (pin "6") (pinfunction "6_6") (pintype "passive"))
      (node (ref "JP823") (pin "1") (pinfunction "1_1") (pintype "passive"))
      (node (ref "JP824") (pin "1") (pinfunction "1_1") (pintype "passive"))
    )
    (net (code "14") (name "Net-(ARD1-Pad7)") (class "Default")
      (node (ref "ARD1") (pin "7") (pinfunction "7_7") (pintype "passive"))
      (node (ref "JP821") (pin "1") (pinfunction "1_1") (pintype "passive"))
      (node (ref "JP822") (pin "1") (pinfunction "1_1") (pintype "passive"))
    )
    (net (code "15") (name "Net-(ARD1-Pad8)") (class "Default")
      (node (ref "ARD1") (pin "8") (pinfunction "8_8") (pintype "passive"))
      (node (ref "JP819") (pin "1") (pinfunction "1_1") (pintype "passive"))
      (node (ref "JP820") (pin "1") (pinfunction "1_1") (pintype "passive"))
    )
    (net (code "16") (name "Net-(ARD1-Pad9)") (class "Default")
      (node (ref "ARD1") (pin "9") (pinfunction "9_9") (pintype "passive"))
      (node (ref "JP835") (pin "1") (pinfunction "1_1") (pintype "passive"))
      (node (ref "JP836") (pin "1") (pinfunction "1_1") (pintype "passive"))
    )
    (net (code "17") (name "Net-(ARD1-Pad10)") (class "Default")
      (node (ref "ARD1") (pin "10") (pinfunction "10_10") (pintype "passive"))
      (node (ref "JP817") (pin "1") (pinfunction "1_1") (pintype "passive"))
      (node (ref "JP818") (pin "1") (pinfunction "1_1") (pintype "passive"))
    )
    (net (code "18") (name "Net-(ARD1-Pad11)") (class "Default")
      (node (ref "ARD1") (pin "11") (pinfunction "11_11") (pintype "passive"))
      (node (ref "JP799") (pin "1") (pinfunction "1_1") (pintype "passive"))
      (node (ref "JP800") (pin "1") (pinfunction "1_1") (pintype "passive"))
    )
    (net (code "19") (name "Net-(ARD1-Pad13)") (class "Default")
      (node (ref "ARD1") (pin "13") (pinfunction "13_13") (pintype "passive"))
      (node (ref "JP841") (pin "1") (pinfunction "1_1") (pintype "passive"))
      (node (ref "JP842") (pin "1") (pinfunction "1_1") (pintype "passive"))
    )
    (net (code "20") (name "Net-(ARD1-Pad14)") (class "Default")
      (node (ref "ARD1") (pin "14") (pinfunction "14_14") (pintype "passive"))
      (node (ref "JP837") (pin "1") (pinfunction "1_1") (pintype "passive"))
      (node (ref "JP838") (pin "1") (pinfunction "1_1") (pintype "passive"))
    )
    (net (code "21") (name "Net-(ARD1-Pad15)") (class "Default")
      (node (ref "ARD1") (pin "15") (pinfunction "15_15") (pintype "passive"))
      (node (ref "JP839") (pin "1") (pinfunction "1_1") (pintype "passive"))
      (node (ref "JP840") (pin "1") (pinfunction "1_1") (pintype "passive"))
    )
    (net (code "22") (name "Net-(ARD2-Pad2)") (class "Default")
      (node (ref "ARD2") (pin "2") (pinfunction "2_2") (pintype "passive"))
      (node (ref "JP797") (pin "1") (pinfunction "1_1") (pintype "passive"))
      (node (ref "JP798") (pin "1") (pinfunction "1_1") (pintype "passive"))
    )
    (net (code "23") (name "Net-(ARD2-Pad4)") (class "Default")
      (node (ref "ARD2") (pin "4") (pinfunction "4_4") (pintype "passive"))
      (node (ref "JP801") (pin "1") (pinfunction "1_1") (pintype "passive"))
      (node (ref "JP802") (pin "1") (pinfunction "1_1") (pintype "passive"))
    )
    (net (code "24") (name "Net-(ARD2-Pad5)") (class "Default")
      (node (ref "ARD2") (pin "5") (pinfunction "5_5") (pintype "passive"))
      (node (ref "JP803") (pin "1") (pinfunction "1_1") (pintype "passive"))
      (node (ref "JP804") (pin "1") (pinfunction "1_1") (pintype "passive"))
    )
    (net (code "25") (name "Net-(ARD2-Pad6)") (class "Default")
      (node (ref "ARD2") (pin "6") (pinfunction "6_6") (pintype "passive"))
      (node (ref "JP805") (pin "1") (pinfunction "1_1") (pintype "passive"))
      (node (ref "JP806") (pin "1") (pinfunction "1_1") (pintype "passive"))
    )
    (net (code "26") (name "Net-(ARD2-Pad7)") (class "Default")
      (node (ref "ARD2") (pin "7") (pinfunction "7_7") (pintype "passive"))
      (node (ref "JP807") (pin "1") (pinfunction "1_1") (pintype "passive"))
      (node (ref "JP808") (pin "1") (pinfunction "1_1") (pintype "passive"))
    )
    (net (code "27") (name "Net-(ARD2-Pad8)") (class "Default")
      (node (ref "ARD2") (pin "8") (pinfunction "8_8") (pintype "passive"))
      (node (ref "JP809") (pin "1") (pinfunction "1_1") (pintype "passive"))
      (node (ref "JP810") (pin "1") (pinfunction "1_1") (pintype "passive"))
    )
    (net (code "28") (name "Net-(ARD2-Pad9)") (class "Default")
      (node (ref "ARD2") (pin "9") (pinfunction "9_9") (pintype "passive"))
      (node (ref "JP811") (pin "1") (pinfunction "1_1") (pintype "passive"))
      (node (ref "JP812") (pin "1") (pinfunction "1_1") (pintype "passive"))
    )
    (net (code "29") (name "Net-(ARD2-Pad10)") (class "Default")
      (node (ref "ARD2") (pin "10") (pinfunction "10_10") (pintype "passive"))
      (node (ref "JP813") (pin "1") (pinfunction "1_1") (pintype "passive"))
      (node (ref "JP814") (pin "1") (pinfunction "1_1") (pintype "passive"))
    )
    (net (code "30") (name "Net-(ARD2-Pad11)") (class "Default")
      (node (ref "ARD2") (pin "11") (pinfunction "11_11") (pintype "passive"))
      (node (ref "JP815") (pin "1") (pinfunction "1_1") (pintype "passive"))
      (node (ref "JP816") (pin "1") (pinfunction "1_1") (pintype "passive"))
    )
    (net (code "31") (name "Net-(GATE1-Pad3)") (class "Default")
      (node (ref "GATE1") (pin "3") (pinfunction "3_3") (pintype "passive"))
      (node (ref "JP726") (pin "1") (pinfunction "1_1") (pintype "passive"))
      (node (ref "JP734") (pin "1") (pinfunction "1_1") (pintype "passive"))
    )
    (net (code "32") (name "Net-(GATE1-Pad4)") (class "Default")
      (node (ref "GATE1") (pin "4") (pinfunction "4_4") (pintype "passive"))
      (node (ref "JP727") (pin "1") (pinfunction "1_1") (pintype "passive"))
      (node (ref "JP736") (pin "1") (pinfunction "1_1") (pintype "passive"))
    )
    (net (code "33") (name "Net-(GATE1-Pad5)") (class "Default")
      (node (ref "GATE1") (pin "5") (pinfunction "5_5") (pintype "passive"))
      (node (ref "JP728") (pin "1") (pinfunction "1_1") (pintype "passive"))
      (node (ref "JP735") (pin "1") (pinfunction "1_1") (pintype "passive"))
    )
    (net (code "34") (name "Net-(GATE2-Pad2)") (class "Default")
      (node (ref "GATE2") (pin "2") (pinfunction "2_2") (pintype "passive"))
      (node (ref "JP729") (pin "1") (pinfunction "1_1") (pintype "passive"))
      (node (ref "JP737") (pin "1") (pinfunction "1_1") (pintype "passive"))
    )
    (net (code "35") (name "Net-(GATE2-Pad3)") (class "Default")
      (node (ref "GATE2") (pin "3") (pinfunction "3_3") (pintype "passive"))
      (node (ref "JP730") (pin "1") (pinfunction "1_1") (pintype "passive"))
      (node (ref "JP738") (pin "1") (pinfunction "1_1") (pintype "passive"))
    )
    (net (code "36") (name "Net-(GATE2-Pad4)") (class "Default")
      (node (ref "GATE2") (pin "4") (pinfunction "4_4") (pintype "passive"))
      (node (ref "JP731") (pin "1") (pinfunction "1_1") (pintype "passive"))
      (node (ref "JP739") (pin "1") (pinfunction "1_1") (pintype "passive"))
    )
    (net (code "37") (name "Net-(GATE2-Pad5)") (class "Default")
      (node (ref "GATE2") (pin "5") (pinfunction "5_5") (pintype "passive"))
      (node (ref "JP732") (pin "1") (pinfunction "1_1") (pintype "passive"))
      (node (ref "JP740") (pin "1") (pinfunction "1_1") (pintype "passive"))
    )
    (net (code "38") (name "Net-(JP46-Pad1)") (class "Default")
      (node (ref "JP46") (pin "1") (pinfunction "1_1") (pintype "passive"))
      (node (ref "JP48") (pin "1") (pinfunction "1_1") (pintype "passive"))
    )
    (net (code "39") (name "Net-(JP50-Pad1)") (class "Default")
      (node (ref "JP50") (pin "1") (pinfunction "1_1") (pintype "passive"))
      (node (ref "JP52") (pin "1") (pinfunction "1_1") (pintype "passive"))
    )
    (net (code "40") (name "Net-(JP54-Pad1)") (class "Default")
      (node (ref "JP54") (pin "1") (pinfunction "1_1") (pintype "passive"))
      (node (ref "JP56") (pin "1") (pinfunction "1_1") (pintype "passive"))
    )
    (net (code "41") (name "Net-(JP58-Pad1)") (class "Default")
      (node (ref "JP58") (pin "1") (pinfunction "1_1") (pintype "passive"))
      (node (ref "JP60") (pin "1") (pinfunction "1_1") (pintype "passive"))
    )
    (net (code "42") (name "Net-(JP62-Pad1)") (class "Default")
      (node (ref "JP62") (pin "1") (pinfunction "1_1") (pintype "passive"))
      (node (ref "JP64") (pin "1") (pinfunction "1_1") (pintype "passive"))
    )
    (net (code "43") (name "Net-(JP66-Pad1)") (class "Default")
      (node (ref "JP66") (pin "1") (pinfunction "1_1") (pintype "passive"))
      (node (ref "JP68") (pin "1") (pinfunction "1_1") (pintype "passive"))
    )
    (net (code "44") (name "Net-(JP69-Pad1)") (class "Default")
      (node (ref "JP69") (pin "1") (pinfunction "1_1") (pintype "passive"))
      (node (ref "JP70") (pin "1") (pinfunction "1_1") (pintype "passive"))
    )
    (net (code "45") (name "Net-(JP71-Pad1)") (class "Default")
      (node (ref "JP71") (pin "1") (pinfunction "1_1") (pintype "passive"))
      (node (ref "JP72") (pin "1") (pinfunction "1_1") (pintype "passive"))
    )
    (net (code "46") (name "Net-(JP73-Pad1)") (class "Default")
      (node (ref "JP73") (pin "1") (pinfunction "1_1") (pintype "passive"))
      (node (ref "JP74") (pin "1") (pinfunction "1_1") (pintype "passive"))
    )
    (net (code "47") (name "Net-(JP75-Pad1)") (class "Default")
      (node (ref "JP75") (pin "1") (pinfunction "1_1") (pintype "passive"))
      (node (ref "JP76") (pin "1") (pinfunction "1_1") (pintype "passive"))
    )
    (net (code "48") (name "Net-(JP77-Pad1)") (class "Default")
      (node (ref "JP77") (pin "1") (pinfunction "1_1") (pintype "passive"))
      (node (ref "JP78") (pin "1") (pinfunction "1_1") (pintype "passive"))
    )
    (net (code "49") (name "Net-(JP79-Pad1)") (class "Default")
      (node (ref "JP79") (pin "1") (pinfunction "1_1") (pintype "passive"))
      (node (ref "JP80") (pin "1") (pinfunction "1_1") (pintype "passive"))
    )
    (net (code "50") (name "Net-(JP81-Pad1)") (class "Default")
      (node (ref "JP81") (pin "1") (pinfunction "1_1") (pintype "passive"))
      (node (ref "JP82") (pin "1") (pinfunction "1_1") (pintype "passive"))
    )
    (net (code "51") (name "Net-(JP83-Pad1)") (class "Default")
      (node (ref "JP83") (pin "1") (pinfunction "1_1") (pintype "passive"))
      (node (ref "JP84") (pin "1") (pinfunction "1_1") (pintype "passive"))
    )
    (net (code "52") (name "Net-(JP85-Pad1)") (class "Default")
      (node (ref "JP85") (pin "1") (pinfunction "1_1") (pintype "passive"))
      (node (ref "JP86") (pin "1") (pinfunction "1_1") (pintype "passive"))
    )
    (net (code "53") (name "Net-(JP88-Pad1)") (class "Default")
      (node (ref "JP88") (pin "1") (pinfunction "1_1") (pintype "passive"))
      (node (ref "JP89") (pin "1") (pinfunction "1_1") (pintype "passive"))
    )
    (net (code "54") (name "Net-(JP90-Pad1)") (class "Default")
      (node (ref "JP90") (pin "1") (pinfunction "1_1") (pintype "passive"))
      (node (ref "JP93") (pin "1") (pinfunction "1_1") (pintype "passive"))
    )
    (net (code "55") (name "Net-(JP91-Pad1)") (class "Default")
      (node (ref "JP91") (pin "1") (pinfunction "1_1") (pintype "passive"))
      (node (ref "JP92") (pin "1") (pinfunction "1_1") (pintype "passive"))
    )
    (net (code "56") (name "Net-(JP94-Pad1)") (class "Default")
      (node (ref "JP94") (pin "1") (pinfunction "1_1") (pintype "passive"))
      (node (ref "JP95") (pin "1") (pinfunction "1_1") (pintype "passive"))
    )
    (net (code "57") (name "Net-(JP96-Pad1)") (class "Default")
      (node (ref "JP96") (pin "1") (pinfunction "1_1") (pintype "passive"))
      (node (ref "JP97") (pin "1") (pinfunction "1_1") (pintype "passive"))
    )
    (net (code "58") (name "Net-(JP98-Pad1)") (class "Default")
      (node (ref "JP98") (pin "1") (pinfunction "1_1") (pintype "passive"))
      (node (ref "JP99") (pin "1") (pinfunction "1_1") (pintype "passive"))
    )
    (net (code "59") (name "Net-(JP100-Pad1)") (class "Default")
      (node (ref "JP100") (pin "1") (pinfunction "1_1") (pintype "passive"))
      (node (ref "JP101") (pin "1") (pinfunction "1_1") (pintype "passive"))
    )
    (net (code "60") (name "Net-(JP102-Pad1)") (class "Default")
      (node (ref "JP102") (pin "1") (pinfunction "1_1") (pintype "passive"))
      (node (ref "JP103") (pin "1") (pinfunction "1_1") (pintype "passive"))
      (node (ref "JP790") (pin "1") (pinfunction "1_1") (pintype "passive"))
    )
    (net (code "61") (name "Net-(JP104-Pad1)") (class "Default")
      (node (ref "JP104") (pin "1") (pinfunction "1_1") (pintype "passive"))
      (node (ref "JP105") (pin "1") (pinfunction "1_1") (pintype "passive"))
    )
    (net (code "62") (name "Net-(JP106-Pad1)") (class "Default")
      (node (ref "JP106") (pin "1") (pinfunction "1_1") (pintype "passive"))
      (node (ref "JP107") (pin "1") (pinfunction "1_1") (pintype "passive"))
    )
    (net (code "63") (name "Net-(JP108-Pad1)") (class "Default")
      (node (ref "JP108") (pin "1") (pinfunction "1_1") (pintype "passive"))
      (node (ref "JP109") (pin "1") (pinfunction "1_1") (pintype "passive"))
    )
    (net (code "64") (name "Net-(JP110-Pad1)") (class "Default")
      (node (ref "JP110") (pin "1") (pinfunction "1_1") (pintype "passive"))
      (node (ref "JP111") (pin "1") (pinfunction "1_1") (pintype "passive"))
    )
    (net (code "65") (name "Net-(JP112-Pad1)") (class "Default")
      (node (ref "JP112") (pin "1") (pinfunction "1_1") (pintype "passive"))
      (node (ref "JP113") (pin "1") (pinfunction "1_1") (pintype "passive"))
    )
    (net (code "66") (name "Net-(JP116-Pad1)") (class "Default")
      (node (ref "JP116") (pin "1") (pinfunction "1_1") (pintype "passive"))
      (node (ref "JP789") (pin "1") (pinfunction "1_1") (pintype "passive"))
      (node (ref "JP87") (pin "1") (pinfunction "1_1") (pintype "passive"))
    )
    (net (code "67") (name "Net-(JP193-Pad1)") (class "Default")
      (node (ref "JP193") (pin "1") (pinfunction "1_1") (pintype "passive"))
      (node (ref "JP194") (pin "1") (pinfunction "1_1") (pintype "passive"))
      (node (ref "JP195") (pin "1") (pinfunction "1_1") (pintype "passive"))
      (node (ref "JP196") (pin "1") (pinfunction "1_1") (pintype "passive"))
      (node (ref "JP197") (pin "1") (pinfunction "1_1") (pintype "passive"))
      (node (ref "JP198") (pin "1") (pinfunction "1_1") (pintype "passive"))
      (node (ref "JP199") (pin "1") (pinfunction "1_1") (pintype "passive"))
      (node (ref "JP200") (pin "1") (pinfunction "1_1") (pintype "passive"))
      (node (ref "JP201") (pin "1") (pinfunction "1_1") (pintype "passive"))
      (node (ref "JP202") (pin "1") (pinfunction "1_1") (pintype "passive"))
      (node (ref "JP203") (pin "1") (pinfunction "1_1") (pintype "passive"))
      (node (ref "JP204") (pin "1") (pinfunction "1_1") (pintype "passive"))
      (node (ref "JP205") (pin "1") (pinfunction "1_1") (pintype "passive"))
      (node (ref "JP206") (pin "1") (pinfunction "1_1") (pintype "passive"))
      (node (ref "JP207") (pin "1") (pinfunction "1_1") (pintype "passive"))
      (node (ref "JP208") (pin "1") (pinfunction "1_1") (pintype "passive"))
      (node (ref "JP209") (pin "1") (pinfunction "1_1") (pintype "passive"))
      (node (ref "JP210") (pin "1") (pinfunction "1_1") (pintype "passive"))
      (node (ref "JP211") (pin "1") (pinfunction "1_1") (pintype "passive"))
      (node (ref "JP212") (pin "1") (pinfunction "1_1") (pintype "passive"))
      (node (ref "JP213") (pin "1") (pinfunction "1_1") (pintype "passive"))
      (node (ref "JP214") (pin "1") (pinfunction "1_1") (pintype "passive"))
      (node (ref "JP215") (pin "1") (pinfunction "1_1") (pintype "passive"))
      (node (ref "JP216") (pin "1") (pinfunction "1_1") (pintype "passive"))
      (node (ref "JP217") (pin "1") (pinfunction "1_1") (pintype "passive"))
      (node (ref "JP218") (pin "1") (pinfunction "1_1") (pintype "passive"))
      (node (ref "JP219") (pin "1") (pinfunction "1_1") (pintype "passive"))
      (node (ref "JP220") (pin "1") (pinfunction "1_1") (pintype "passive"))
      (node (ref "JP221") (pin "1") (pinfunction "1_1") (pintype "passive"))
      (node (ref "JP222") (pin "1") (pinfunction "1_1") (pintype "passive"))
      (node (ref "JP223") (pin "1") (pinfunction "1_1") (pintype "passive"))
      (node (ref "JP224") (pin "1") (pinfunction "1_1") (pintype "passive"))
      (node (ref "JP225") (pin "1") (pinfunction "1_1") (pintype "passive"))
      (node (ref "JP226") (pin "1") (pinfunction "1_1") (pintype "passive"))
      (node (ref "JP227") (pin "1") (pinfunction "1_1") (pintype "passive"))
      (node (ref "JP228") (pin "1") (pinfunction "1_1") (pintype "passive"))
      (node (ref "JP724") (pin "1") (pinfunction "1_1") (pintype "passive"))
    )
    (net (code "68") (name "Net-(JP230-Pad1)") (class "Default")
      (node (ref "JP230") (pin "1") (pinfunction "1_1") (pintype "passive"))
      (node (ref "JP232") (pin "1") (pinfunction "1_1") (pintype "passive"))
      (node (ref "JP233") (pin "1") (pinfunction "1_1") (pintype "passive"))
      (node (ref "JP234") (pin "1") (pinfunction "1_1") (pintype "passive"))
      (node (ref "JP235") (pin "1") (pinfunction "1_1") (pintype "passive"))
      (node (ref "JP236") (pin "1") (pinfunction "1_1") (pintype "passive"))
      (node (ref "JP237") (pin "1") (pinfunction "1_1") (pintype "passive"))
      (node (ref "JP238") (pin "1") (pinfunction "1_1") (pintype "passive"))
      (node (ref "JP239") (pin "1") (pinfunction "1_1") (pintype "passive"))
      (node (ref "JP240") (pin "1") (pinfunction "1_1") (pintype "passive"))
      (node (ref "JP241") (pin "1") (pinfunction "1_1") (pintype "passive"))
      (node (ref "JP242") (pin "1") (pinfunction "1_1") (pintype "passive"))
      (node (ref "JP243") (pin "1") (pinfunction "1_1") (pintype "passive"))
      (node (ref "JP244") (pin "1") (pinfunction "1_1") (pintype "passive"))
      (node (ref "JP245") (pin "1") (pinfunction "1_1") (pintype "passive"))
      (node (ref "JP246") (pin "1") (pinfunction "1_1") (pintype "passive"))
      (node (ref "JP247") (pin "1") (pinfunction "1_1") (pintype "passive"))
      (node (ref "JP248") (pin "1") (pinfunction "1_1") (pintype "passive"))
      (node (ref "JP249") (pin "1") (pinfunction "1_1") (pintype "passive"))
      (node (ref "JP250") (pin "1") (pinfunction "1_1") (pintype "passive"))
      (node (ref "JP251") (pin "1") (pinfunction "1_1") (pintype "passive"))
      (node (ref "JP252") (pin "1") (pinfunction "1_1") (pintype "passive"))
      (node (ref "JP253") (pin "1") (pinfunction "1_1") (pintype "passive"))
      (node (ref "JP254") (pin "1") (pinfunction "1_1") (pintype "passive"))
      (node (ref "JP255") (pin "1") (pinfunction "1_1") (pintype "passive"))
      (node (ref "JP256") (pin "1") (pinfunction "1_1") (pintype "passive"))
      (node (ref "JP257") (pin "1") (pinfunction "1_1") (pintype "passive"))
      (node (ref "JP258") (pin "1") (pinfunction "1_1") (pintype "passive"))
      (node (ref "JP259") (pin "1") (pinfunction "1_1") (pintype "passive"))
      (node (ref "JP260") (pin "1") (pinfunction "1_1") (pintype "passive"))
      (node (ref "JP261") (pin "1") (pinfunction "1_1") (pintype "passive"))
      (node (ref "JP262") (pin "1") (pinfunction "1_1") (pintype "passive"))
      (node (ref "JP263") (pin "1") (pinfunction "1_1") (pintype "passive"))
      (node (ref "JP264") (pin "1") (pinfunction "1_1") (pintype "passive"))
      (node (ref "JP265") (pin "1") (pinfunction "1_1") (pintype "passive"))
      (node (ref "JP723") (pin "1") (pinfunction "1_1") (pintype "passive"))
    )
    (net (code "69") (name "Net-(R1-A)") (class "Default")
      (node (ref "JP10") (pin "1") (pinfunction "1_1") (pintype "passive"))
      (node (ref "JP11") (pin "1") (pinfunction "1_1") (pintype "passive"))
      (node (ref "JP49") (pin "1") (pinfunction "1_1") (pintype "passive"))
      (node (ref "JP9") (pin "1") (pinfunction "1_1") (pintype "passive"))
      (node (ref "R1") (pin "1") (pinfunction "A_1") (pintype "passive"))
    )
    (net (code "70") (name "Net-(R1-E)") (class "Default")
      (node (ref "JP2") (pin "1") (pinfunction "1_1") (pintype "passive"))
      (node (ref "JP3") (pin "1") (pinfunction "1_1") (pintype "passive"))
      (node (ref "JP45") (pin "1") (pinfunction "1_1") (pintype "passive"))
      (node (ref "JP5") (pin "1") (pinfunction "1_1") (pintype "passive"))
      (node (ref "R1") (pin "3") (pinfunction "E_3") (pintype "passive"))
    )
    (net (code "71") (name "Net-(R1-S)") (class "Default")
      (node (ref "JP47") (pin "1") (pinfunction "1_1") (pintype "passive"))
      (node (ref "JP6") (pin "1") (pinfunction "1_1") (pintype "passive"))
      (node (ref "JP7") (pin "1") (pinfunction "1_1") (pintype "passive"))
      (node (ref "JP8") (pin "1") (pinfunction "1_1") (pintype "passive"))
      (node (ref "R1") (pin "2") (pinfunction "S_2") (pintype "passive"))
    )
    (net (code "72") (name "Net-(R2-A)") (class "Default")
      (node (ref "JP20") (pin "1") (pinfunction "1_1") (pintype "passive"))
      (node (ref "JP21") (pin "1") (pinfunction "1_1") (pintype "passive"))
      (node (ref "JP22") (pin "1") (pinfunction "1_1") (pintype "passive"))
      (node (ref "JP55") (pin "1") (pinfunction "1_1") (pintype "passive"))
      (node (ref "R2") (pin "1") (pinfunction "A_1") (pintype "passive"))
    )
    (net (code "73") (name "Net-(R2-E)") (class "Default")
      (node (ref "JP14") (pin "1") (pinfunction "1_1") (pintype "passive"))
      (node (ref "JP15") (pin "1") (pinfunction "1_1") (pintype "passive"))
      (node (ref "JP16") (pin "1") (pinfunction "1_1") (pintype "passive"))
      (node (ref "JP51") (pin "1") (pinfunction "1_1") (pintype "passive"))
      (node (ref "R2") (pin "3") (pinfunction "E_3") (pintype "passive"))
    )
    (net (code "74") (name "Net-(R2-S)") (class "Default")
      (node (ref "JP17") (pin "1") (pinfunction "1_1") (pintype "passive"))
      (node (ref "JP18") (pin "1") (pinfunction "1_1") (pintype "passive"))
      (node (ref "JP19") (pin "1") (pinfunction "1_1") (pintype "passive"))
      (node (ref "JP53") (pin "1") (pinfunction "1_1") (pintype "passive"))
      (node (ref "R2") (pin "2") (pinfunction "S_2") (pintype "passive"))
    )
    (net (code "75") (name "Net-(R3-A)") (class "Default")
      (node (ref "JP29") (pin "1") (pinfunction "1_1") (pintype "passive"))
      (node (ref "JP30") (pin "1") (pinfunction "1_1") (pintype "passive"))
      (node (ref "JP31") (pin "1") (pinfunction "1_1") (pintype "passive"))
      (node (ref "JP61") (pin "1") (pinfunction "1_1") (pintype "passive"))
      (node (ref "R3") (pin "1") (pinfunction "A_1") (pintype "passive"))
    )
    (net (code "76") (name "Net-(R3-E)") (class "Default")
      (node (ref "JP23") (pin "1") (pinfunction "1_1") (pintype "passive"))
      (node (ref "JP24") (pin "1") (pinfunction "1_1") (pintype "passive"))
      (node (ref "JP25") (pin "1") (pinfunction "1_1") (pintype "passive"))
      (node (ref "JP57") (pin "1") (pinfunction "1_1") (pintype "passive"))
      (node (ref "R3") (pin "3") (pinfunction "E_3") (pintype "passive"))
    )
    (net (code "77") (name "Net-(R3-S)") (class "Default")
      (node (ref "JP26") (pin "1") (pinfunction "1_1") (pintype "passive"))
      (node (ref "JP27") (pin "1") (pinfunction "1_1") (pintype "passive"))
      (node (ref "JP28") (pin "1") (pinfunction "1_1") (pintype "passive"))
      (node (ref "JP59") (pin "1") (pinfunction "1_1") (pintype "passive"))
      (node (ref "R3") (pin "2") (pinfunction "S_2") (pintype "passive"))
    )
    (net (code "78") (name "Net-(R4-A)") (class "Default")
      (node (ref "JP40") (pin "1") (pinfunction "1_1") (pintype "passive"))
      (node (ref "JP41") (pin "1") (pinfunction "1_1") (pintype "passive"))
      (node (ref "JP42") (pin "1") (pinfunction "1_1") (pintype "passive"))
      (node (ref "JP67") (pin "1") (pinfunction "1_1") (pintype "passive"))
      (node (ref "R4") (pin "1") (pinfunction "A_1") (pintype "passive"))
    )
    (net (code "79") (name "Net-(R4-E)") (class "Default")
      (node (ref "JP34") (pin "1") (pinfunction "1_1") (pintype "passive"))
      (node (ref "JP35") (pin "1") (pinfunction "1_1") (pintype "passive"))
      (node (ref "JP36") (pin "1") (pinfunction "1_1") (pintype "passive"))
      (node (ref "JP63") (pin "1") (pinfunction "1_1") (pintype "passive"))
      (node (ref "R4") (pin "3") (pinfunction "E_3") (pintype "passive"))
    )
    (net (code "80") (name "Net-(R4-S)") (class "Default")
      (node (ref "JP37") (pin "1") (pinfunction "1_1") (pintype "passive"))
      (node (ref "JP38") (pin "1") (pinfunction "1_1") (pintype "passive"))
      (node (ref "JP39") (pin "1") (pinfunction "1_1") (pintype "passive"))
      (node (ref "JP65") (pin "1") (pinfunction "1_1") (pintype "passive"))
      (node (ref "R4") (pin "2") (pinfunction "S_2") (pintype "passive"))
    )
    (net (code "81") (name "unconnected-(ARD2-Pad13)") (class "Default")
      (node (ref "ARD2") (pin "13") (pinfunction "13_13") (pintype "passive"))
    )
    (net (code "82") (name "unconnected-(ARD2-Pad15)") (class "Default")
      (node (ref "ARD2") (pin "15") (pinfunction "15_15") (pintype "passive"))
    )
    (net (code "83") (name "unconnected-(JP1-Pad1)") (class "Default")
      (node (ref "JP1") (pin "1") (pinfunction "1_1") (pintype "passive"))
    )
    (net (code "84") (name "unconnected-(JP4-Pad1)") (class "Default")
      (node (ref "JP4") (pin "1") (pinfunction "1_1") (pintype "passive"))
    )
    (net (code "85") (name "unconnected-(JP12-Pad1)") (class "Default")
      (node (ref "JP12") (pin "1") (pinfunction "1_1") (pintype "passive"))
    )
    (net (code "86") (name "unconnected-(JP13-Pad1)") (class "Default")
      (node (ref "JP13") (pin "1") (pinfunction "1_1") (pintype "passive"))
    )
    (net (code "87") (name "unconnected-(JP32-Pad1)") (class "Default")
      (node (ref "JP32") (pin "1") (pinfunction "1_1") (pintype "passive"))
    )
    (net (code "88") (name "unconnected-(JP33-Pad1)") (class "Default")
      (node (ref "JP33") (pin "1") (pinfunction "1_1") (pintype "passive"))
    )
    (net (code "89") (name "unconnected-(JP43-Pad1)") (class "Default")
      (node (ref "JP43") (pin "1") (pinfunction "1_1") (pintype "passive"))
    )
    (net (code "90") (name "unconnected-(JP44-Pad1)") (class "Default")
      (node (ref "JP44") (pin "1") (pinfunction "1_1") (pintype "passive"))
    )
    (net (code "91") (name "unconnected-(JP153-Pad1)") (class "Default")
      (node (ref "JP153") (pin "1") (pinfunction "1_1") (pintype "passive"))
    )
    (net (code "92") (name "unconnected-(JP191-Pad1)") (class "Default")
      (node (ref "JP191") (pin "1") (pinfunction "1_1") (pintype "passive"))
    )
    (net (code "93") (name "unconnected-(JP192-Pad1)") (class "Default")
      (node (ref "JP192") (pin "1") (pinfunction "1_1") (pintype "passive"))
    )
    (net (code "94") (name "unconnected-(JP229-Pad1)") (class "Default")
      (node (ref "JP229") (pin "1") (pinfunction "1_1") (pintype "passive"))
    )
    (net (code "95") (name "unconnected-(JP231-Pad1)") (class "Default")
      (node (ref "JP231") (pin "1") (pinfunction "1_1") (pintype "passive"))
    )
    (net (code "96") (name "unconnected-(JP266-Pad1)") (class "Default")
      (node (ref "JP266") (pin "1") (pinfunction "1_1") (pintype "passive"))
    )
    (net (code "97") (name "unconnected-(JP346-Pad1)") (class "Default")
      (node (ref "JP346") (pin "1") (pinfunction "1_1") (pintype "passive"))
    )
    (net (code "98") (name "unconnected-(JP347-Pad1)") (class "Default")
      (node (ref "JP347") (pin "1") (pinfunction "1_1") (pintype "passive"))
    )
    (net (code "99") (name "unconnected-(JP348-Pad1)") (class "Default")
      (node (ref "JP348") (pin "1") (pinfunction "1_1") (pintype "passive"))
    )
    (net (code "100") (name "unconnected-(JP349-Pad1)") (class "Default")
      (node (ref "JP349") (pin "1") (pinfunction "1_1") (pintype "passive"))
    )
    (net (code "101") (name "unconnected-(JP350-Pad1)") (class "Default")
      (node (ref "JP350") (pin "1") (pinfunction "1_1") (pintype "passive"))
    )
    (net (code "102") (name "unconnected-(JP351-Pad1)") (class "Default")
      (node (ref "JP351") (pin "1") (pinfunction "1_1") (pintype "passive"))
    )
    (net (code "103") (name "unconnected-(JP352-Pad1)") (class "Default")
      (node (ref "JP352") (pin "1") (pinfunction "1_1") (pintype "passive"))
    )
    (net (code "104") (name "unconnected-(JP353-Pad1)") (class "Default")
      (node (ref "JP353") (pin "1") (pinfunction "1_1") (pintype "passive"))
    )
    (net (code "105") (name "unconnected-(JP354-Pad1)") (class "Default")
      (node (ref "JP354") (pin "1") (pinfunction "1_1") (pintype "passive"))
    )
    (net (code "106") (name "unconnected-(JP355-Pad1)") (class "Default")
      (node (ref "JP355") (pin "1") (pinfunction "1_1") (pintype "passive"))
    )
    (net (code "107") (name "unconnected-(JP356-Pad1)") (class "Default")
      (node (ref "JP356") (pin "1") (pinfunction "1_1") (pintype "passive"))
    )
    (net (code "108") (name "unconnected-(JP357-Pad1)") (class "Default")
      (node (ref "JP357") (pin "1") (pinfunction "1_1") (pintype "passive"))
    )
    (net (code "109") (name "unconnected-(JP358-Pad1)") (class "Default")
      (node (ref "JP358") (pin "1") (pinfunction "1_1") (pintype "passive"))
    )
    (net (code "110") (name "unconnected-(JP359-Pad1)") (class "Default")
      (node (ref "JP359") (pin "1") (pinfunction "1_1") (pintype "passive"))
    )
    (net (code "111") (name "unconnected-(JP360-Pad1)") (class "Default")
      (node (ref "JP360") (pin "1") (pinfunction "1_1") (pintype "passive"))
    )
    (net (code "112") (name "unconnected-(JP361-Pad1)") (class "Default")
      (node (ref "JP361") (pin "1") (pinfunction "1_1") (pintype "passive"))
    )
    (net (code "113") (name "unconnected-(JP362-Pad1)") (class "Default")
      (node (ref "JP362") (pin "1") (pinfunction "1_1") (pintype "passive"))
    )
    (net (code "114") (name "unconnected-(JP363-Pad1)") (class "Default")
      (node (ref "JP363") (pin "1") (pinfunction "1_1") (pintype "passive"))
    )
    (net (code "115") (name "unconnected-(JP364-Pad1)") (class "Default")
      (node (ref "JP364") (pin "1") (pinfunction "1_1") (pintype "passive"))
    )
    (net (code "116") (name "unconnected-(JP365-Pad1)") (class "Default")
      (node (ref "JP365") (pin "1") (pinfunction "1_1") (pintype "passive"))
    )
    (net (code "117") (name "unconnected-(JP366-Pad1)") (class "Default")
      (node (ref "JP366") (pin "1") (pinfunction "1_1") (pintype "passive"))
    )
    (net (code "118") (name "unconnected-(JP367-Pad1)") (class "Default")
      (node (ref "JP367") (pin "1") (pinfunction "1_1") (pintype "passive"))
    )
    (net (code "119") (name "unconnected-(JP368-Pad1)") (class "Default")
      (node (ref "JP368") (pin "1") (pinfunction "1_1") (pintype "passive"))
    )
    (net (code "120") (name "unconnected-(JP369-Pad1)") (class "Default")
      (node (ref "JP369") (pin "1") (pinfunction "1_1") (pintype "passive"))
    )
    (net (code "121") (name "unconnected-(JP370-Pad1)") (class "Default")
      (node (ref "JP370") (pin "1") (pinfunction "1_1") (pintype "passive"))
    )
    (net (code "122") (name "unconnected-(JP371-Pad1)") (class "Default")
      (node (ref "JP371") (pin "1") (pinfunction "1_1") (pintype "passive"))
    )
    (net (code "123") (name "unconnected-(JP372-Pad1)") (class "Default")
      (node (ref "JP372") (pin "1") (pinfunction "1_1") (pintype "passive"))
    )
    (net (code "124") (name "unconnected-(JP373-Pad1)") (class "Default")
      (node (ref "JP373") (pin "1") (pinfunction "1_1") (pintype "passive"))
    )
    (net (code "125") (name "unconnected-(JP374-Pad1)") (class "Default")
      (node (ref "JP374") (pin "1") (pinfunction "1_1") (pintype "passive"))
    )
    (net (code "126") (name "unconnected-(JP375-Pad1)") (class "Default")
      (node (ref "JP375") (pin "1") (pinfunction "1_1") (pintype "passive"))
    )
    (net (code "127") (name "unconnected-(JP376-Pad1)") (class "Default")
      (node (ref "JP376") (pin "1") (pinfunction "1_1") (pintype "passive"))
    )
    (net (code "128") (name "unconnected-(JP377-Pad1)") (class "Default")
      (node (ref "JP377") (pin "1") (pinfunction "1_1") (pintype "passive"))
    )
    (net (code "129") (name "unconnected-(JP378-Pad1)") (class "Default")
      (node (ref "JP378") (pin "1") (pinfunction "1_1") (pintype "passive"))
    )
    (net (code "130") (name "unconnected-(JP379-Pad1)") (class "Default")
      (node (ref "JP379") (pin "1") (pinfunction "1_1") (pintype "passive"))
    )
    (net (code "131") (name "unconnected-(JP380-Pad1)") (class "Default")
      (node (ref "JP380") (pin "1") (pinfunction "1_1") (pintype "passive"))
    )
    (net (code "132") (name "unconnected-(JP381-Pad1)") (class "Default")
      (node (ref "JP381") (pin "1") (pinfunction "1_1") (pintype "passive"))
    )
    (net (code "133") (name "unconnected-(JP382-Pad1)") (class "Default")
      (node (ref "JP382") (pin "1") (pinfunction "1_1") (pintype "passive"))
    )
    (net (code "134") (name "unconnected-(JP383-Pad1)") (class "Default")
      (node (ref "JP383") (pin "1") (pinfunction "1_1") (pintype "passive"))
    )
    (net (code "135") (name "unconnected-(JP384-Pad1)") (class "Default")
      (node (ref "JP384") (pin "1") (pinfunction "1_1") (pintype "passive"))
    )
    (net (code "136") (name "unconnected-(JP385-Pad1)") (class "Default")
      (node (ref "JP385") (pin "1") (pinfunction "1_1") (pintype "passive"))
    )
    (net (code "137") (name "unconnected-(JP386-Pad1)") (class "Default")
      (node (ref "JP386") (pin "1") (pinfunction "1_1") (pintype "passive"))
    )
    (net (code "138") (name "unconnected-(JP387-Pad1)") (class "Default")
      (node (ref "JP387") (pin "1") (pinfunction "1_1") (pintype "passive"))
    )
    (net (code "139") (name "unconnected-(JP388-Pad1)") (class "Default")
      (node (ref "JP388") (pin "1") (pinfunction "1_1") (pintype "passive"))
    )
    (net (code "140") (name "unconnected-(JP389-Pad1)") (class "Default")
      (node (ref "JP389") (pin "1") (pinfunction "1_1") (pintype "passive"))
    )
    (net (code "141") (name "unconnected-(JP390-Pad1)") (class "Default")
      (node (ref "JP390") (pin "1") (pinfunction "1_1") (pintype "passive"))
    )
    (net (code "142") (name "unconnected-(JP391-Pad1)") (class "Default")
      (node (ref "JP391") (pin "1") (pinfunction "1_1") (pintype "passive"))
    )
    (net (code "143") (name "unconnected-(JP392-Pad1)") (class "Default")
      (node (ref "JP392") (pin "1") (pinfunction "1_1") (pintype "passive"))
    )
    (net (code "144") (name "unconnected-(JP393-Pad1)") (class "Default")
      (node (ref "JP393") (pin "1") (pinfunction "1_1") (pintype "passive"))
    )
    (net (code "145") (name "unconnected-(JP394-Pad1)") (class "Default")
      (node (ref "JP394") (pin "1") (pinfunction "1_1") (pintype "passive"))
    )
    (net (code "146") (name "unconnected-(JP395-Pad1)") (class "Default")
      (node (ref "JP395") (pin "1") (pinfunction "1_1") (pintype "passive"))
    )
    (net (code "147") (name "unconnected-(JP396-Pad1)") (class "Default")
      (node (ref "JP396") (pin "1") (pinfunction "1_1") (pintype "passive"))
    )
    (net (code "148") (name "unconnected-(JP397-Pad1)") (class "Default")
      (node (ref "JP397") (pin "1") (pinfunction "1_1") (pintype "passive"))
    )
    (net (code "149") (name "unconnected-(JP398-Pad1)") (class "Default")
      (node (ref "JP398") (pin "1") (pinfunction "1_1") (pintype "passive"))
    )
    (net (code "150") (name "unconnected-(JP399-Pad1)") (class "Default")
      (node (ref "JP399") (pin "1") (pinfunction "1_1") (pintype "passive"))
    )
    (net (code "151") (name "unconnected-(JP400-Pad1)") (class "Default")
      (node (ref "JP400") (pin "1") (pinfunction "1_1") (pintype "passive"))
    )
    (net (code "152") (name "unconnected-(JP401-Pad1)") (class "Default")
      (node (ref "JP401") (pin "1") (pinfunction "1_1") (pintype "passive"))
    )
    (net (code "153") (name "unconnected-(JP402-Pad1)") (class "Default")
      (node (ref "JP402") (pin "1") (pinfunction "1_1") (pintype "passive"))
    )
    (net (code "154") (name "unconnected-(JP403-Pad1)") (class "Default")
      (node (ref "JP403") (pin "1") (pinfunction "1_1") (pintype "passive"))
    )
    (net (code "155") (name "unconnected-(JP404-Pad1)") (class "Default")
      (node (ref "JP404") (pin "1") (pinfunction "1_1") (pintype "passive"))
    )
    (net (code "156") (name "unconnected-(JP405-Pad1)") (class "Default")
      (node (ref "JP405") (pin "1") (pinfunction "1_1") (pintype "passive"))
    )
    (net (code "157") (name "unconnected-(JP406-Pad1)") (class "Default")
      (node (ref "JP406") (pin "1") (pinfunction "1_1") (pintype "passive"))
    )
    (net (code "158") (name "unconnected-(JP407-Pad1)") (class "Default")
      (node (ref "JP407") (pin "1") (pinfunction "1_1") (pintype "passive"))
    )
    (net (code "159") (name "unconnected-(JP408-Pad1)") (class "Default")
      (node (ref "JP408") (pin "1") (pinfunction "1_1") (pintype "passive"))
    )
    (net (code "160") (name "unconnected-(JP409-Pad1)") (class "Default")
      (node (ref "JP409") (pin "1") (pinfunction "1_1") (pintype "passive"))
    )
    (net (code "161") (name "unconnected-(JP410-Pad1)") (class "Default")
      (node (ref "JP410") (pin "1") (pinfunction "1_1") (pintype "passive"))
    )
    (net (code "162") (name "unconnected-(JP411-Pad1)") (class "Default")
      (node (ref "JP411") (pin "1") (pinfunction "1_1") (pintype "passive"))
    )
    (net (code "163") (name "unconnected-(JP412-Pad1)") (class "Default")
      (node (ref "JP412") (pin "1") (pinfunction "1_1") (pintype "passive"))
    )
    (net (code "164") (name "unconnected-(JP413-Pad1)") (class "Default")
      (node (ref "JP413") (pin "1") (pinfunction "1_1") (pintype "passive"))
    )
    (net (code "165") (name "unconnected-(JP414-Pad1)") (class "Default")
      (node (ref "JP414") (pin "1") (pinfunction "1_1") (pintype "passive"))
    )
    (net (code "166") (name "unconnected-(JP415-Pad1)") (class "Default")
      (node (ref "JP415") (pin "1") (pinfunction "1_1") (pintype "passive"))
    )
    (net (code "167") (name "unconnected-(JP416-Pad1)") (class "Default")
      (node (ref "JP416") (pin "1") (pinfunction "1_1") (pintype "passive"))
    )
    (net (code "168") (name "unconnected-(JP417-Pad1)") (class "Default")
      (node (ref "JP417") (pin "1") (pinfunction "1_1") (pintype "passive"))
    )
    (net (code "169") (name "unconnected-(JP418-Pad1)") (class "Default")
      (node (ref "JP418") (pin "1") (pinfunction "1_1") (pintype "passive"))
    )
    (net (code "170") (name "unconnected-(JP419-Pad1)") (class "Default")
      (node (ref "JP419") (pin "1") (pinfunction "1_1") (pintype "passive"))
    )
    (net (code "171") (name "unconnected-(JP420-Pad1)") (class "Default")
      (node (ref "JP420") (pin "1") (pinfunction "1_1") (pintype "passive"))
    )
    (net (code "172") (name "unconnected-(JP421-Pad1)") (class "Default")
      (node (ref "JP421") (pin "1") (pinfunction "1_1") (pintype "passive"))
    )
    (net (code "173") (name "unconnected-(JP422-Pad1)") (class "Default")
      (node (ref "JP422") (pin "1") (pinfunction "1_1") (pintype "passive"))
    )
    (net (code "174") (name "unconnected-(JP423-Pad1)") (class "Default")
      (node (ref "JP423") (pin "1") (pinfunction "1_1") (pintype "passive"))
    )
    (net (code "175") (name "unconnected-(JP424-Pad1)") (class "Default")
      (node (ref "JP424") (pin "1") (pinfunction "1_1") (pintype "passive"))
    )
    (net (code "176") (name "unconnected-(JP425-Pad1)") (class "Default")
      (node (ref "JP425") (pin "1") (pinfunction "1_1") (pintype "passive"))
    )
    (net (code "177") (name "unconnected-(JP426-Pad1)") (class "Default")
      (node (ref "JP426") (pin "1") (pinfunction "1_1") (pintype "passive"))
    )
    (net (code "178") (name "unconnected-(JP427-Pad1)") (class "Default")
      (node (ref "JP427") (pin "1") (pinfunction "1_1") (pintype "passive"))
    )
    (net (code "179") (name "unconnected-(JP428-Pad1)") (class "Default")
      (node (ref "JP428") (pin "1") (pinfunction "1_1") (pintype "passive"))
    )
    (net (code "180") (name "unconnected-(JP429-Pad1)") (class "Default")
      (node (ref "JP429") (pin "1") (pinfunction "1_1") (pintype "passive"))
    )
    (net (code "181") (name "unconnected-(JP430-Pad1)") (class "Default")
      (node (ref "JP430") (pin "1") (pinfunction "1_1") (pintype "passive"))
    )
    (net (code "182") (name "unconnected-(JP431-Pad1)") (class "Default")
      (node (ref "JP431") (pin "1") (pinfunction "1_1") (pintype "passive"))
    )
    (net (code "183") (name "unconnected-(JP432-Pad1)") (class "Default")
      (node (ref "JP432") (pin "1") (pinfunction "1_1") (pintype "passive"))
    )
    (net (code "184") (name "unconnected-(JP433-Pad1)") (class "Default")
      (node (ref "JP433") (pin "1") (pinfunction "1_1") (pintype "passive"))
    )
    (net (code "185") (name "unconnected-(JP434-Pad1)") (class "Default")
      (node (ref "JP434") (pin "1") (pinfunction "1_1") (pintype "passive"))
    )
    (net (code "186") (name "unconnected-(JP435-Pad1)") (class "Default")
      (node (ref "JP435") (pin "1") (pinfunction "1_1") (pintype "passive"))
    )
    (net (code "187") (name "unconnected-(JP436-Pad1)") (class "Default")
      (node (ref "JP436") (pin "1") (pinfunction "1_1") (pintype "passive"))
    )
    (net (code "188") (name "unconnected-(JP437-Pad1)") (class "Default")
      (node (ref "JP437") (pin "1") (pinfunction "1_1") (pintype "passive"))
    )
    (net (code "189") (name "unconnected-(JP438-Pad1)") (class "Default")
      (node (ref "JP438") (pin "1") (pinfunction "1_1") (pintype "passive"))
    )
    (net (code "190") (name "unconnected-(JP439-Pad1)") (class "Default")
      (node (ref "JP439") (pin "1") (pinfunction "1_1") (pintype "passive"))
    )
    (net (code "191") (name "unconnected-(JP440-Pad1)") (class "Default")
      (node (ref "JP440") (pin "1") (pinfunction "1_1") (pintype "passive"))
    )
    (net (code "192") (name "unconnected-(JP441-Pad1)") (class "Default")
      (node (ref "JP441") (pin "1") (pinfunction "1_1") (pintype "passive"))
    )
    (net (code "193") (name "unconnected-(JP442-Pad1)") (class "Default")
      (node (ref "JP442") (pin "1") (pinfunction "1_1") (pintype "passive"))
    )
    (net (code "194") (name "unconnected-(JP443-Pad1)") (class "Default")
      (node (ref "JP443") (pin "1") (pinfunction "1_1") (pintype "passive"))
    )
    (net (code "195") (name "unconnected-(JP444-Pad1)") (class "Default")
      (node (ref "JP444") (pin "1") (pinfunction "1_1") (pintype "passive"))
    )
    (net (code "196") (name "unconnected-(JP445-Pad1)") (class "Default")
      (node (ref "JP445") (pin "1") (pinfunction "1_1") (pintype "passive"))
    )
    (net (code "197") (name "unconnected-(JP446-Pad1)") (class "Default")
      (node (ref "JP446") (pin "1") (pinfunction "1_1") (pintype "passive"))
    )
    (net (code "198") (name "unconnected-(JP447-Pad1)") (class "Default")
      (node (ref "JP447") (pin "1") (pinfunction "1_1") (pintype "passive"))
    )
    (net (code "199") (name "unconnected-(JP448-Pad1)") (class "Default")
      (node (ref "JP448") (pin "1") (pinfunction "1_1") (pintype "passive"))
    )
    (net (code "200") (name "unconnected-(JP449-Pad1)") (class "Default")
      (node (ref "JP449") (pin "1") (pinfunction "1_1") (pintype "passive"))
    )
    (net (code "201") (name "unconnected-(JP450-Pad1)") (class "Default")
      (node (ref "JP450") (pin "1") (pinfunction "1_1") (pintype "passive"))
    )
    (net (code "202") (name "unconnected-(JP451-Pad1)") (class "Default")
      (node (ref "JP451") (pin "1") (pinfunction "1_1") (pintype "passive"))
    )
    (net (code "203") (name "unconnected-(JP452-Pad1)") (class "Default")
      (node (ref "JP452") (pin "1") (pinfunction "1_1") (pintype "passive"))
    )
    (net (code "204") (name "unconnected-(JP453-Pad1)") (class "Default")
      (node (ref "JP453") (pin "1") (pinfunction "1_1") (pintype "passive"))
    )
    (net (code "205") (name "unconnected-(JP454-Pad1)") (class "Default")
      (node (ref "JP454") (pin "1") (pinfunction "1_1") (pintype "passive"))
    )
    (net (code "206") (name "unconnected-(JP455-Pad1)") (class "Default")
      (node (ref "JP455") (pin "1") (pinfunction "1_1") (pintype "passive"))
    )
    (net (code "207") (name "unconnected-(JP456-Pad1)") (class "Default")
      (node (ref "JP456") (pin "1") (pinfunction "1_1") (pintype "passive"))
    )
    (net (code "208") (name "unconnected-(JP457-Pad1)") (class "Default")
      (node (ref "JP457") (pin "1") (pinfunction "1_1") (pintype "passive"))
    )
    (net (code "209") (name "unconnected-(JP458-Pad1)") (class "Default")
      (node (ref "JP458") (pin "1") (pinfunction "1_1") (pintype "passive"))
    )
    (net (code "210") (name "unconnected-(JP459-Pad1)") (class "Default")
      (node (ref "JP459") (pin "1") (pinfunction "1_1") (pintype "passive"))
    )
    (net (code "211") (name "unconnected-(JP460-Pad1)") (class "Default")
      (node (ref "JP460") (pin "1") (pinfunction "1_1") (pintype "passive"))
    )
    (net (code "212") (name "unconnected-(JP461-Pad1)") (class "Default")
      (node (ref "JP461") (pin "1") (pinfunction "1_1") (pintype "passive"))
    )
    (net (code "213") (name "unconnected-(JP462-Pad1)") (class "Default")
      (node (ref "JP462") (pin "1") (pinfunction "1_1") (pintype "passive"))
    )
    (net (code "214") (name "unconnected-(JP463-Pad1)") (class "Default")
      (node (ref "JP463") (pin "1") (pinfunction "1_1") (pintype "passive"))
    )
    (net (code "215") (name "unconnected-(JP464-Pad1)") (class "Default")
      (node (ref "JP464") (pin "1") (pinfunction "1_1") (pintype "passive"))
    )
    (net (code "216") (name "unconnected-(JP465-Pad1)") (class "Default")
      (node (ref "JP465") (pin "1") (pinfunction "1_1") (pintype "passive"))
    )
    (net (code "217") (name "unconnected-(JP466-Pad1)") (class "Default")
      (node (ref "JP466") (pin "1") (pinfunction "1_1") (pintype "passive"))
    )
    (net (code "218") (name "unconnected-(JP467-Pad1)") (class "Default")
      (node (ref "JP467") (pin "1") (pinfunction "1_1") (pintype "passive"))
    )
    (net (code "219") (name "unconnected-(JP468-Pad1)") (class "Default")
      (node (ref "JP468") (pin "1") (pinfunction "1_1") (pintype "passive"))
    )
    (net (code "220") (name "unconnected-(JP469-Pad1)") (class "Default")
      (node (ref "JP469") (pin "1") (pinfunction "1_1") (pintype "passive"))
    )
    (net (code "221") (name "unconnected-(JP470-Pad1)") (class "Default")
      (node (ref "JP470") (pin "1") (pinfunction "1_1") (pintype "passive"))
    )
    (net (code "222") (name "unconnected-(JP471-Pad1)") (class "Default")
      (node (ref "JP471") (pin "1") (pinfunction "1_1") (pintype "passive"))
    )
    (net (code "223") (name "unconnected-(JP472-Pad1)") (class "Default")
      (node (ref "JP472") (pin "1") (pinfunction "1_1") (pintype "passive"))
    )
    (net (code "224") (name "unconnected-(JP473-Pad1)") (class "Default")
      (node (ref "JP473") (pin "1") (pinfunction "1_1") (pintype "passive"))
    )
    (net (code "225") (name "unconnected-(JP474-Pad1)") (class "Default")
      (node (ref "JP474") (pin "1") (pinfunction "1_1") (pintype "passive"))
    )
    (net (code "226") (name "unconnected-(JP475-Pad1)") (class "Default")
      (node (ref "JP475") (pin "1") (pinfunction "1_1") (pintype "passive"))
    )
    (net (code "227") (name "unconnected-(JP476-Pad1)") (class "Default")
      (node (ref "JP476") (pin "1") (pinfunction "1_1") (pintype "passive"))
    )
    (net (code "228") (name "unconnected-(JP477-Pad1)") (class "Default")
      (node (ref "JP477") (pin "1") (pinfunction "1_1") (pintype "passive"))
    )
    (net (code "229") (name "unconnected-(JP478-Pad1)") (class "Default")
      (node (ref "JP478") (pin "1") (pinfunction "1_1") (pintype "passive"))
    )
    (net (code "230") (name "unconnected-(JP479-Pad1)") (class "Default")
      (node (ref "JP479") (pin "1") (pinfunction "1_1") (pintype "passive"))
    )
    (net (code "231") (name "unconnected-(JP480-Pad1)") (class "Default")
      (node (ref "JP480") (pin "1") (pinfunction "1_1") (pintype "passive"))
    )
    (net (code "232") (name "unconnected-(JP481-Pad1)") (class "Default")
      (node (ref "JP481") (pin "1") (pinfunction "1_1") (pintype "passive"))
    )
    (net (code "233") (name "unconnected-(JP482-Pad1)") (class "Default")
      (node (ref "JP482") (pin "1") (pinfunction "1_1") (pintype "passive"))
    )
    (net (code "234") (name "unconnected-(JP483-Pad1)") (class "Default")
      (node (ref "JP483") (pin "1") (pinfunction "1_1") (pintype "passive"))
    )
    (net (code "235") (name "unconnected-(JP484-Pad1)") (class "Default")
      (node (ref "JP484") (pin "1") (pinfunction "1_1") (pintype "passive"))
    )
    (net (code "236") (name "unconnected-(JP485-Pad1)") (class "Default")
      (node (ref "JP485") (pin "1") (pinfunction "1_1") (pintype "passive"))
    )
    (net (code "237") (name "unconnected-(JP486-Pad1)") (class "Default")
      (node (ref "JP486") (pin "1") (pinfunction "1_1") (pintype "passive"))
    )
    (net (code "238") (name "unconnected-(JP487-Pad1)") (class "Default")
      (node (ref "JP487") (pin "1") (pinfunction "1_1") (pintype "passive"))
    )
    (net (code "239") (name "unconnected-(JP488-Pad1)") (class "Default")
      (node (ref "JP488") (pin "1") (pinfunction "1_1") (pintype "passive"))
    )
    (net (code "240") (name "unconnected-(JP489-Pad1)") (class "Default")
      (node (ref "JP489") (pin "1") (pinfunction "1_1") (pintype "passive"))
    )
    (net (code "241") (name "unconnected-(JP490-Pad1)") (class "Default")
      (node (ref "JP490") (pin "1") (pinfunction "1_1") (pintype "passive"))
    )
    (net (code "242") (name "unconnected-(JP491-Pad1)") (class "Default")
      (node (ref "JP491") (pin "1") (pinfunction "1_1") (pintype "passive"))
    )
    (net (code "243") (name "unconnected-(JP492-Pad1)") (class "Default")
      (node (ref "JP492") (pin "1") (pinfunction "1_1") (pintype "passive"))
    )
    (net (code "244") (name "unconnected-(JP493-Pad1)") (class "Default")
      (node (ref "JP493") (pin "1") (pinfunction "1_1") (pintype "passive"))
    )
    (net (code "245") (name "unconnected-(JP494-Pad1)") (class "Default")
      (node (ref "JP494") (pin "1") (pinfunction "1_1") (pintype "passive"))
    )
    (net (code "246") (name "unconnected-(JP495-Pad1)") (class "Default")
      (node (ref "JP495") (pin "1") (pinfunction "1_1") (pintype "passive"))
    )
    (net (code "247") (name "unconnected-(JP496-Pad1)") (class "Default")
      (node (ref "JP496") (pin "1") (pinfunction "1_1") (pintype "passive"))
    )
    (net (code "248") (name "unconnected-(JP497-Pad1)") (class "Default")
      (node (ref "JP497") (pin "1") (pinfunction "1_1") (pintype "passive"))
    )
    (net (code "249") (name "unconnected-(JP498-Pad1)") (class "Default")
      (node (ref "JP498") (pin "1") (pinfunction "1_1") (pintype "passive"))
    )
    (net (code "250") (name "unconnected-(JP499-Pad1)") (class "Default")
      (node (ref "JP499") (pin "1") (pinfunction "1_1") (pintype "passive"))
    )
    (net (code "251") (name "unconnected-(JP500-Pad1)") (class "Default")
      (node (ref "JP500") (pin "1") (pinfunction "1_1") (pintype "passive"))
    )
    (net (code "252") (name "unconnected-(JP501-Pad1)") (class "Default")
      (node (ref "JP501") (pin "1") (pinfunction "1_1") (pintype "passive"))
    )
    (net (code "253") (name "unconnected-(JP502-Pad1)") (class "Default")
      (node (ref "JP502") (pin "1") (pinfunction "1_1") (pintype "passive"))
    )
    (net (code "254") (name "unconnected-(JP503-Pad1)") (class "Default")
      (node (ref "JP503") (pin "1") (pinfunction "1_1") (pintype "passive"))
    )
    (net (code "255") (name "unconnected-(JP504-Pad1)") (class "Default")
      (node (ref "JP504") (pin "1") (pinfunction "1_1") (pintype "passive"))
    )
    (net (code "256") (name "unconnected-(JP505-Pad1)") (class "Default")
      (node (ref "JP505") (pin "1") (pinfunction "1_1") (pintype "passive"))
    )
    (net (code "257") (name "unconnected-(JP506-Pad1)") (class "Default")
      (node (ref "JP506") (pin "1") (pinfunction "1_1") (pintype "passive"))
    )
    (net (code "258") (name "unconnected-(JP507-Pad1)") (class "Default")
      (node (ref "JP507") (pin "1") (pinfunction "1_1") (pintype "passive"))
    )
    (net (code "259") (name "unconnected-(JP508-Pad1)") (class "Default")
      (node (ref "JP508") (pin "1") (pinfunction "1_1") (pintype "passive"))
    )
    (net (code "260") (name "unconnected-(JP509-Pad1)") (class "Default")
      (node (ref "JP509") (pin "1") (pinfunction "1_1") (pintype "passive"))
    )
    (net (code "261") (name "unconnected-(JP510-Pad1)") (class "Default")
      (node (ref "JP510") (pin "1") (pinfunction "1_1") (pintype "passive"))
    )
    (net (code "262") (name "unconnected-(JP511-Pad1)") (class "Default")
      (node (ref "JP511") (pin "1") (pinfunction "1_1") (pintype "passive"))
    )
    (net (code "263") (name "unconnected-(JP512-Pad1)") (class "Default")
      (node (ref "JP512") (pin "1") (pinfunction "1_1") (pintype "passive"))
    )
    (net (code "264") (name "unconnected-(JP513-Pad1)") (class "Default")
      (node (ref "JP513") (pin "1") (pinfunction "1_1") (pintype "passive"))
    )
    (net (code "265") (name "unconnected-(JP514-Pad1)") (class "Default")
      (node (ref "JP514") (pin "1") (pinfunction "1_1") (pintype "passive"))
    )
    (net (code "266") (name "unconnected-(JP515-Pad1)") (class "Default")
      (node (ref "JP515") (pin "1") (pinfunction "1_1") (pintype "passive"))
    )
    (net (code "267") (name "unconnected-(JP516-Pad1)") (class "Default")
      (node (ref "JP516") (pin "1") (pinfunction "1_1") (pintype "passive"))
    )
    (net (code "268") (name "unconnected-(JP517-Pad1)") (class "Default")
      (node (ref "JP517") (pin "1") (pinfunction "1_1") (pintype "passive"))
    )
    (net (code "269") (name "unconnected-(JP518-Pad1)") (class "Default")
      (node (ref "JP518") (pin "1") (pinfunction "1_1") (pintype "passive"))
    )
    (net (code "270") (name "unconnected-(JP519-Pad1)") (class "Default")
      (node (ref "JP519") (pin "1") (pinfunction "1_1") (pintype "passive"))
    )
    (net (code "271") (name "unconnected-(JP520-Pad1)") (class "Default")
      (node (ref "JP520") (pin "1") (pinfunction "1_1") (pintype "passive"))
    )
    (net (code "272") (name "unconnected-(JP521-Pad1)") (class "Default")
      (node (ref "JP521") (pin "1") (pinfunction "1_1") (pintype "passive"))
    )
    (net (code "273") (name "unconnected-(JP522-Pad1)") (class "Default")
      (node (ref "JP522") (pin "1") (pinfunction "1_1") (pintype "passive"))
    )
    (net (code "274") (name "unconnected-(JP523-Pad1)") (class "Default")
      (node (ref "JP523") (pin "1") (pinfunction "1_1") (pintype "passive"))
    )
    (net (code "275") (name "unconnected-(JP524-Pad1)") (class "Default")
      (node (ref "JP524") (pin "1") (pinfunction "1_1") (pintype "passive"))
    )
    (net (code "276") (name "unconnected-(JP525-Pad1)") (class "Default")
      (node (ref "JP525") (pin "1") (pinfunction "1_1") (pintype "passive"))
    )
    (net (code "277") (name "unconnected-(JP526-Pad1)") (class "Default")
      (node (ref "JP526") (pin "1") (pinfunction "1_1") (pintype "passive"))
    )
    (net (code "278") (name "unconnected-(JP527-Pad1)") (class "Default")
      (node (ref "JP527") (pin "1") (pinfunction "1_1") (pintype "passive"))
    )
    (net (code "279") (name "unconnected-(JP528-Pad1)") (class "Default")
      (node (ref "JP528") (pin "1") (pinfunction "1_1") (pintype "passive"))
    )
    (net (code "280") (name "unconnected-(JP529-Pad1)") (class "Default")
      (node (ref "JP529") (pin "1") (pinfunction "1_1") (pintype "passive"))
    )
    (net (code "281") (name "unconnected-(JP530-Pad1)") (class "Default")
      (node (ref "JP530") (pin "1") (pinfunction "1_1") (pintype "passive"))
    )
    (net (code "282") (name "unconnected-(JP531-Pad1)") (class "Default")
      (node (ref "JP531") (pin "1") (pinfunction "1_1") (pintype "passive"))
    )
    (net (code "283") (name "unconnected-(JP532-Pad1)") (class "Default")
      (node (ref "JP532") (pin "1") (pinfunction "1_1") (pintype "passive"))
    )
    (net (code "284") (name "unconnected-(JP533-Pad1)") (class "Default")
      (node (ref "JP533") (pin "1") (pinfunction "1_1") (pintype "passive"))
    )
    (net (code "285") (name "unconnected-(JP534-Pad1)") (class "Default")
      (node (ref "JP534") (pin "1") (pinfunction "1_1") (pintype "passive"))
    )
    (net (code "286") (name "unconnected-(JP535-Pad1)") (class "Default")
      (node (ref "JP535") (pin "1") (pinfunction "1_1") (pintype "passive"))
    )
    (net (code "287") (name "unconnected-(JP536-Pad1)") (class "Default")
      (node (ref "JP536") (pin "1") (pinfunction "1_1") (pintype "passive"))
    )
    (net (code "288") (name "unconnected-(JP537-Pad1)") (class "Default")
      (node (ref "JP537") (pin "1") (pinfunction "1_1") (pintype "passive"))
    )
    (net (code "289") (name "unconnected-(JP538-Pad1)") (class "Default")
      (node (ref "JP538") (pin "1") (pinfunction "1_1") (pintype "passive"))
    )
    (net (code "290") (name "unconnected-(JP539-Pad1)") (class "Default")
      (node (ref "JP539") (pin "1") (pinfunction "1_1") (pintype "passive"))
    )
    (net (code "291") (name "unconnected-(JP540-Pad1)") (class "Default")
      (node (ref "JP540") (pin "1") (pinfunction "1_1") (pintype "passive"))
    )
    (net (code "292") (name "unconnected-(JP541-Pad1)") (class "Default")
      (node (ref "JP541") (pin "1") (pinfunction "1_1") (pintype "passive"))
    )
    (net (code "293") (name "unconnected-(JP542-Pad1)") (class "Default")
      (node (ref "JP542") (pin "1") (pinfunction "1_1") (pintype "passive"))
    )
    (net (code "294") (name "unconnected-(JP543-Pad1)") (class "Default")
      (node (ref "JP543") (pin "1") (pinfunction "1_1") (pintype "passive"))
    )
    (net (code "295") (name "unconnected-(JP544-Pad1)") (class "Default")
      (node (ref "JP544") (pin "1") (pinfunction "1_1") (pintype "passive"))
    )
    (net (code "296") (name "unconnected-(JP545-Pad1)") (class "Default")
      (node (ref "JP545") (pin "1") (pinfunction "1_1") (pintype "passive"))
    )
    (net (code "297") (name "unconnected-(JP546-Pad1)") (class "Default")
      (node (ref "JP546") (pin "1") (pinfunction "1_1") (pintype "passive"))
    )
    (net (code "298") (name "unconnected-(JP547-Pad1)") (class "Default")
      (node (ref "JP547") (pin "1") (pinfunction "1_1") (pintype "passive"))
    )
    (net (code "299") (name "unconnected-(JP548-Pad1)") (class "Default")
      (node (ref "JP548") (pin "1") (pinfunction "1_1") (pintype "passive"))
    )
    (net (code "300") (name "unconnected-(JP549-Pad1)") (class "Default")
      (node (ref "JP549") (pin "1") (pinfunction "1_1") (pintype "passive"))
    )
    (net (code "301") (name "unconnected-(JP550-Pad1)") (class "Default")
      (node (ref "JP550") (pin "1") (pinfunction "1_1") (pintype "passive"))
    )
    (net (code "302") (name "unconnected-(JP551-Pad1)") (class "Default")
      (node (ref "JP551") (pin "1") (pinfunction "1_1") (pintype "passive"))
    )
    (net (code "303") (name "unconnected-(JP552-Pad1)") (class "Default")
      (node (ref "JP552") (pin "1") (pinfunction "1_1") (pintype "passive"))
    )
    (net (code "304") (name "unconnected-(JP553-Pad1)") (class "Default")
      (node (ref "JP553") (pin "1") (pinfunction "1_1") (pintype "passive"))
    )
    (net (code "305") (name "unconnected-(JP554-Pad1)") (class "Default")
      (node (ref "JP554") (pin "1") (pinfunction "1_1") (pintype "passive"))
    )
    (net (code "306") (name "unconnected-(JP555-Pad1)") (class "Default")
      (node (ref "JP555") (pin "1") (pinfunction "1_1") (pintype "passive"))
    )
    (net (code "307") (name "unconnected-(JP556-Pad1)") (class "Default")
      (node (ref "JP556") (pin "1") (pinfunction "1_1") (pintype "passive"))
    )
    (net (code "308") (name "unconnected-(JP557-Pad1)") (class "Default")
      (node (ref "JP557") (pin "1") (pinfunction "1_1") (pintype "passive"))
    )
    (net (code "309") (name "unconnected-(JP558-Pad1)") (class "Default")
      (node (ref "JP558") (pin "1") (pinfunction "1_1") (pintype "passive"))
    )
    (net (code "310") (name "unconnected-(JP559-Pad1)") (class "Default")
      (node (ref "JP559") (pin "1") (pinfunction "1_1") (pintype "passive"))
    )
    (net (code "311") (name "unconnected-(JP560-Pad1)") (class "Default")
      (node (ref "JP560") (pin "1") (pinfunction "1_1") (pintype "passive"))
    )
    (net (code "312") (name "unconnected-(JP561-Pad1)") (class "Default")
      (node (ref "JP561") (pin "1") (pinfunction "1_1") (pintype "passive"))
    )
    (net (code "313") (name "unconnected-(JP562-Pad1)") (class "Default")
      (node (ref "JP562") (pin "1") (pinfunction "1_1") (pintype "passive"))
    )
    (net (code "314") (name "unconnected-(JP563-Pad1)") (class "Default")
      (node (ref "JP563") (pin "1") (pinfunction "1_1") (pintype "passive"))
    )
    (net (code "315") (name "unconnected-(JP564-Pad1)") (class "Default")
      (node (ref "JP564") (pin "1") (pinfunction "1_1") (pintype "passive"))
    )
    (net (code "316") (name "unconnected-(JP565-Pad1)") (class "Default")
      (node (ref "JP565") (pin "1") (pinfunction "1_1") (pintype "passive"))
    )
    (net (code "317") (name "unconnected-(JP566-Pad1)") (class "Default")
      (node (ref "JP566") (pin "1") (pinfunction "1_1") (pintype "passive"))
    )
    (net (code "318") (name "unconnected-(JP567-Pad1)") (class "Default")
      (node (ref "JP567") (pin "1") (pinfunction "1_1") (pintype "passive"))
    )
    (net (code "319") (name "unconnected-(JP568-Pad1)") (class "Default")
      (node (ref "JP568") (pin "1") (pinfunction "1_1") (pintype "passive"))
    )
    (net (code "320") (name "unconnected-(JP569-Pad1)") (class "Default")
      (node (ref "JP569") (pin "1") (pinfunction "1_1") (pintype "passive"))
    )
    (net (code "321") (name "unconnected-(JP570-Pad1)") (class "Default")
      (node (ref "JP570") (pin "1") (pinfunction "1_1") (pintype "passive"))
    )
    (net (code "322") (name "unconnected-(JP571-Pad1)") (class "Default")
      (node (ref "JP571") (pin "1") (pinfunction "1_1") (pintype "passive"))
    )
    (net (code "323") (name "unconnected-(JP572-Pad1)") (class "Default")
      (node (ref "JP572") (pin "1") (pinfunction "1_1") (pintype "passive"))
    )
    (net (code "324") (name "unconnected-(JP573-Pad1)") (class "Default")
      (node (ref "JP573") (pin "1") (pinfunction "1_1") (pintype "passive"))
    )
    (net (code "325") (name "unconnected-(JP574-Pad1)") (class "Default")
      (node (ref "JP574") (pin "1") (pinfunction "1_1") (pintype "passive"))
    )
    (net (code "326") (name "unconnected-(JP575-Pad1)") (class "Default")
      (node (ref "JP575") (pin "1") (pinfunction "1_1") (pintype "passive"))
    )
    (net (code "327") (name "unconnected-(JP576-Pad1)") (class "Default")
      (node (ref "JP576") (pin "1") (pinfunction "1_1") (pintype "passive"))
    )
    (net (code "328") (name "unconnected-(JP577-Pad1)") (class "Default")
      (node (ref "JP577") (pin "1") (pinfunction "1_1") (pintype "passive"))
    )
    (net (code "329") (name "unconnected-(JP578-Pad1)") (class "Default")
      (node (ref "JP578") (pin "1") (pinfunction "1_1") (pintype "passive"))
    )
    (net (code "330") (name "unconnected-(JP579-Pad1)") (class "Default")
      (node (ref "JP579") (pin "1") (pinfunction "1_1") (pintype "passive"))
    )
    (net (code "331") (name "unconnected-(JP580-Pad1)") (class "Default")
      (node (ref "JP580") (pin "1") (pinfunction "1_1") (pintype "passive"))
    )
    (net (code "332") (name "unconnected-(JP581-Pad1)") (class "Default")
      (node (ref "JP581") (pin "1") (pinfunction "1_1") (pintype "passive"))
    )
    (net (code "333") (name "unconnected-(JP582-Pad1)") (class "Default")
      (node (ref "JP582") (pin "1") (pinfunction "1_1") (pintype "passive"))
    )
    (net (code "334") (name "unconnected-(JP583-Pad1)") (class "Default")
      (node (ref "JP583") (pin "1") (pinfunction "1_1") (pintype "passive"))
    )
    (net (code "335") (name "unconnected-(JP584-Pad1)") (class "Default")
      (node (ref "JP584") (pin "1") (pinfunction "1_1") (pintype "passive"))
    )
    (net (code "336") (name "unconnected-(JP585-Pad1)") (class "Default")
      (node (ref "JP585") (pin "1") (pinfunction "1_1") (pintype "passive"))
    )
    (net (code "337") (name "unconnected-(JP586-Pad1)") (class "Default")
      (node (ref "JP586") (pin "1") (pinfunction "1_1") (pintype "passive"))
    )
    (net (code "338") (name "unconnected-(JP587-Pad1)") (class "Default")
      (node (ref "JP587") (pin "1") (pinfunction "1_1") (pintype "passive"))
    )
    (net (code "339") (name "unconnected-(JP588-Pad1)") (class "Default")
      (node (ref "JP588") (pin "1") (pinfunction "1_1") (pintype "passive"))
    )
    (net (code "340") (name "unconnected-(JP589-Pad1)") (class "Default")
      (node (ref "JP589") (pin "1") (pinfunction "1_1") (pintype "passive"))
    )
    (net (code "341") (name "unconnected-(JP590-Pad1)") (class "Default")
      (node (ref "JP590") (pin "1") (pinfunction "1_1") (pintype "passive"))
    )
    (net (code "342") (name "unconnected-(JP591-Pad1)") (class "Default")
      (node (ref "JP591") (pin "1") (pinfunction "1_1") (pintype "passive"))
    )
    (net (code "343") (name "unconnected-(JP592-Pad1)") (class "Default")
      (node (ref "JP592") (pin "1") (pinfunction "1_1") (pintype "passive"))
    )
    (net (code "344") (name "unconnected-(JP593-Pad1)") (class "Default")
      (node (ref "JP593") (pin "1") (pinfunction "1_1") (pintype "passive"))
    )
    (net (code "345") (name "unconnected-(JP594-Pad1)") (class "Default")
      (node (ref "JP594") (pin "1") (pinfunction "1_1") (pintype "passive"))
    )
    (net (code "346") (name "unconnected-(JP595-Pad1)") (class "Default")
      (node (ref "JP595") (pin "1") (pinfunction "1_1") (pintype "passive"))
    )
    (net (code "347") (name "unconnected-(JP596-Pad1)") (class "Default")
      (node (ref "JP596") (pin "1") (pinfunction "1_1") (pintype "passive"))
    )
    (net (code "348") (name "unconnected-(JP597-Pad1)") (class "Default")
      (node (ref "JP597") (pin "1") (pinfunction "1_1") (pintype "passive"))
    )
    (net (code "349") (name "unconnected-(JP598-Pad1)") (class "Default")
      (node (ref "JP598") (pin "1") (pinfunction "1_1") (pintype "passive"))
    )
    (net (code "350") (name "unconnected-(JP599-Pad1)") (class "Default")
      (node (ref "JP599") (pin "1") (pinfunction "1_1") (pintype "passive"))
    )
    (net (code "351") (name "unconnected-(JP600-Pad1)") (class "Default")
      (node (ref "JP600") (pin "1") (pinfunction "1_1") (pintype "passive"))
    )
    (net (code "352") (name "unconnected-(JP601-Pad1)") (class "Default")
      (node (ref "JP601") (pin "1") (pinfunction "1_1") (pintype "passive"))
    )
    (net (code "353") (name "unconnected-(JP602-Pad1)") (class "Default")
      (node (ref "JP602") (pin "1") (pinfunction "1_1") (pintype "passive"))
    )
    (net (code "354") (name "unconnected-(JP603-Pad1)") (class "Default")
      (node (ref "JP603") (pin "1") (pinfunction "1_1") (pintype "passive"))
    )
    (net (code "355") (name "unconnected-(JP604-Pad1)") (class "Default")
      (node (ref "JP604") (pin "1") (pinfunction "1_1") (pintype "passive"))
    )
    (net (code "356") (name "unconnected-(JP605-Pad1)") (class "Default")
      (node (ref "JP605") (pin "1") (pinfunction "1_1") (pintype "passive"))
    )
    (net (code "357") (name "unconnected-(JP606-Pad1)") (class "Default")
      (node (ref "JP606") (pin "1") (pinfunction "1_1") (pintype "passive"))
    )
    (net (code "358") (name "unconnected-(JP607-Pad1)") (class "Default")
      (node (ref "JP607") (pin "1") (pinfunction "1_1") (pintype "passive"))
    )
    (net (code "359") (name "unconnected-(JP608-Pad1)") (class "Default")
      (node (ref "JP608") (pin "1") (pinfunction "1_1") (pintype "passive"))
    )
    (net (code "360") (name "unconnected-(JP609-Pad1)") (class "Default")
      (node (ref "JP609") (pin "1") (pinfunction "1_1") (pintype "passive"))
    )
    (net (code "361") (name "unconnected-(JP610-Pad1)") (class "Default")
      (node (ref "JP610") (pin "1") (pinfunction "1_1") (pintype "passive"))
    )
    (net (code "362") (name "unconnected-(JP611-Pad1)") (class "Default")
      (node (ref "JP611") (pin "1") (pinfunction "1_1") (pintype "passive"))
    )
    (net (code "363") (name "unconnected-(JP612-Pad1)") (class "Default")
      (node (ref "JP612") (pin "1") (pinfunction "1_1") (pintype "passive"))
    )
    (net (code "364") (name "unconnected-(JP613-Pad1)") (class "Default")
      (node (ref "JP613") (pin "1") (pinfunction "1_1") (pintype "passive"))
    )
    (net (code "365") (name "unconnected-(JP614-Pad1)") (class "Default")
      (node (ref "JP614") (pin "1") (pinfunction "1_1") (pintype "passive"))
    )
    (net (code "366") (name "unconnected-(JP615-Pad1)") (class "Default")
      (node (ref "JP615") (pin "1") (pinfunction "1_1") (pintype "passive"))
    )
    (net (code "367") (name "unconnected-(JP616-Pad1)") (class "Default")
      (node (ref "JP616") (pin "1") (pinfunction "1_1") (pintype "passive"))
    )
    (net (code "368") (name "unconnected-(JP617-Pad1)") (class "Default")
      (node (ref "JP617") (pin "1") (pinfunction "1_1") (pintype "passive"))
    )
    (net (code "369") (name "unconnected-(JP618-Pad1)") (class "Default")
      (node (ref "JP618") (pin "1") (pinfunction "1_1") (pintype "passive"))
    )
    (net (code "370") (name "unconnected-(JP619-Pad1)") (class "Default")
      (node (ref "JP619") (pin "1") (pinfunction "1_1") (pintype "passive"))
    )
    (net (code "371") (name "unconnected-(JP620-Pad1)") (class "Default")
      (node (ref "JP620") (pin "1") (pinfunction "1_1") (pintype "passive"))
    )
    (net (code "372") (name "unconnected-(JP621-Pad1)") (class "Default")
      (node (ref "JP621") (pin "1") (pinfunction "1_1") (pintype "passive"))
    )
    (net (code "373") (name "unconnected-(JP622-Pad1)") (class "Default")
      (node (ref "JP622") (pin "1") (pinfunction "1_1") (pintype "passive"))
    )
    (net (code "374") (name "unconnected-(JP623-Pad1)") (class "Default")
      (node (ref "JP623") (pin "1") (pinfunction "1_1") (pintype "passive"))
    )
    (net (code "375") (name "unconnected-(JP624-Pad1)") (class "Default")
      (node (ref "JP624") (pin "1") (pinfunction "1_1") (pintype "passive"))
    )
    (net (code "376") (name "unconnected-(JP625-Pad1)") (class "Default")
      (node (ref "JP625") (pin "1") (pinfunction "1_1") (pintype "passive"))
    )
    (net (code "377") (name "unconnected-(JP626-Pad1)") (class "Default")
      (node (ref "JP626") (pin "1") (pinfunction "1_1") (pintype "passive"))
    )
    (net (code "378") (name "unconnected-(JP627-Pad1)") (class "Default")
      (node (ref "JP627") (pin "1") (pinfunction "1_1") (pintype "passive"))
    )
    (net (code "379") (name "unconnected-(JP628-Pad1)") (class "Default")
      (node (ref "JP628") (pin "1") (pinfunction "1_1") (pintype "passive"))
    )
    (net (code "380") (name "unconnected-(JP629-Pad1)") (class "Default")
      (node (ref "JP629") (pin "1") (pinfunction "1_1") (pintype "passive"))
    )
    (net (code "381") (name "unconnected-(JP630-Pad1)") (class "Default")
      (node (ref "JP630") (pin "1") (pinfunction "1_1") (pintype "passive"))
    )
    (net (code "382") (name "unconnected-(JP631-Pad1)") (class "Default")
      (node (ref "JP631") (pin "1") (pinfunction "1_1") (pintype "passive"))
    )
    (net (code "383") (name "unconnected-(JP632-Pad1)") (class "Default")
      (node (ref "JP632") (pin "1") (pinfunction "1_1") (pintype "passive"))
    )
    (net (code "384") (name "unconnected-(JP633-Pad1)") (class "Default")
      (node (ref "JP633") (pin "1") (pinfunction "1_1") (pintype "passive"))
    )
    (net (code "385") (name "unconnected-(JP634-Pad1)") (class "Default")
      (node (ref "JP634") (pin "1") (pinfunction "1_1") (pintype "passive"))
    )
    (net (code "386") (name "unconnected-(JP635-Pad1)") (class "Default")
      (node (ref "JP635") (pin "1") (pinfunction "1_1") (pintype "passive"))
    )
    (net (code "387") (name "unconnected-(JP636-Pad1)") (class "Default")
      (node (ref "JP636") (pin "1") (pinfunction "1_1") (pintype "passive"))
    )
    (net (code "388") (name "unconnected-(JP637-Pad1)") (class "Default")
      (node (ref "JP637") (pin "1") (pinfunction "1_1") (pintype "passive"))
    )
    (net (code "389") (name "unconnected-(JP638-Pad1)") (class "Default")
      (node (ref "JP638") (pin "1") (pinfunction "1_1") (pintype "passive"))
    )
    (net (code "390") (name "unconnected-(JP639-Pad1)") (class "Default")
      (node (ref "JP639") (pin "1") (pinfunction "1_1") (pintype "passive"))
    )
    (net (code "391") (name "unconnected-(JP640-Pad1)") (class "Default")
      (node (ref "JP640") (pin "1") (pinfunction "1_1") (pintype "passive"))
    )
    (net (code "392") (name "unconnected-(JP641-Pad1)") (class "Default")
      (node (ref "JP641") (pin "1") (pinfunction "1_1") (pintype "passive"))
    )
    (net (code "393") (name "unconnected-(JP642-Pad1)") (class "Default")
      (node (ref "JP642") (pin "1") (pinfunction "1_1") (pintype "passive"))
    )
    (net (code "394") (name "unconnected-(JP643-Pad1)") (class "Default")
      (node (ref "JP643") (pin "1") (pinfunction "1_1") (pintype "passive"))
    )
    (net (code "395") (name "unconnected-(JP644-Pad1)") (class "Default")
      (node (ref "JP644") (pin "1") (pinfunction "1_1") (pintype "passive"))
    )
    (net (code "396") (name "unconnected-(JP645-Pad1)") (class "Default")
      (node (ref "JP645") (pin "1") (pinfunction "1_1") (pintype "passive"))
    )
    (net (code "397") (name "unconnected-(JP646-Pad1)") (class "Default")
      (node (ref "JP646") (pin "1") (pinfunction "1_1") (pintype "passive"))
    )
    (net (code "398") (name "unconnected-(JP647-Pad1)") (class "Default")
      (node (ref "JP647") (pin "1") (pinfunction "1_1") (pintype "passive"))
    )
    (net (code "399") (name "unconnected-(JP648-Pad1)") (class "Default")
      (node (ref "JP648") (pin "1") (pinfunction "1_1") (pintype "passive"))
    )
    (net (code "400") (name "unconnected-(JP649-Pad1)") (class "Default")
      (node (ref "JP649") (pin "1") (pinfunction "1_1") (pintype "passive"))
    )
    (net (code "401") (name "unconnected-(JP650-Pad1)") (class "Default")
      (node (ref "JP650") (pin "1") (pinfunction "1_1") (pintype "passive"))
    )
    (net (code "402") (name "unconnected-(JP651-Pad1)") (class "Default")
      (node (ref "JP651") (pin "1") (pinfunction "1_1") (pintype "passive"))
    )
    (net (code "403") (name "unconnected-(JP652-Pad1)") (class "Default")
      (node (ref "JP652") (pin "1") (pinfunction "1_1") (pintype "passive"))
    )
    (net (code "404") (name "unconnected-(JP653-Pad1)") (class "Default")
      (node (ref "JP653") (pin "1") (pinfunction "1_1") (pintype "passive"))
    )
    (net (code "405") (name "unconnected-(JP654-Pad1)") (class "Default")
      (node (ref "JP654") (pin "1") (pinfunction "1_1") (pintype "passive"))
    )
    (net (code "406") (name "unconnected-(JP655-Pad1)") (class "Default")
      (node (ref "JP655") (pin "1") (pinfunction "1_1") (pintype "passive"))
    )
    (net (code "407") (name "unconnected-(JP656-Pad1)") (class "Default")
      (node (ref "JP656") (pin "1") (pinfunction "1_1") (pintype "passive"))
    )
    (net (code "408") (name "unconnected-(JP657-Pad1)") (class "Default")
      (node (ref "JP657") (pin "1") (pinfunction "1_1") (pintype "passive"))
    )
    (net (code "409") (name "unconnected-(JP658-Pad1)") (class "Default")
      (node (ref "JP658") (pin "1") (pinfunction "1_1") (pintype "passive"))
    )
    (net (code "410") (name "unconnected-(JP659-Pad1)") (class "Default")
      (node (ref "JP659") (pin "1") (pinfunction "1_1") (pintype "passive"))
    )
    (net (code "411") (name "unconnected-(JP660-Pad1)") (class "Default")
      (node (ref "JP660") (pin "1") (pinfunction "1_1") (pintype "passive"))
    )
    (net (code "412") (name "unconnected-(JP661-Pad1)") (class "Default")
      (node (ref "JP661") (pin "1") (pinfunction "1_1") (pintype "passive"))
    )
    (net (code "413") (name "unconnected-(JP662-Pad1)") (class "Default")
      (node (ref "JP662") (pin "1") (pinfunction "1_1") (pintype "passive"))
    )
    (net (code "414") (name "unconnected-(JP663-Pad1)") (class "Default")
      (node (ref "JP663") (pin "1") (pinfunction "1_1") (pintype "passive"))
    )
    (net (code "415") (name "unconnected-(JP664-Pad1)") (class "Default")
      (node (ref "JP664") (pin "1") (pinfunction "1_1") (pintype "passive"))
    )
    (net (code "416") (name "unconnected-(JP665-Pad1)") (class "Default")
      (node (ref "JP665") (pin "1") (pinfunction "1_1") (pintype "passive"))
    )
    (net (code "417") (name "unconnected-(JP666-Pad1)") (class "Default")
      (node (ref "JP666") (pin "1") (pinfunction "1_1") (pintype "passive"))
    )
    (net (code "418") (name "unconnected-(JP667-Pad1)") (class "Default")
      (node (ref "JP667") (pin "1") (pinfunction "1_1") (pintype "passive"))
    )
    (net (code "419") (name "unconnected-(JP668-Pad1)") (class "Default")
      (node (ref "JP668") (pin "1") (pinfunction "1_1") (pintype "passive"))
    )
    (net (code "420") (name "unconnected-(JP669-Pad1)") (class "Default")
      (node (ref "JP669") (pin "1") (pinfunction "1_1") (pintype "passive"))
    )
    (net (code "421") (name "unconnected-(JP670-Pad1)") (class "Default")
      (node (ref "JP670") (pin "1") (pinfunction "1_1") (pintype "passive"))
    )
    (net (code "422") (name "unconnected-(JP671-Pad1)") (class "Default")
      (node (ref "JP671") (pin "1") (pinfunction "1_1") (pintype "passive"))
    )
    (net (code "423") (name "unconnected-(JP672-Pad1)") (class "Default")
      (node (ref "JP672") (pin "1") (pinfunction "1_1") (pintype "passive"))
    )
    (net (code "424") (name "unconnected-(JP673-Pad1)") (class "Default")
      (node (ref "JP673") (pin "1") (pinfunction "1_1") (pintype "passive"))
    )
    (net (code "425") (name "unconnected-(JP674-Pad1)") (class "Default")
      (node (ref "JP674") (pin "1") (pinfunction "1_1") (pintype "passive"))
    )
    (net (code "426") (name "unconnected-(JP675-Pad1)") (class "Default")
      (node (ref "JP675") (pin "1") (pinfunction "1_1") (pintype "passive"))
    )
    (net (code "427") (name "unconnected-(JP676-Pad1)") (class "Default")
      (node (ref "JP676") (pin "1") (pinfunction "1_1") (pintype "passive"))
    )
    (net (code "428") (name "unconnected-(JP677-Pad1)") (class "Default")
      (node (ref "JP677") (pin "1") (pinfunction "1_1") (pintype "passive"))
    )
    (net (code "429") (name "unconnected-(JP678-Pad1)") (class "Default")
      (node (ref "JP678") (pin "1") (pinfunction "1_1") (pintype "passive"))
    )
    (net (code "430") (name "unconnected-(JP679-Pad1)") (class "Default")
      (node (ref "JP679") (pin "1") (pinfunction "1_1") (pintype "passive"))
    )
    (net (code "431") (name "unconnected-(JP680-Pad1)") (class "Default")
      (node (ref "JP680") (pin "1") (pinfunction "1_1") (pintype "passive"))
    )
    (net (code "432") (name "unconnected-(JP681-Pad1)") (class "Default")
      (node (ref "JP681") (pin "1") (pinfunction "1_1") (pintype "passive"))
    )
    (net (code "433") (name "unconnected-(JP682-Pad1)") (class "Default")
      (node (ref "JP682") (pin "1") (pinfunction "1_1") (pintype "passive"))
    )
    (net (code "434") (name "unconnected-(JP683-Pad1)") (class "Default")
      (node (ref "JP683") (pin "1") (pinfunction "1_1") (pintype "passive"))
    )
    (net (code "435") (name "unconnected-(JP684-Pad1)") (class "Default")
      (node (ref "JP684") (pin "1") (pinfunction "1_1") (pintype "passive"))
    )
    (net (code "436") (name "unconnected-(JP685-Pad1)") (class "Default")
      (node (ref "JP685") (pin "1") (pinfunction "1_1") (pintype "passive"))
    )
    (net (code "437") (name "unconnected-(JP686-Pad1)") (class "Default")
      (node (ref "JP686") (pin "1") (pinfunction "1_1") (pintype "passive"))
    )
    (net (code "438") (name "unconnected-(JP687-Pad1)") (class "Default")
      (node (ref "JP687") (pin "1") (pinfunction "1_1") (pintype "passive"))
    )
    (net (code "439") (name "unconnected-(JP688-Pad1)") (class "Default")
      (node (ref "JP688") (pin "1") (pinfunction "1_1") (pintype "passive"))
    )
    (net (code "440") (name "unconnected-(JP689-Pad1)") (class "Default")
      (node (ref "JP689") (pin "1") (pinfunction "1_1") (pintype "passive"))
    )
    (net (code "441") (name "unconnected-(JP690-Pad1)") (class "Default")
      (node (ref "JP690") (pin "1") (pinfunction "1_1") (pintype "passive"))
    )
    (net (code "442") (name "unconnected-(JP691-Pad1)") (class "Default")
      (node (ref "JP691") (pin "1") (pinfunction "1_1") (pintype "passive"))
    )
    (net (code "443") (name "unconnected-(JP692-Pad1)") (class "Default")
      (node (ref "JP692") (pin "1") (pinfunction "1_1") (pintype "passive"))
    )
    (net (code "444") (name "unconnected-(JP693-Pad1)") (class "Default")
      (node (ref "JP693") (pin "1") (pinfunction "1_1") (pintype "passive"))
    )
    (net (code "445") (name "unconnected-(JP694-Pad1)") (class "Default")
      (node (ref "JP694") (pin "1") (pinfunction "1_1") (pintype "passive"))
    )
    (net (code "446") (name "unconnected-(JP695-Pad1)") (class "Default")
      (node (ref "JP695") (pin "1") (pinfunction "1_1") (pintype "passive"))
    )
    (net (code "447") (name "unconnected-(JP696-Pad1)") (class "Default")
      (node (ref "JP696") (pin "1") (pinfunction "1_1") (pintype "passive"))
    )
    (net (code "448") (name "unconnected-(JP697-Pad1)") (class "Default")
      (node (ref "JP697") (pin "1") (pinfunction "1_1") (pintype "passive"))
    )
    (net (code "449") (name "unconnected-(JP698-Pad1)") (class "Default")
      (node (ref "JP698") (pin "1") (pinfunction "1_1") (pintype "passive"))
    )
    (net (code "450") (name "unconnected-(JP699-Pad1)") (class "Default")
      (node (ref "JP699") (pin "1") (pinfunction "1_1") (pintype "passive"))
    )
    (net (code "451") (name "unconnected-(JP700-Pad1)") (class "Default")
      (node (ref "JP700") (pin "1") (pinfunction "1_1") (pintype "passive"))
    )
    (net (code "452") (name "unconnected-(JP701-Pad1)") (class "Default")
      (node (ref "JP701") (pin "1") (pinfunction "1_1") (pintype "passive"))
    )
    (net (code "453") (name "unconnected-(JP702-Pad1)") (class "Default")
      (node (ref "JP702") (pin "1") (pinfunction "1_1") (pintype "passive"))
    )
    (net (code "454") (name "unconnected-(JP703-Pad1)") (class "Default")
      (node (ref "JP703") (pin "1") (pinfunction "1_1") (pintype "passive"))
    )
    (net (code "455") (name "unconnected-(JP704-Pad1)") (class "Default")
      (node (ref "JP704") (pin "1") (pinfunction "1_1") (pintype "passive"))
    )
    (net (code "456") (name "unconnected-(JP705-Pad1)") (class "Default")
      (node (ref "JP705") (pin "1") (pinfunction "1_1") (pintype "passive"))
    )
    (net (code "457") (name "unconnected-(JP706-Pad1)") (class "Default")
      (node (ref "JP706") (pin "1") (pinfunction "1_1") (pintype "passive"))
    )
    (net (code "458") (name "unconnected-(JP707-Pad1)") (class "Default")
      (node (ref "JP707") (pin "1") (pinfunction "1_1") (pintype "passive"))
    )
    (net (code "459") (name "unconnected-(JP708-Pad1)") (class "Default")
      (node (ref "JP708") (pin "1") (pinfunction "1_1") (pintype "passive"))
    )
    (net (code "460") (name "unconnected-(JP709-Pad1)") (class "Default")
      (node (ref "JP709") (pin "1") (pinfunction "1_1") (pintype "passive"))
    )
    (net (code "461") (name "unconnected-(JP710-Pad1)") (class "Default")
      (node (ref "JP710") (pin "1") (pinfunction "1_1") (pintype "passive"))
    )
    (net (code "462") (name "unconnected-(JP711-Pad1)") (class "Default")
      (node (ref "JP711") (pin "1") (pinfunction "1_1") (pintype "passive"))
    )
    (net (code "463") (name "unconnected-(JP712-Pad1)") (class "Default")
      (node (ref "JP712") (pin "1") (pinfunction "1_1") (pintype "passive"))
    )
    (net (code "464") (name "unconnected-(JP713-Pad1)") (class "Default")
      (node (ref "JP713") (pin "1") (pinfunction "1_1") (pintype "passive"))
    )
    (net (code "465") (name "unconnected-(JP714-Pad1)") (class "Default")
      (node (ref "JP714") (pin "1") (pinfunction "1_1") (pintype "passive"))
    )
    (net (code "466") (name "unconnected-(JP715-Pad1)") (class "Default")
      (node (ref "JP715") (pin "1") (pinfunction "1_1") (pintype "passive"))
    )
    (net (code "467") (name "unconnected-(JP716-Pad1)") (class "Default")
      (node (ref "JP716") (pin "1") (pinfunction "1_1") (pintype "passive"))
    )
    (net (code "468") (name "unconnected-(JP717-Pad1)") (class "Default")
      (node (ref "JP717") (pin "1") (pinfunction "1_1") (pintype "passive"))
    )
    (net (code "469") (name "unconnected-(JP718-Pad1)") (class "Default")
      (node (ref "JP718") (pin "1") (pinfunction "1_1") (pintype "passive"))
    )
    (net (code "470") (name "unconnected-(JP719-Pad1)") (class "Default")
      (node (ref "JP719") (pin "1") (pinfunction "1_1") (pintype "passive"))
    )
    (net (code "471") (name "unconnected-(JP720-Pad1)") (class "Default")
      (node (ref "JP720") (pin "1") (pinfunction "1_1") (pintype "passive"))
    )
    (net (code "472") (name "unconnected-(JP721-Pad1)") (class "Default")
      (node (ref "JP721") (pin "1") (pinfunction "1_1") (pintype "passive"))
    )
    (net (code "473") (name "unconnected-(JP722-Pad1)") (class "Default")
      (node (ref "JP722") (pin "1") (pinfunction "1_1") (pintype "passive"))
    )
    (net (code "474") (name "unconnected-(JP741-Pad1)") (class "Default")
      (node (ref "JP741") (pin "1") (pinfunction "1_1") (pintype "passive"))
    )
    (net (code "475") (name "unconnected-(JP784-Pad1)") (class "Default")
      (node (ref "JP784") (pin "1") (pinfunction "1_1") (pintype "passive"))
    )
    (net (code "476") (name "unconnected-(JP785-Pad1)") (class "Default")
      (node (ref "JP785") (pin "1") (pinfunction "1_1") (pintype "passive"))
    )
    (net (code "477") (name "unconnected-(JP786-Pad1)") (class "Default")
      (node (ref "JP786") (pin "1") (pinfunction "1_1") (pintype "passive"))
    )
    (net (code "478") (name "unconnected-(JP787-Pad1)") (class "Default")
      (node (ref "JP787") (pin "1") (pinfunction "1_1") (pintype "passive"))
    )
    (net (code "479") (name "unconnected-(JP791-Pad1)") (class "Default")
      (node (ref "JP791") (pin "1") (pinfunction "1_1") (pintype "passive"))
    )
    (net (code "480") (name "unconnected-(JP792-Pad1)") (class "Default")
      (node (ref "JP792") (pin "1") (pinfunction "1_1") (pintype "passive"))
    )
    (net (code "481") (name "unconnected-(JP793-Pad1)") (class "Default")
      (node (ref "JP793") (pin "1") (pinfunction "1_1") (pintype "passive"))
    )
    (net (code "482") (name "unconnected-(JP794-Pad1)") (class "Default")
      (node (ref "JP794") (pin "1") (pinfunction "1_1") (pintype "passive"))
    )
    (net (code "483") (name "unconnected-(JP843-Pad1)") (class "Default")
      (node (ref "JP843") (pin "1") (pinfunction "1_1") (pintype "passive"))
    )
    (net (code "484") (name "unconnected-(JP844-Pad1)") (class "Default")
      (node (ref "JP844") (pin "1") (pinfunction "1_1") (pintype "passive"))
    )
    (net (code "485") (name "unconnected-(JP845-Pad1)") (class "Default")
      (node (ref "JP845") (pin "1") (pinfunction "1_1") (pintype "passive"))
    )
    (net (code "486") (name "unconnected-(JP846-Pad1)") (class "Default")
      (node (ref "JP846") (pin "1") (pinfunction "1_1") (pintype "passive"))
    )
    (net (code "487") (name "unconnected-(JP847-Pad1)") (class "Default")
      (node (ref "JP847") (pin "1") (pinfunction "1_1") (pintype "passive"))
    )
    (net (code "488") (name "unconnected-(JP848-Pad1)") (class "Default")
      (node (ref "JP848") (pin "1") (pinfunction "1_1") (pintype "passive"))
    )
    (net (code "489") (name "unconnected-(JP849-Pad1)") (class "Default")
      (node (ref "JP849") (pin "1") (pinfunction "1_1") (pintype "passive"))
    )
    (net (code "490") (name "unconnected-(JP850-Pad1)") (class "Default")
      (node (ref "JP850") (pin "1") (pinfunction "1_1") (pintype "passive"))
    )
    (net (code "491") (name "unconnected-(JP851-Pad1)") (class "Default")
      (node (ref "JP851") (pin "1") (pinfunction "1_1") (pintype "passive"))
    )
    (net (code "492") (name "unconnected-(JP852-Pad1)") (class "Default")
      (node (ref "JP852") (pin "1") (pinfunction "1_1") (pintype "passive"))
    )
    (net (code "493") (name "unconnected-(JP853-Pad1)") (class "Default")
      (node (ref "JP853") (pin "1") (pinfunction "1_1") (pintype "passive"))
    )
    (net (code "494") (name "unconnected-(JP854-Pad1)") (class "Default")
      (node (ref "JP854") (pin "1") (pinfunction "1_1") (pintype "passive"))
    )
    (net (code "495") (name "unconnected-(JP855-Pad1)") (class "Default")
      (node (ref "JP855") (pin "1") (pinfunction "1_1") (pintype "passive"))
    )
    (net (code "496") (name "unconnected-(JP856-Pad1)") (class "Default")
      (node (ref "JP856") (pin "1") (pinfunction "1_1") (pintype "passive"))
    )
    (net (code "497") (name "unconnected-(JP857-Pad1)") (class "Default")
      (node (ref "JP857") (pin "1") (pinfunction "1_1") (pintype "passive"))
    )
    (net (code "498") (name "unconnected-(JP858-Pad1)") (class "Default")
      (node (ref "JP858") (pin "1") (pinfunction "1_1") (pintype "passive"))
    )
    (net (code "499") (name "unconnected-(JP859-Pad1)") (class "Default")
      (node (ref "JP859") (pin "1") (pinfunction "1_1") (pintype "passive"))
    )
    (net (code "500") (name "unconnected-(JP860-Pad1)") (class "Default")
      (node (ref "JP860") (pin "1") (pinfunction "1_1") (pintype "passive"))
    )
    (net (code "501") (name "unconnected-(JP861-Pad1)") (class "Default")
      (node (ref "JP861") (pin "1") (pinfunction "1_1") (pintype "passive"))
    )
    (net (code "502") (name "unconnected-(JP862-Pad1)") (class "Default")
      (node (ref "JP862") (pin "1") (pinfunction "1_1") (pintype "passive"))
    )
    (net (code "503") (name "unconnected-(JP863-Pad1)") (class "Default")
      (node (ref "JP863") (pin "1") (pinfunction "1_1") (pintype "passive"))
    )
    (net (code "504") (name "unconnected-(JP864-Pad1)") (class "Default")
      (node (ref "JP864") (pin "1") (pinfunction "1_1") (pintype "passive"))
    )
    (net (code "505") (name "unconnected-(JP865-Pad1)") (class "Default")
      (node (ref "JP865") (pin "1") (pinfunction "1_1") (pintype "passive"))
    )
    (net (code "506") (name "unconnected-(JP866-Pad1)") (class "Default")
      (node (ref "JP866") (pin "1") (pinfunction "1_1") (pintype "passive"))
    )
    (net (code "507") (name "unconnected-(JP867-Pad1)") (class "Default")
      (node (ref "JP867") (pin "1") (pinfunction "1_1") (pintype "passive"))
    )
    (net (code "508") (name "unconnected-(JP868-Pad1)") (class "Default")
      (node (ref "JP868") (pin "1") (pinfunction "1_1") (pintype "passive"))
    )
    (net (code "509") (name "unconnected-(JP869-Pad1)") (class "Default")
      (node (ref "JP869") (pin "1") (pinfunction "1_1") (pintype "passive"))
    )
    (net (code "510") (name "unconnected-(JP870-Pad1)") (class "Default")
      (node (ref "JP870") (pin "1") (pinfunction "1_1") (pintype "passive"))
    )
    (net (code "511") (name "unconnected-(JP871-Pad1)") (class "Default")
      (node (ref "JP871") (pin "1") (pinfunction "1_1") (pintype "passive"))
    )
    (net (code "512") (name "unconnected-(JP872-Pad1)") (class "Default")
      (node (ref "JP872") (pin "1") (pinfunction "1_1") (pintype "passive"))
    )
    (net (code "513") (name "unconnected-(JP873-Pad1)") (class "Default")
      (node (ref "JP873") (pin "1") (pinfunction "1_1") (pintype "passive"))
    )
    (net (code "514") (name "unconnected-(JP874-Pad1)") (class "Default")
      (node (ref "JP874") (pin "1") (pinfunction "1_1") (pintype "passive"))
    )
    (net (code "515") (name "unconnected-(JP875-Pad1)") (class "Default")
      (node (ref "JP875") (pin "1") (pinfunction "1_1") (pintype "passive"))
    )
    (net (code "516") (name "unconnected-(JP876-Pad1)") (class "Default")
      (node (ref "JP876") (pin "1") (pinfunction "1_1") (pintype "passive"))
    )
    (net (code "517") (name "unconnected-(JP877-Pad1)") (class "Default")
      (node (ref "JP877") (pin "1") (pinfunction "1_1") (pintype "passive"))
    )
    (net (code "518") (name "unconnected-(JP878-Pad1)") (class "Default")
      (node (ref "JP878") (pin "1") (pinfunction "1_1") (pintype "passive"))
    )
    (net (code "519") (name "unconnected-(JP879-Pad1)") (class "Default")
      (node (ref "JP879") (pin "1") (pinfunction "1_1") (pintype "passive"))
    )
    (net (code "520") (name "unconnected-(JP880-Pad1)") (class "Default")
      (node (ref "JP880") (pin "1") (pinfunction "1_1") (pintype "passive"))
    )
    (net (code "521") (name "unconnected-(JP881-Pad1)") (class "Default")
      (node (ref "JP881") (pin "1") (pinfunction "1_1") (pintype "passive"))
    )
    (net (code "522") (name "unconnected-(JP882-Pad1)") (class "Default")
      (node (ref "JP882") (pin "1") (pinfunction "1_1") (pintype "passive"))
    )
    (net (code "523") (name "unconnected-(JP883-Pad1)") (class "Default")
      (node (ref "JP883") (pin "1") (pinfunction "1_1") (pintype "passive"))
    )
    (net (code "524") (name "unconnected-(JP884-Pad1)") (class "Default")
      (node (ref "JP884") (pin "1") (pinfunction "1_1") (pintype "passive"))
    )
    (net (code "525") (name "unconnected-(JP885-Pad1)") (class "Default")
      (node (ref "JP885") (pin "1") (pinfunction "1_1") (pintype "passive"))
    )
    (net (code "526") (name "unconnected-(JP886-Pad1)") (class "Default")
      (node (ref "JP886") (pin "1") (pinfunction "1_1") (pintype "passive"))
    )
    (net (code "527") (name "unconnected-(JP887-Pad1)") (class "Default")
      (node (ref "JP887") (pin "1") (pinfunction "1_1") (pintype "passive"))
    )
    (net (code "528") (name "unconnected-(JP888-Pad1)") (class "Default")
      (node (ref "JP888") (pin "1") (pinfunction "1_1") (pintype "passive"))
    )
    (net (code "529") (name "unconnected-(JP889-Pad1)") (class "Default")
      (node (ref "JP889") (pin "1") (pinfunction "1_1") (pintype "passive"))
    )
    (net (code "530") (name "unconnected-(JP890-Pad1)") (class "Default")
      (node (ref "JP890") (pin "1") (pinfunction "1_1") (pintype "passive"))
    )
    (net (code "531") (name "unconnected-(JP891-Pad1)") (class "Default")
      (node (ref "JP891") (pin "1") (pinfunction "1_1") (pintype "passive"))
    )
    (net (code "532") (name "unconnected-(JP892-Pad1)") (class "Default")
      (node (ref "JP892") (pin "1") (pinfunction "1_1") (pintype "passive"))
    )
    (net (code "533") (name "unconnected-(JP893-Pad1)") (class "Default")
      (node (ref "JP893") (pin "1") (pinfunction "1_1") (pintype "passive"))
    )
    (net (code "534") (name "unconnected-(JP894-Pad1)") (class "Default")
      (node (ref "JP894") (pin "1") (pinfunction "1_1") (pintype "passive"))
    )
    (net (code "535") (name "unconnected-(JP895-Pad1)") (class "Default")
      (node (ref "JP895") (pin "1") (pinfunction "1_1") (pintype "passive"))
    )
    (net (code "536") (name "unconnected-(JP896-Pad1)") (class "Default")
      (node (ref "JP896") (pin "1") (pinfunction "1_1") (pintype "passive"))
    )
    (net (code "537") (name "unconnected-(JP897-Pad1)") (class "Default")
      (node (ref "JP897") (pin "1") (pinfunction "1_1") (pintype "passive"))
    )
    (net (code "538") (name "unconnected-(JP898-Pad1)") (class "Default")
      (node (ref "JP898") (pin "1") (pinfunction "1_1") (pintype "passive"))
    )
    (net (code "539") (name "unconnected-(JP899-Pad1)") (class "Default")
      (node (ref "JP899") (pin "1") (pinfunction "1_1") (pintype "passive"))
    )
    (net (code "540") (name "unconnected-(JP900-Pad1)") (class "Default")
      (node (ref "JP900") (pin "1") (pinfunction "1_1") (pintype "passive"))
    )
    (net (code "541") (name "unconnected-(JP901-Pad1)") (class "Default")
      (node (ref "JP901") (pin "1") (pinfunction "1_1") (pintype "passive"))
    )
    (net (code "542") (name "unconnected-(JP902-Pad1)") (class "Default")
      (node (ref "JP902") (pin "1") (pinfunction "1_1") (pintype "passive"))
    )
    (net (code "543") (name "unconnected-(JP903-Pad1)") (class "Default")
      (node (ref "JP903") (pin "1") (pinfunction "1_1") (pintype "passive"))
    )
    (net (code "544") (name "unconnected-(JP904-Pad1)") (class "Default")
      (node (ref "JP904") (pin "1") (pinfunction "1_1") (pintype "passive"))
    )
    (net (code "545") (name "unconnected-(JP905-Pad1)") (class "Default")
      (node (ref "JP905") (pin "1") (pinfunction "1_1") (pintype "passive"))
    )
    (net (code "546") (name "unconnected-(JP906-Pad1)") (class "Default")
      (node (ref "JP906") (pin "1") (pinfunction "1_1") (pintype "passive"))
    )
    (net (code "547") (name "unconnected-(JP907-Pad1)") (class "Default")
      (node (ref "JP907") (pin "1") (pinfunction "1_1") (pintype "passive"))
    )
    (net (code "548") (name "unconnected-(JP908-Pad1)") (class "Default")
      (node (ref "JP908") (pin "1") (pinfunction "1_1") (pintype "passive"))
    )
    (net (code "549") (name "unconnected-(JP909-Pad1)") (class "Default")
      (node (ref "JP909") (pin "1") (pinfunction "1_1") (pintype "passive"))
    )
    (net (code "550") (name "unconnected-(JP910-Pad1)") (class "Default")
      (node (ref "JP910") (pin "1") (pinfunction "1_1") (pintype "passive"))
    )
    (net (code "551") (name "unconnected-(JP911-Pad1)") (class "Default")
      (node (ref "JP911") (pin "1") (pinfunction "1_1") (pintype "passive"))
    )
    (net (code "552") (name "unconnected-(JP912-Pad1)") (class "Default")
      (node (ref "JP912") (pin "1") (pinfunction "1_1") (pintype "passive"))
    )
    (net (code "553") (name "unconnected-(JP913-Pad1)") (class "Default")
      (node (ref "JP913") (pin "1") (pinfunction "1_1") (pintype "passive"))
    )
    (net (code "554") (name "unconnected-(JP914-Pad1)") (class "Default")
      (node (ref "JP914") (pin "1") (pinfunction "1_1") (pintype "passive"))
    )
    (net (code "555") (name "unconnected-(JP915-Pad1)") (class "Default")
      (node (ref "JP915") (pin "1") (pinfunction "1_1") (pintype "passive"))
    )
    (net (code "556") (name "unconnected-(JP916-Pad1)") (class "Default")
      (node (ref "JP916") (pin "1") (pinfunction "1_1") (pintype "passive"))
    )
    (net (code "557") (name "unconnected-(JP917-Pad1)") (class "Default")
      (node (ref "JP917") (pin "1") (pinfunction "1_1") (pintype "passive"))
    )
    (net (code "558") (name "unconnected-(JP918-Pad1)") (class "Default")
      (node (ref "JP918") (pin "1") (pinfunction "1_1") (pintype "passive"))
    )
    (net (code "559") (name "unconnected-(JP919-Pad1)") (class "Default")
      (node (ref "JP919") (pin "1") (pinfunction "1_1") (pintype "passive"))
    )
    (net (code "560") (name "unconnected-(JP920-Pad1)") (class "Default")
      (node (ref "JP920") (pin "1") (pinfunction "1_1") (pintype "passive"))
    )
    (net (code "561") (name "unconnected-(JP921-Pad1)") (class "Default")
      (node (ref "JP921") (pin "1") (pinfunction "1_1") (pintype "passive"))
    )
    (net (code "562") (name "unconnected-(JP922-Pad1)") (class "Default")
      (node (ref "JP922") (pin "1") (pinfunction "1_1") (pintype "passive"))
    )
    (net (code "563") (name "unconnected-(JP923-Pad1)") (class "Default")
      (node (ref "JP923") (pin "1") (pinfunction "1_1") (pintype "passive"))
    )
    (net (code "564") (name "unconnected-(JP924-Pad1)") (class "Default")
      (node (ref "JP924") (pin "1") (pinfunction "1_1") (pintype "passive"))
    )
    (net (code "565") (name "unconnected-(JP925-Pad1)") (class "Default")
      (node (ref "JP925") (pin "1") (pinfunction "1_1") (pintype "passive"))
    )
    (net (code "566") (name "unconnected-(JP926-Pad1)") (class "Default")
      (node (ref "JP926") (pin "1") (pinfunction "1_1") (pintype "passive"))
    )
    (net (code "567") (name "unconnected-(JP927-Pad1)") (class "Default")
      (node (ref "JP927") (pin "1") (pinfunction "1_1") (pintype "passive"))
    )
    (net (code "568") (name "unconnected-(JP928-Pad1)") (class "Default")
      (node (ref "JP928") (pin "1") (pinfunction "1_1") (pintype "passive"))
    )
    (net (code "569") (name "unconnected-(JP929-Pad1)") (class "Default")
      (node (ref "JP929") (pin "1") (pinfunction "1_1") (pintype "passive"))
    )
    (net (code "570") (name "unconnected-(JP930-Pad1)") (class "Default")
      (node (ref "JP930") (pin "1") (pinfunction "1_1") (pintype "passive"))
    )
    (net (code "571") (name "unconnected-(JP931-Pad1)") (class "Default")
      (node (ref "JP931") (pin "1") (pinfunction "1_1") (pintype "passive"))
    )
    (net (code "572") (name "unconnected-(JP932-Pad1)") (class "Default")
      (node (ref "JP932") (pin "1") (pinfunction "1_1") (pintype "passive"))
    )
    (net (code "573") (name "unconnected-(JP933-Pad1)") (class "Default")
      (node (ref "JP933") (pin "1") (pinfunction "1_1") (pintype "passive"))
    )
    (net (code "574") (name "unconnected-(JP934-Pad1)") (class "Default")
      (node (ref "JP934") (pin "1") (pinfunction "1_1") (pintype "passive"))
    )
    (net (code "575") (name "unconnected-(JP935-Pad1)") (class "Default")
      (node (ref "JP935") (pin "1") (pinfunction "1_1") (pintype "passive"))
    )
    (net (code "576") (name "unconnected-(JP936-Pad1)") (class "Default")
      (node (ref "JP936") (pin "1") (pinfunction "1_1") (pintype "passive"))
    )
    (net (code "577") (name "unconnected-(JP937-Pad1)") (class "Default")
      (node (ref "JP937") (pin "1") (pinfunction "1_1") (pintype "passive"))
    )
    (net (code "578") (name "unconnected-(JP938-Pad1)") (class "Default")
      (node (ref "JP938") (pin "1") (pinfunction "1_1") (pintype "passive"))
    )
    (net (code "579") (name "unconnected-(JP939-Pad1)") (class "Default")
      (node (ref "JP939") (pin "1") (pinfunction "1_1") (pintype "passive"))
    )
    (net (code "580") (name "unconnected-(JP940-Pad1)") (class "Default")
      (node (ref "JP940") (pin "1") (pinfunction "1_1") (pintype "passive"))
    )
    (net (code "581") (name "unconnected-(JP941-Pad1)") (class "Default")
      (node (ref "JP941") (pin "1") (pinfunction "1_1") (pintype "passive"))
    )
    (net (code "582") (name "unconnected-(JP942-Pad1)") (class "Default")
      (node (ref "JP942") (pin "1") (pinfunction "1_1") (pintype "passive"))
    )
    (net (code "583") (name "unconnected-(JP943-Pad1)") (class "Default")
      (node (ref "JP943") (pin "1") (pinfunction "1_1") (pintype "passive"))
    )
    (net (code "584") (name "unconnected-(JP944-Pad1)") (class "Default")
      (node (ref "JP944") (pin "1") (pinfunction "1_1") (pintype "passive"))
    )
    (net (code "585") (name "unconnected-(JP945-Pad1)") (class "Default")
      (node (ref "JP945") (pin "1") (pinfunction "1_1") (pintype "passive"))
    )
    (net (code "586") (name "unconnected-(JP946-Pad1)") (class "Default")
      (node (ref "JP946") (pin "1") (pinfunction "1_1") (pintype "passive"))
    )
    (net (code "587") (name "unconnected-(JP947-Pad1)") (class "Default")
      (node (ref "JP947") (pin "1") (pinfunction "1_1") (pintype "passive"))
    )
    (net (code "588") (name "unconnected-(JP948-Pad1)") (class "Default")
      (node (ref "JP948") (pin "1") (pinfunction "1_1") (pintype "passive"))
    )
    (net (code "589") (name "unconnected-(JP949-Pad1)") (class "Default")
      (node (ref "JP949") (pin "1") (pinfunction "1_1") (pintype "passive"))
    )
    (net (code "590") (name "unconnected-(JP950-Pad1)") (class "Default")
      (node (ref "JP950") (pin "1") (pinfunction "1_1") (pintype "passive"))
    )
    (net (code "591") (name "unconnected-(JP951-Pad1)") (class "Default")
      (node (ref "JP951") (pin "1") (pinfunction "1_1") (pintype "passive"))
    )
    (net (code "592") (name "unconnected-(JP952-Pad1)") (class "Default")
      (node (ref "JP952") (pin "1") (pinfunction "1_1") (pintype "passive"))
    )
    (net (code "593") (name "unconnected-(JP953-Pad1)") (class "Default")
      (node (ref "JP953") (pin "1") (pinfunction "1_1") (pintype "passive"))
    )
    (net (code "594") (name "unconnected-(JP954-Pad1)") (class "Default")
      (node (ref "JP954") (pin "1") (pinfunction "1_1") (pintype "passive"))
    )
    (net (code "595") (name "unconnected-(JP955-Pad1)") (class "Default")
      (node (ref "JP955") (pin "1") (pinfunction "1_1") (pintype "passive"))
    )
    (net (code "596") (name "unconnected-(JP956-Pad1)") (class "Default")
      (node (ref "JP956") (pin "1") (pinfunction "1_1") (pintype "passive"))
    )
    (net (code "597") (name "unconnected-(JP957-Pad1)") (class "Default")
      (node (ref "JP957") (pin "1") (pinfunction "1_1") (pintype "passive"))
    )
    (net (code "598") (name "unconnected-(JP958-Pad1)") (class "Default")
      (node (ref "JP958") (pin "1") (pinfunction "1_1") (pintype "passive"))
    )
    (net (code "599") (name "unconnected-(JP959-Pad1)") (class "Default")
      (node (ref "JP959") (pin "1") (pinfunction "1_1") (pintype "passive"))
    )
    (net (code "600") (name "unconnected-(JP960-Pad1)") (class "Default")
      (node (ref "JP960") (pin "1") (pinfunction "1_1") (pintype "passive"))
    )
    (net (code "601") (name "unconnected-(JP961-Pad1)") (class "Default")
      (node (ref "JP961") (pin "1") (pinfunction "1_1") (pintype "passive"))
    )
    (net (code "602") (name "unconnected-(JP962-Pad1)") (class "Default")
      (node (ref "JP962") (pin "1") (pinfunction "1_1") (pintype "passive"))
    )
    (net (code "603") (name "unconnected-(U$1A-1-PadP$1)") (class "Default")
      (node (ref "U$1") (pin "P$1") (pinfunction "1_P$1") (pintype "passive"))
    )
    (net (code "604") (name "unconnected-(U$1B-1-PadP$2)") (class "Default")
      (node (ref "U$1") (pin "P$2") (pinfunction "1_P$2") (pintype "passive"))
    )
    (net (code "605") (name "unconnected-(U$1C-1-PadP$3)") (class "Default")
      (node (ref "U$1") (pin "P$3") (pinfunction "1_P$3") (pintype "passive"))
    )
    (net (code "606") (name "unconnected-(U$1D-1-PadP$4)") (class "Default")
      (node (ref "U$1") (pin "P$4") (pinfunction "1_P$4") (pintype "passive"))
    )
    (net (code "607") (name "unconnected-(U$2A-1-PadP$1)") (class "Default")
      (node (ref "U$2") (pin "P$1") (pinfunction "1_P$1") (pintype "passive"))
    )
    (net (code "608") (name "unconnected-(U$2D-1-PadP$4)") (class "Default")
      (node (ref "U$2") (pin "P$4") (pinfunction "1_P$4") (pintype "passive"))
    )
  )
)
